# AI_EINK.net
KiCad netlist of a schematic drawn in EAGLE
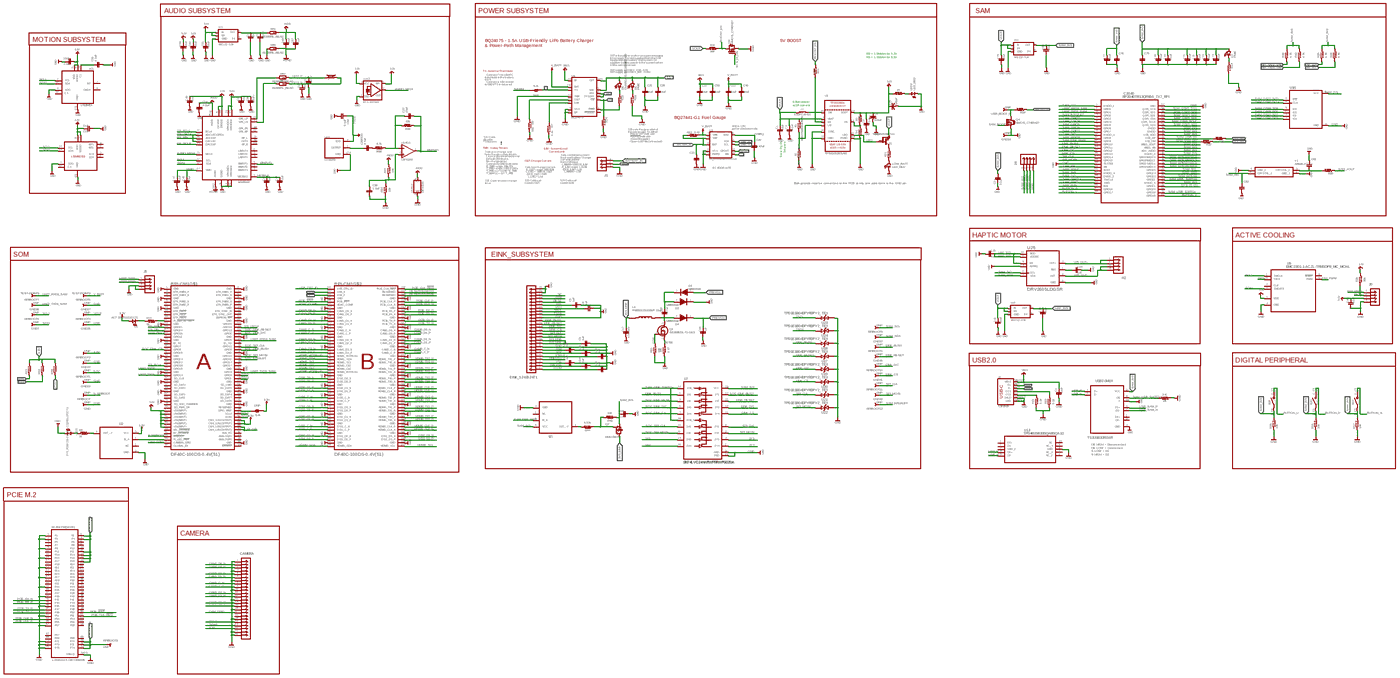
[diagram p0: schematic, sheet 1, overview]
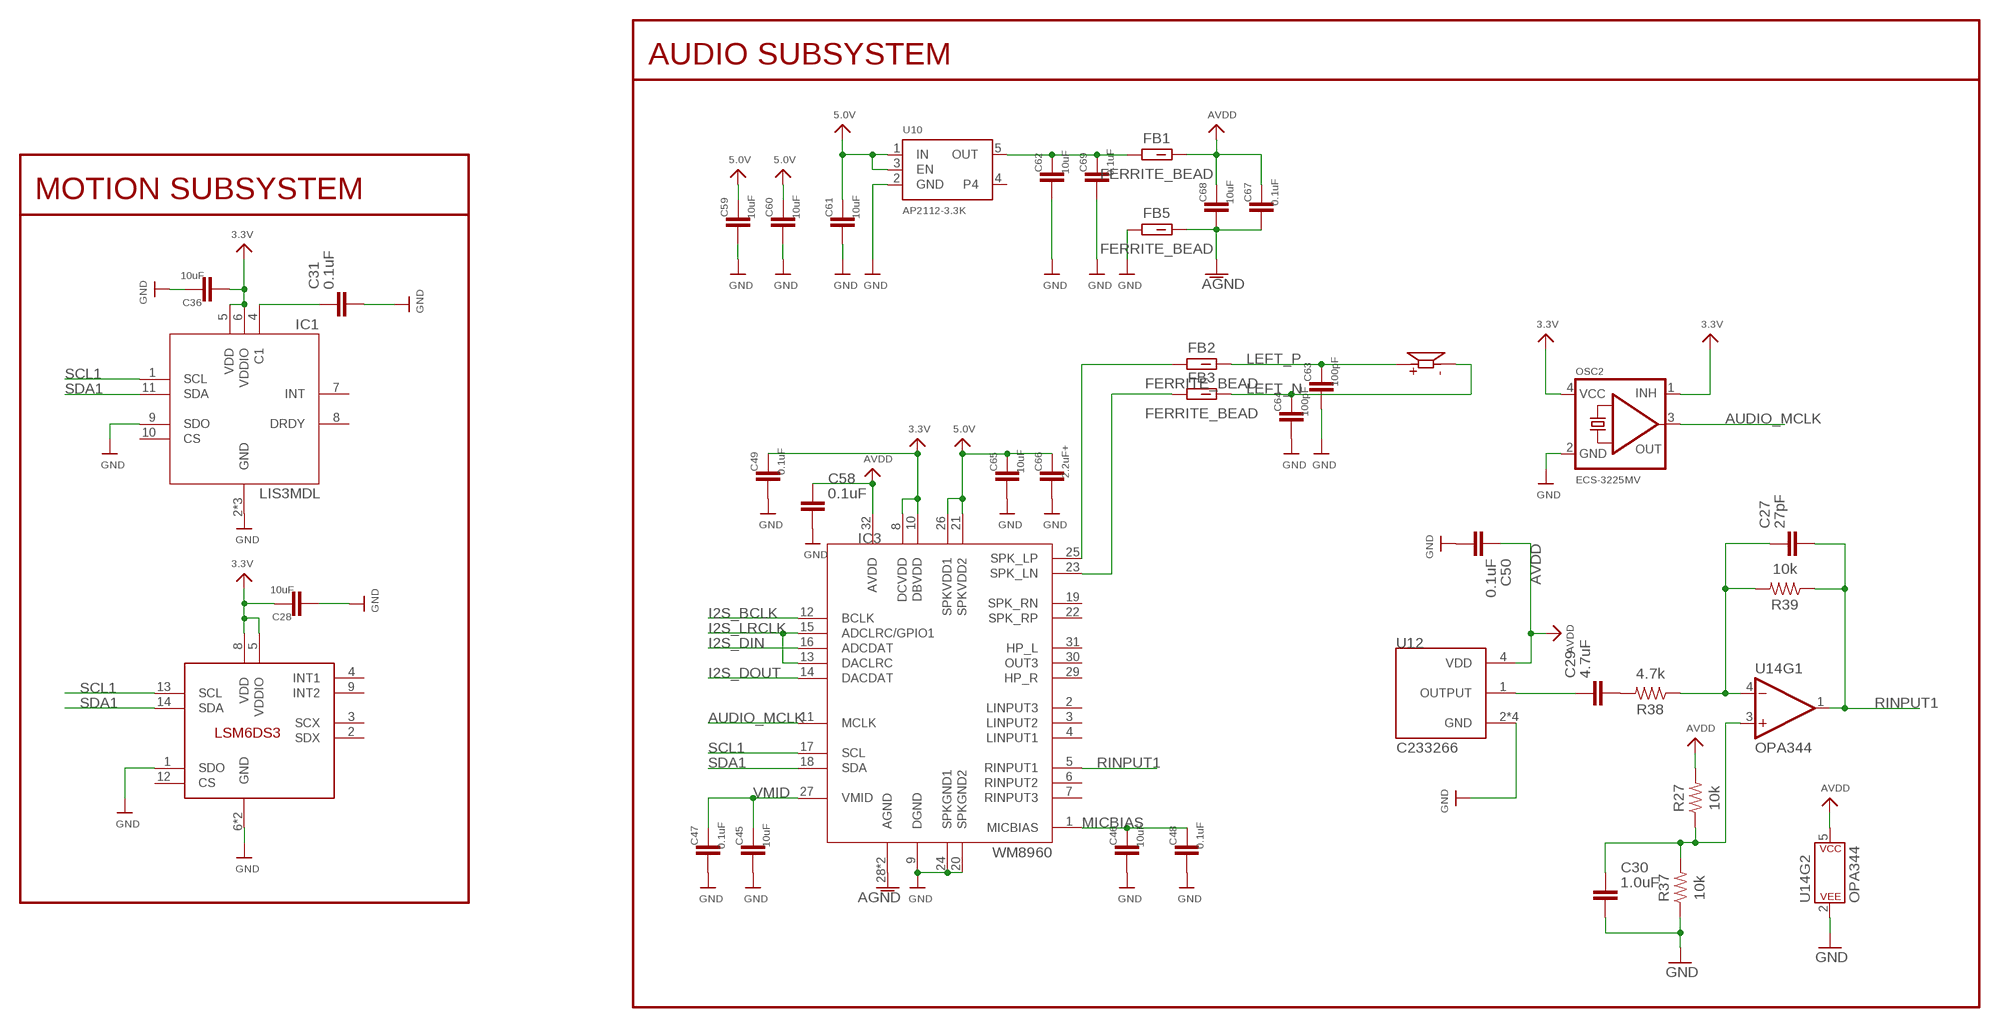
[diagram p1: schematic, sheet 1, part 1 of 5]
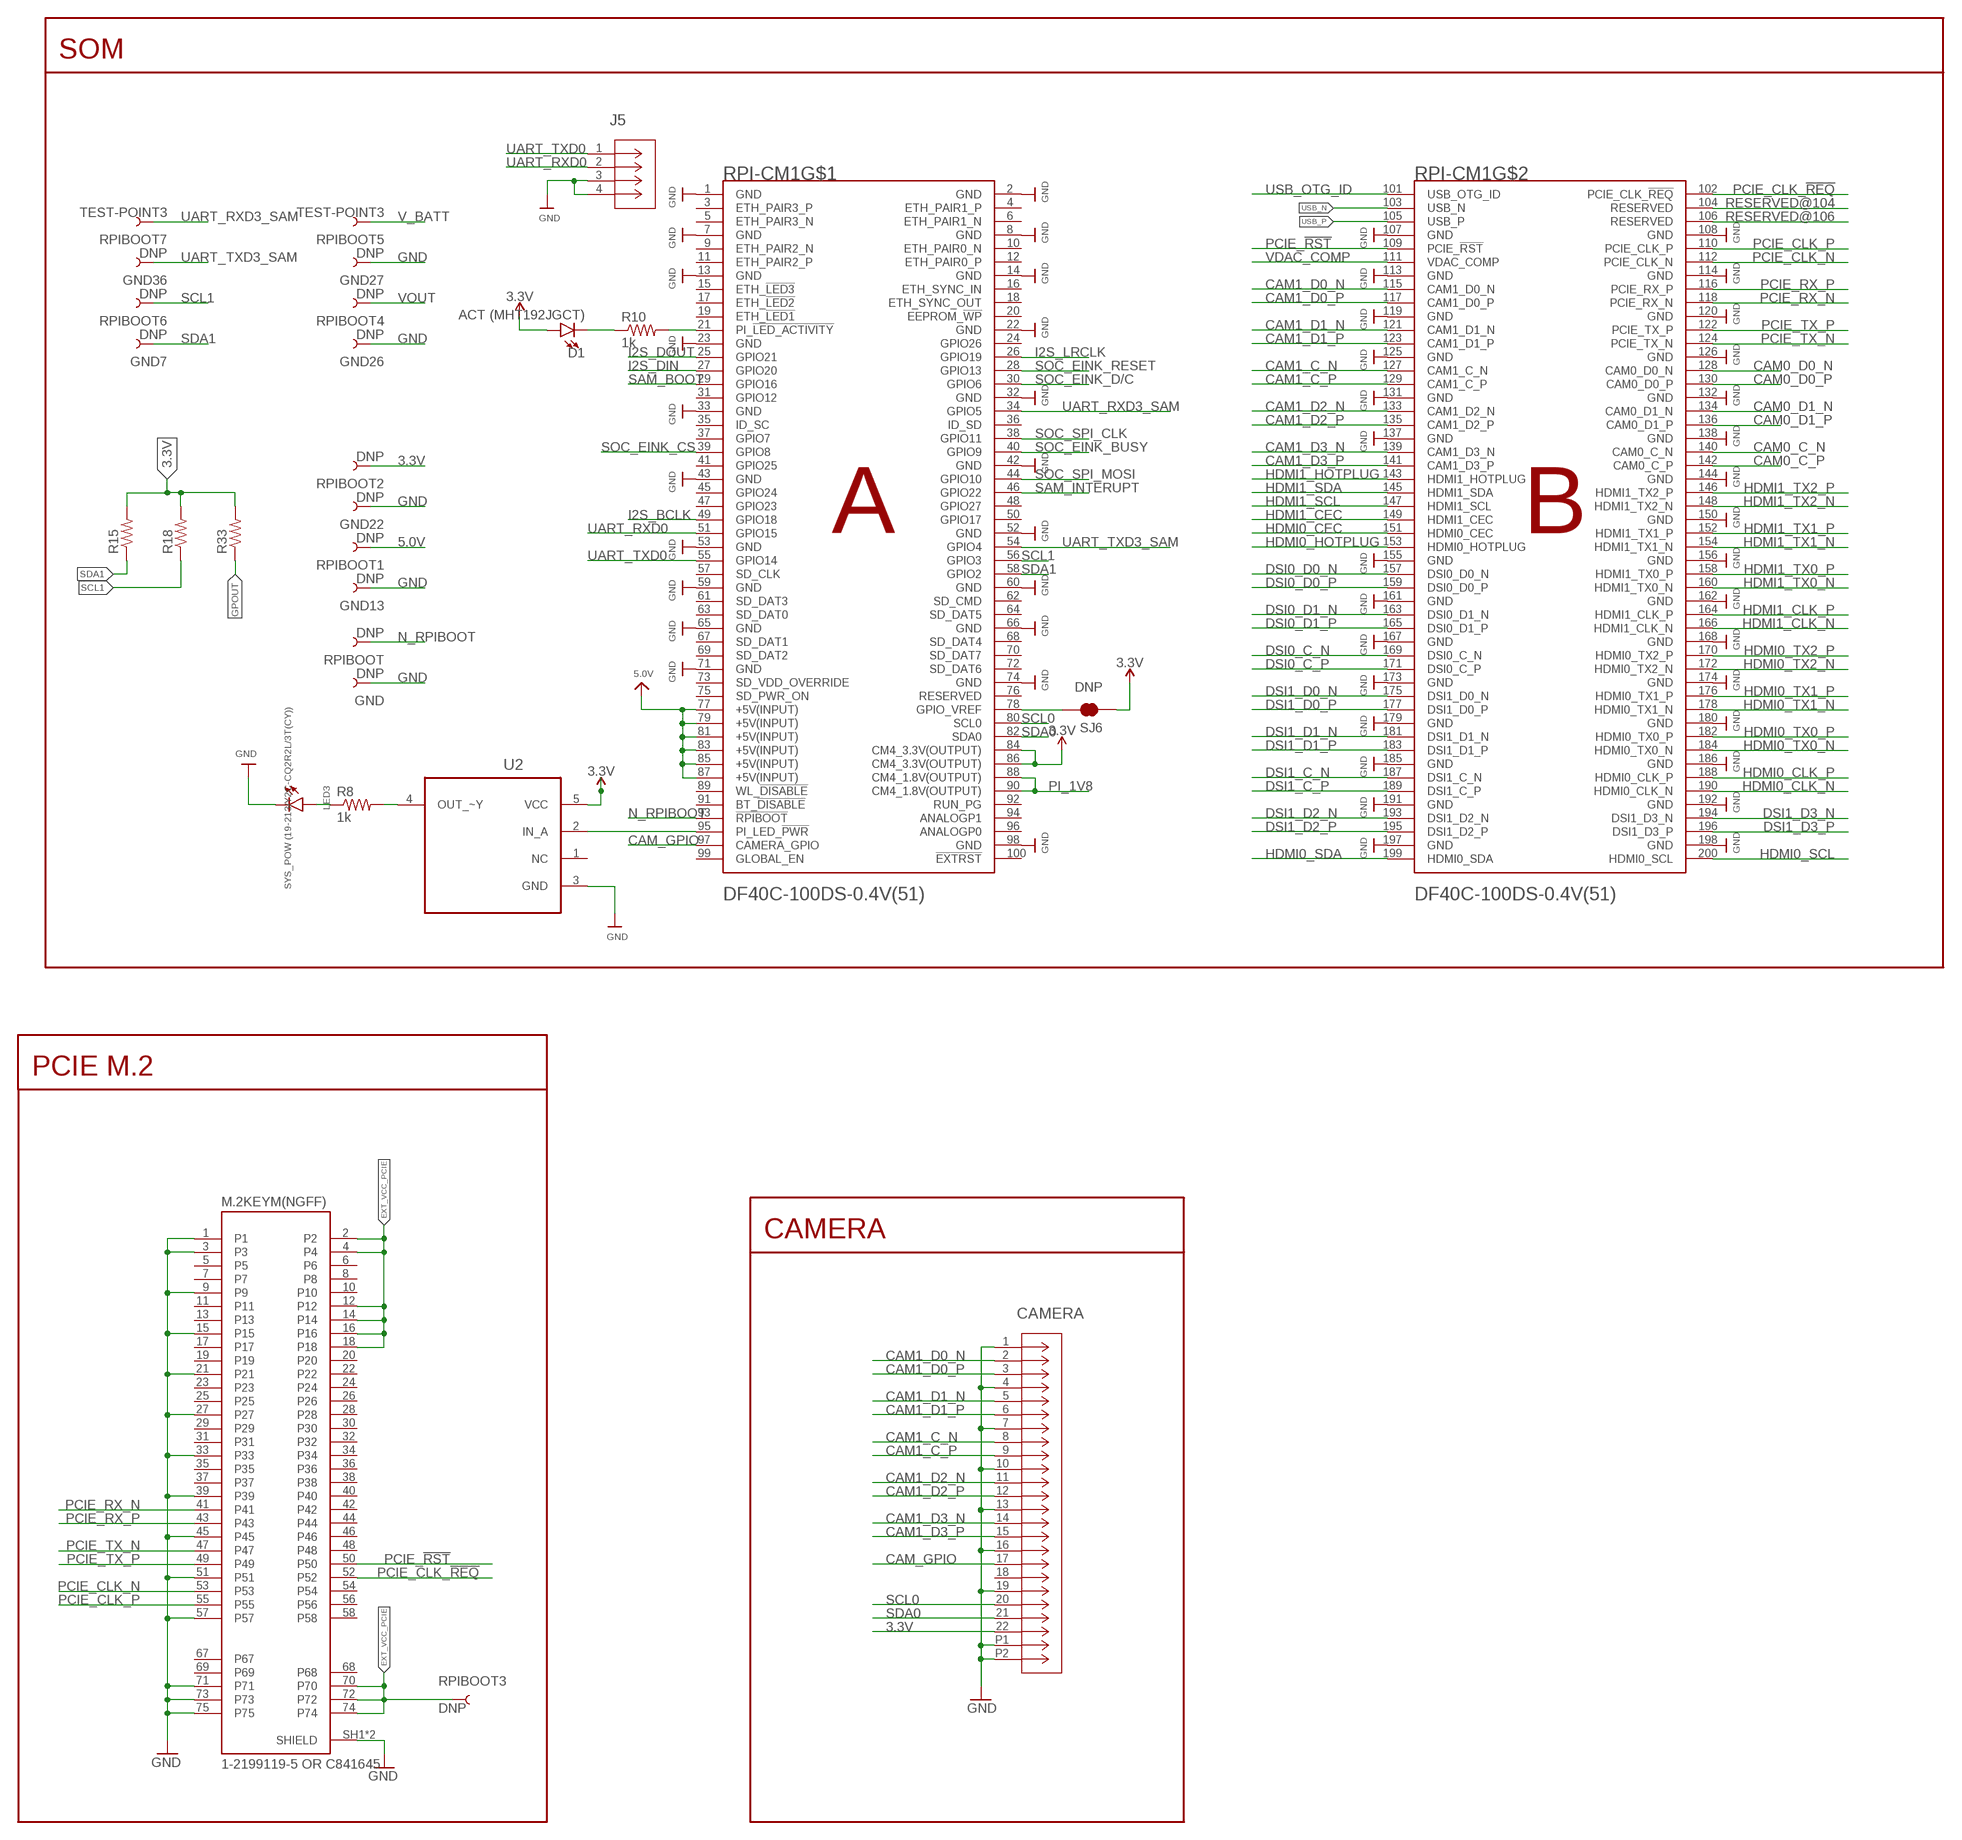
[diagram p2: schematic, sheet 1, part 2 of 5]
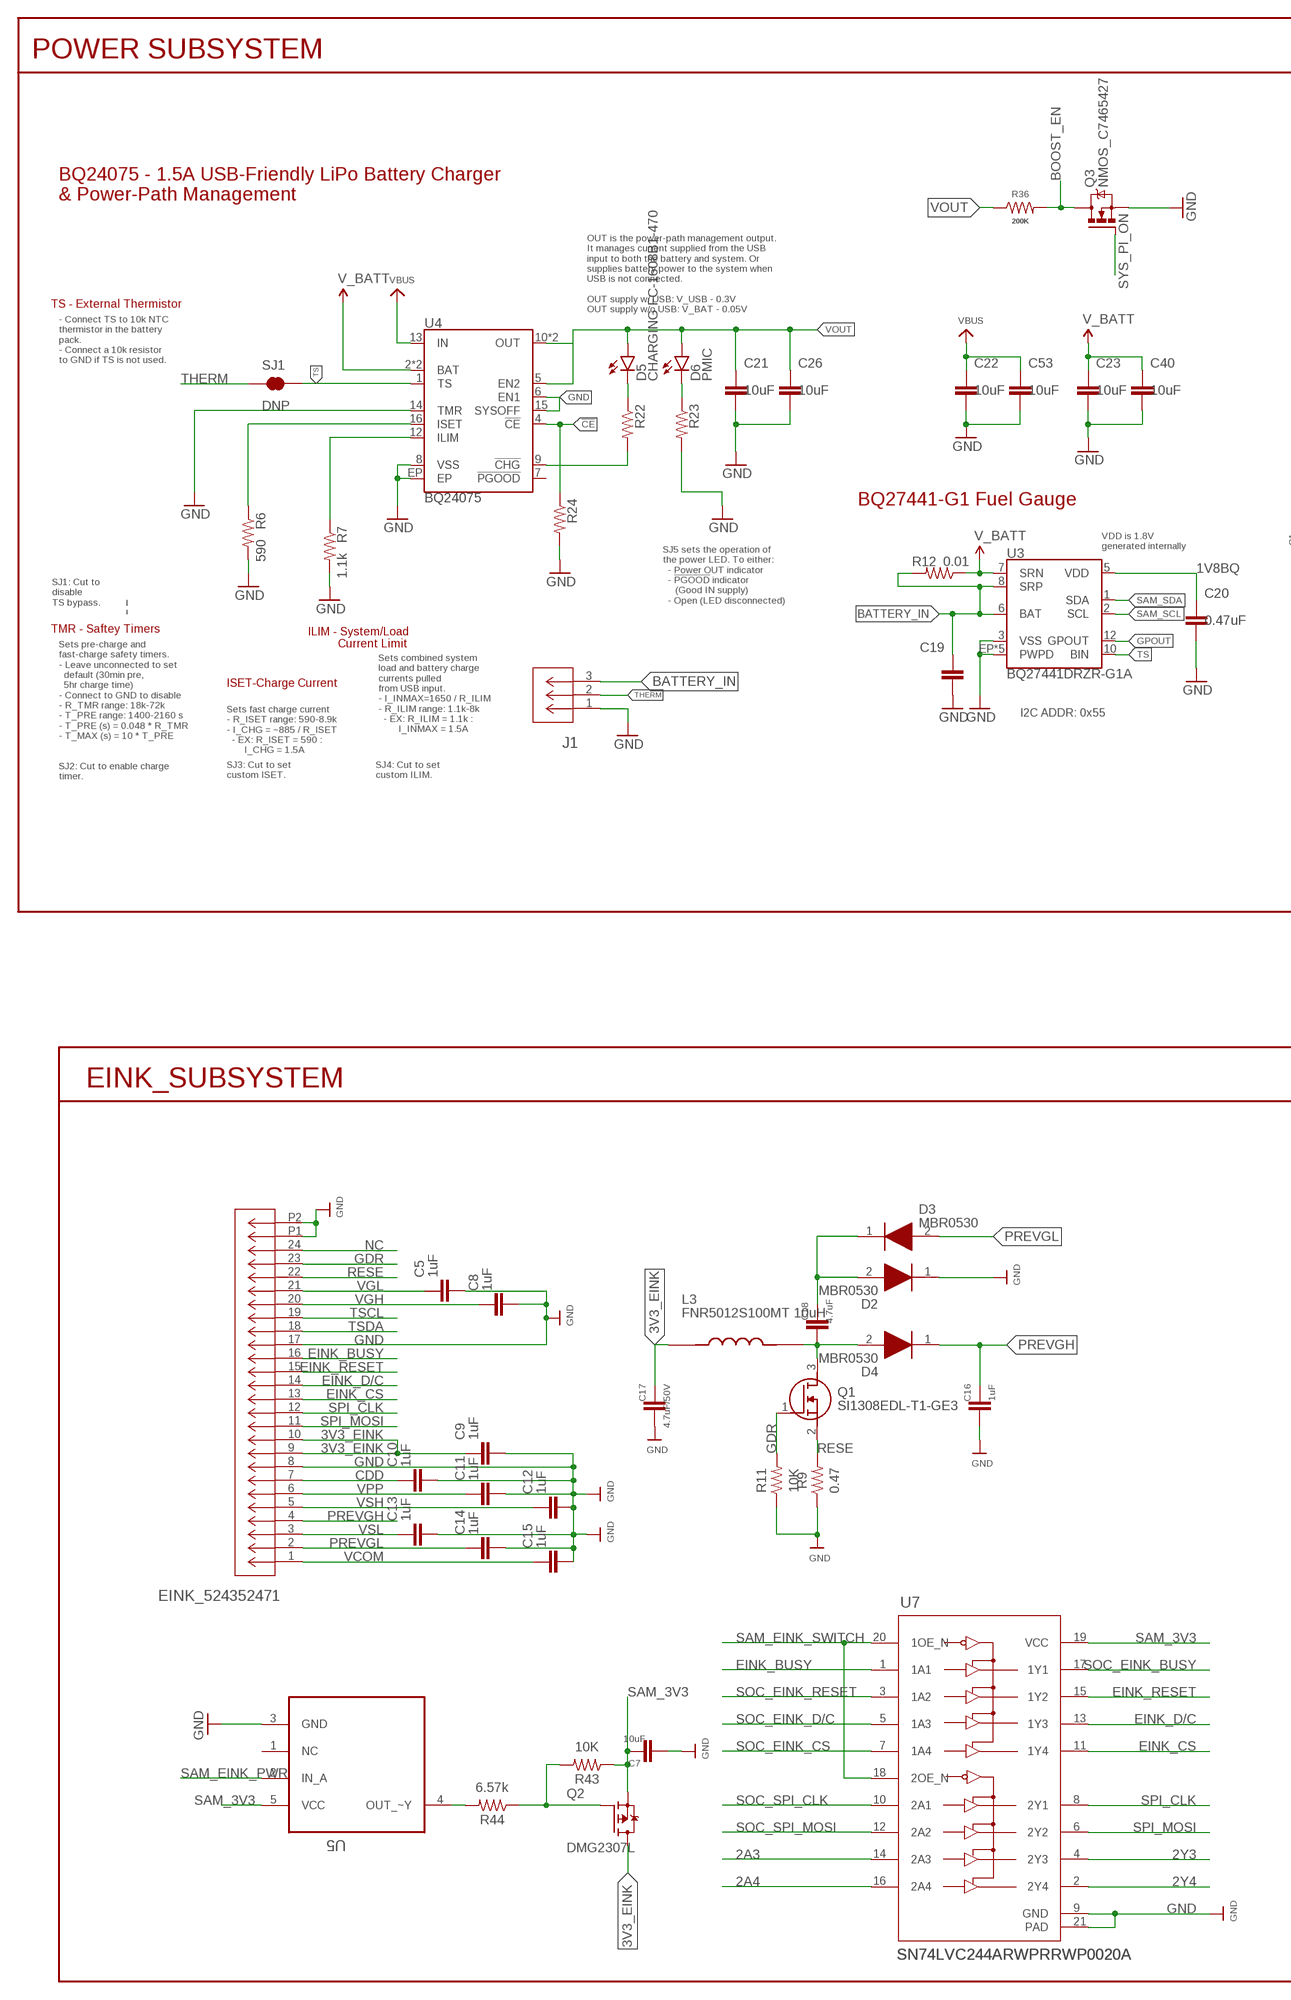
[diagram p3: schematic, sheet 1, part 3 of 5]
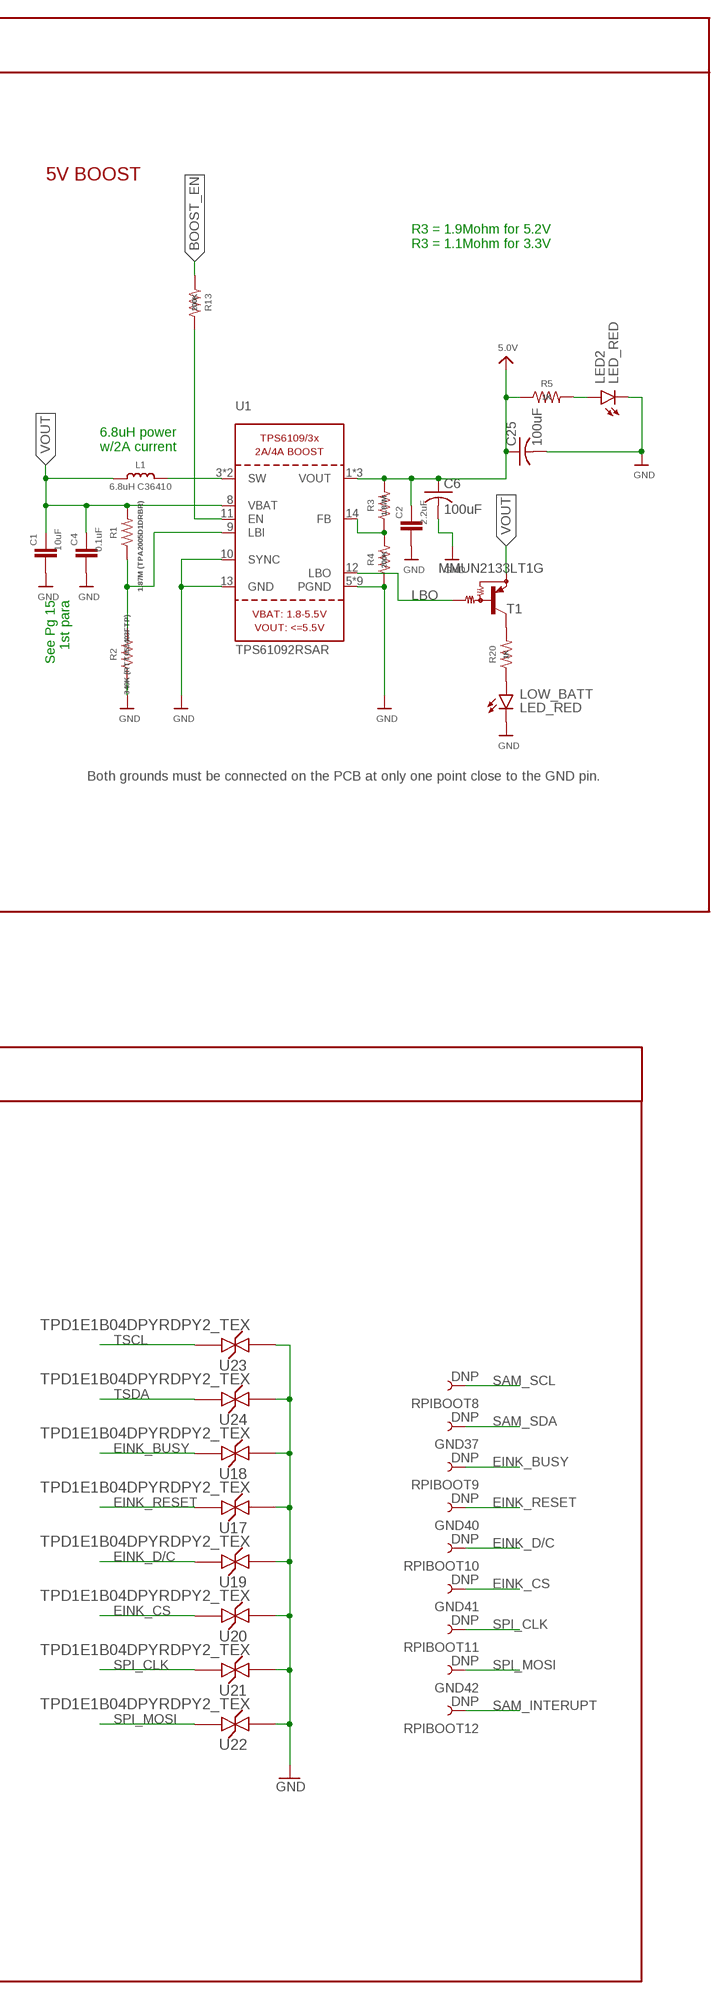
[diagram p4: schematic, sheet 1, part 4 of 5]
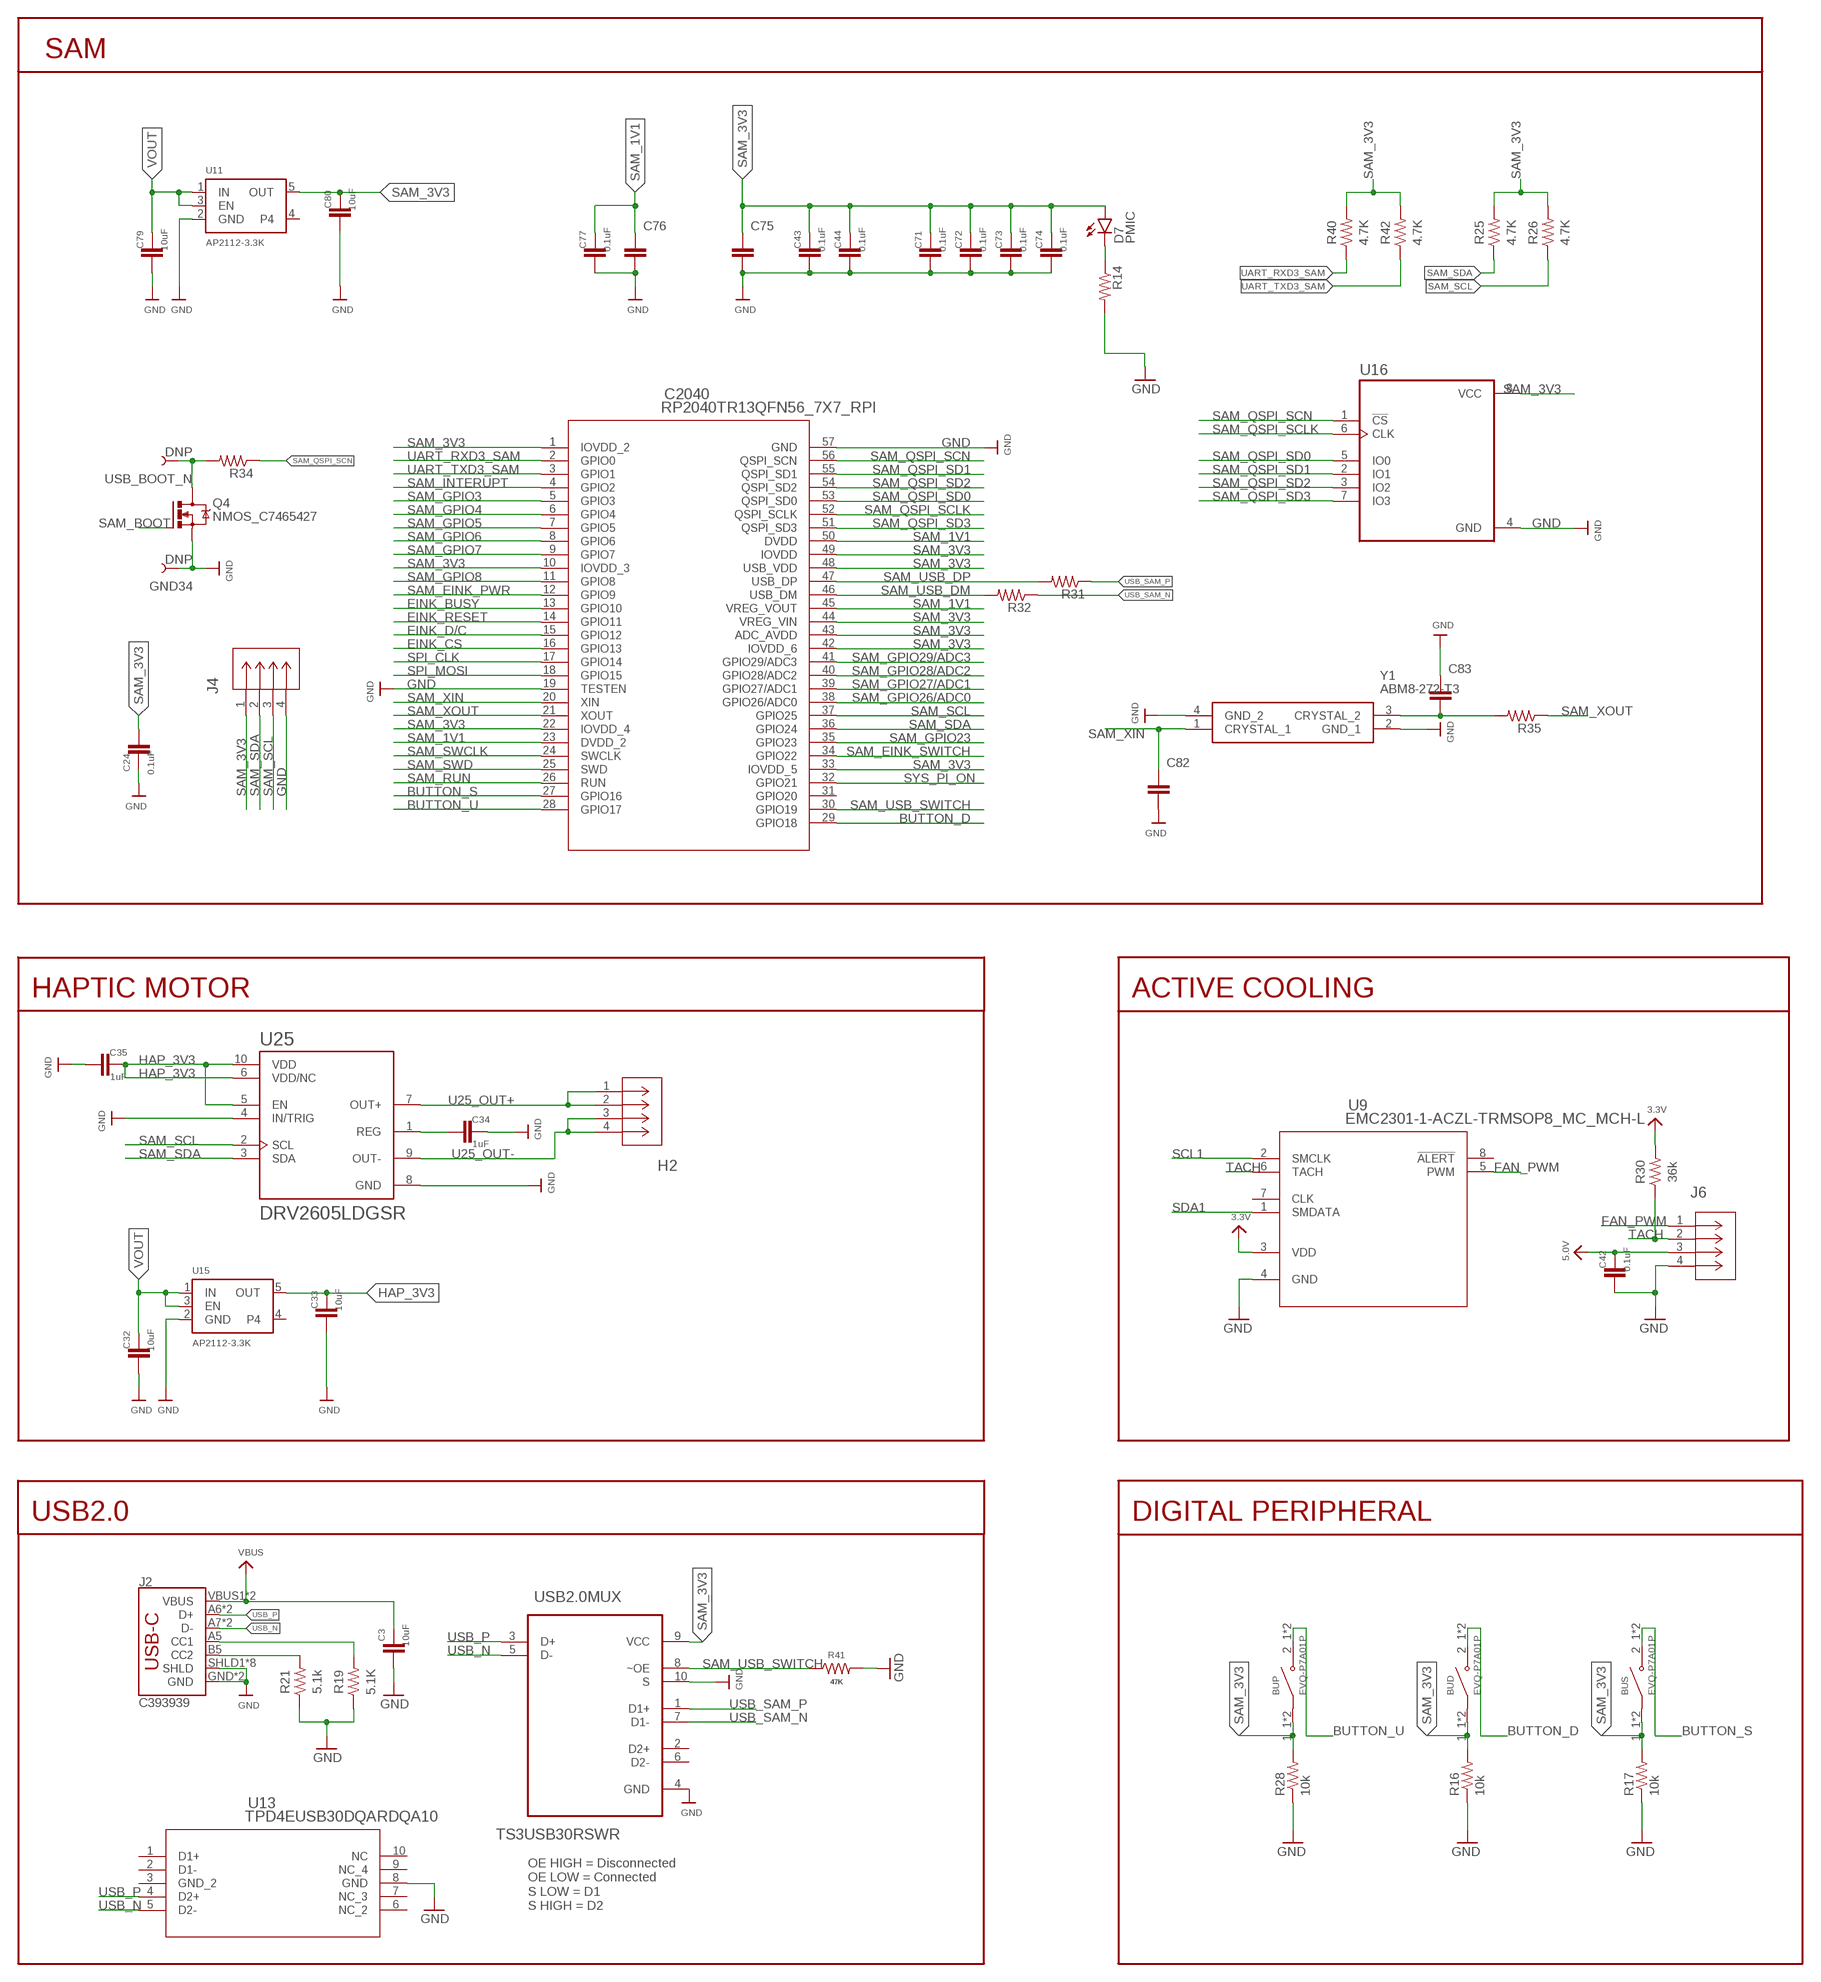
[diagram p5: schematic, sheet 1, part 5 of 5]

(export (version "E")
  (design (tool "Eeschema 10.0.6"))
  (components
    (comp (ref "BUD")
      (value "EVQ-P7A01P")
      (footprint "eagle-import:SW_EVQ-P7A01P")
      (fields (field (name "MANUFACTURER") "Panasonic Electronic Components"))
      (libsource (lib "eagle-import") (part "EVQ-P7A01P"))
    )
    (comp (ref "BUP")
      (value "EVQ-P7A01P")
      (footprint "eagle-import:SW_EVQ-P7A01P")
      (fields (field (name "MANUFACTURER") "Panasonic Electronic Components"))
      (libsource (lib "eagle-import") (part "EVQ-P7A01P"))
    )
    (comp (ref "BUS")
      (value "EVQ-P7A01P")
      (footprint "eagle-import:SW_EVQ-P7A01P")
      (fields (field (name "MANUFACTURER") "Panasonic Electronic Components"))
      (libsource (lib "eagle-import") (part "EVQ-P7A01P"))
    )
    (comp (ref "C1")
      (value "10uF")
      (footprint "eagle-import:CAPC1005X60")
      (libsource (lib "eagle-import") (part "CCHIP-0402(1005-METRIC)_"))
    )
    (comp (ref "C2")
      (value "2.2uF")
      (footprint "eagle-import:CAPC1005X60")
      (libsource (lib "eagle-import") (part "CCHIP-0402(1005-METRIC)_"))
    )
    (comp (ref "C3")
      (value "10uF")
      (footprint "eagle-import:CAPC1005X60")
      (libsource (lib "eagle-import") (part "CCHIP-0402(1005-METRIC)_"))
    )
    (comp (ref "C4")
      (value "0.1uF")
      (footprint "eagle-import:CAPC1005X60")
      (libsource (lib "eagle-import") (part "CCHIP-0402(1005-METRIC)_"))
    )
    (comp (ref "C5")
      (value "1uF")
      (footprint "eagle-import:CAPC1005X60")
      (libsource (lib "eagle-import") (part "CCHIP-0402(1005-METRIC)_"))
    )
    (comp (ref "C6")
      (value "100uF")
      (footprint "eagle-import:C1210")
      (libsource (lib "eagle-import") (part "C-USC1210"))
    )
    (comp (ref "C7")
      (value "10uF")
      (footprint "eagle-import:CAPC1005X60")
      (libsource (lib "eagle-import") (part "CCHIP-0402(1005-METRIC)_"))
    )
    (comp (ref "C8")
      (value "1uF")
      (footprint "eagle-import:CAPC1005X60")
      (libsource (lib "eagle-import") (part "CCHIP-0402(1005-METRIC)_"))
    )
    (comp (ref "C9")
      (value "1uF")
      (footprint "eagle-import:CAPC1005X60")
      (libsource (lib "eagle-import") (part "CCHIP-0402(1005-METRIC)_"))
    )
    (comp (ref "C10")
      (value "1uF")
      (footprint "eagle-import:CAPC1005X60")
      (libsource (lib "eagle-import") (part "CCHIP-0402(1005-METRIC)_"))
    )
    (comp (ref "C11")
      (value "1uF")
      (footprint "eagle-import:CAPC1005X60")
      (libsource (lib "eagle-import") (part "CCHIP-0402(1005-METRIC)_"))
    )
    (comp (ref "C12")
      (value "1uF")
      (footprint "eagle-import:CAPC1005X60")
      (libsource (lib "eagle-import") (part "CCHIP-0402(1005-METRIC)_"))
    )
    (comp (ref "C13")
      (value "1uF")
      (footprint "eagle-import:CAPC1005X60")
      (libsource (lib "eagle-import") (part "CCHIP-0402(1005-METRIC)_"))
    )
    (comp (ref "C14")
      (value "1uF")
      (footprint "eagle-import:CAPC1005X60")
      (libsource (lib "eagle-import") (part "CCHIP-0402(1005-METRIC)_"))
    )
    (comp (ref "C15")
      (value "1uF")
      (footprint "eagle-import:CAPC1005X60")
      (libsource (lib "eagle-import") (part "CCHIP-0402(1005-METRIC)_"))
    )
    (comp (ref "C16")
      (value "1uF")
      (footprint "eagle-import:CAPC1005X60")
      (libsource (lib "eagle-import") (part "CCHIP-0402(1005-METRIC)_"))
    )
    (comp (ref "C17")
      (value "4.7uF/50V")
      (footprint "eagle-import:CAPC1005X60")
      (libsource (lib "eagle-import") (part "CCHIP-0402(1005-METRIC)_"))
    )
    (comp (ref "C18")
      (value "4.7uF")
      (footprint "eagle-import:CAPC1608X85")
      (libsource (lib "eagle-import") (part "CCHIP-0603(1608-METRIC)_"))
    )
    (comp (ref "C19")
      (value "1.0uF")
      (footprint "eagle-import:CAPC1005X60")
      (libsource (lib "eagle-import") (part "CCHIP-0402(1005-METRIC)_"))
    )
    (comp (ref "C20")
      (value "0.47uF")
      (footprint "eagle-import:CAPC1005X60")
      (libsource (lib "eagle-import") (part "CCHIP-0402(1005-METRIC)_"))
    )
    (comp (ref "C21")
      (value "10uF")
      (footprint "eagle-import:CAPC1005X60")
      (libsource (lib "eagle-import") (part "CCHIP-0402(1005-METRIC)_"))
    )
    (comp (ref "C22")
      (value "10uF")
      (footprint "eagle-import:CAPC1005X60")
      (libsource (lib "eagle-import") (part "CCHIP-0402(1005-METRIC)_"))
    )
    (comp (ref "C23")
      (value "10uF")
      (footprint "eagle-import:CAPC1005X60")
      (libsource (lib "eagle-import") (part "CCHIP-0402(1005-METRIC)_"))
    )
    (comp (ref "C24")
      (value "0.1uF")
      (footprint "eagle-import:CAPC1005X60")
      (libsource (lib "eagle-import") (part "CCHIP-0402(1005-METRIC)_"))
    )
    (comp (ref "C25")
      (value "100uF")
      (footprint "eagle-import:C1210")
      (libsource (lib "eagle-import") (part "C-USC1210"))
    )
    (comp (ref "C26")
      (value "10uF")
      (footprint "eagle-import:CAPC1005X60")
      (libsource (lib "eagle-import") (part "CCHIP-0402(1005-METRIC)_"))
    )
    (comp (ref "C27")
      (value "27pF")
      (footprint "eagle-import:CAPC1005X60")
      (libsource (lib "eagle-import") (part "CCHIP-0402(1005-METRIC)_"))
    )
    (comp (ref "C28")
      (value "10uF")
      (footprint "eagle-import:CAPC1005X60")
      (libsource (lib "eagle-import") (part "CCHIP-0402(1005-METRIC)_"))
    )
    (comp (ref "C29")
      (value "4.7uF")
      (footprint "eagle-import:CAPC1005X60")
      (libsource (lib "eagle-import") (part "CCHIP-0402(1005-METRIC)_"))
    )
    (comp (ref "C30")
      (value "1.0uF")
      (footprint "eagle-import:CAPC1005X60")
      (libsource (lib "eagle-import") (part "CCHIP-0402(1005-METRIC)_"))
    )
    (comp (ref "C31")
      (value "0.1uF")
      (footprint "eagle-import:CAPC1005X60")
      (libsource (lib "eagle-import") (part "CCHIP-0402(1005-METRIC)_"))
    )
    (comp (ref "C32")
      (value "10uF")
      (footprint "eagle-import:CAPC1005X60")
      (libsource (lib "eagle-import") (part "CCHIP-0402(1005-METRIC)_"))
    )
    (comp (ref "C33")
      (value "10uF")
      (footprint "eagle-import:CAPC1005X60")
      (libsource (lib "eagle-import") (part "CCHIP-0402(1005-METRIC)_"))
    )
    (comp (ref "C34")
      (value "1uF")
      (footprint "eagle-import:CAPC1005X60")
      (libsource (lib "eagle-import") (part "CCHIP-0402(1005-METRIC)_"))
    )
    (comp (ref "C35")
      (value "1uF")
      (footprint "eagle-import:CAPC1005X60")
      (libsource (lib "eagle-import") (part "CCHIP-0402(1005-METRIC)_"))
    )
    (comp (ref "C36")
      (value "10uF")
      (footprint "eagle-import:CAPC1005X60")
      (libsource (lib "eagle-import") (part "CCHIP-0402(1005-METRIC)_"))
    )
    (comp (ref "C40")
      (value "10uF")
      (footprint "eagle-import:CAPC1005X60")
      (libsource (lib "eagle-import") (part "CCHIP-0402(1005-METRIC)_"))
    )
    (comp (ref "C42")
      (value "0.1uF")
      (footprint "eagle-import:CAPC1608X85")
      (libsource (lib "eagle-import") (part "CCHIP-0603(1608-METRIC)_"))
    )
    (comp (ref "C43")
      (value "0.1uF")
      (footprint "eagle-import:CAPC1005X60")
      (libsource (lib "eagle-import") (part "CCHIP-0402(1005-METRIC)_"))
    )
    (comp (ref "C44")
      (value "0.1uF")
      (footprint "eagle-import:CAPC1005X60")
      (libsource (lib "eagle-import") (part "CCHIP-0402(1005-METRIC)_"))
    )
    (comp (ref "C45")
      (value "10uF")
      (footprint "eagle-import:CAPC1005X60")
      (libsource (lib "eagle-import") (part "CCHIP-0402(1005-METRIC)_"))
    )
    (comp (ref "C46")
      (value "10uF")
      (footprint "eagle-import:CAPC1005X60")
      (libsource (lib "eagle-import") (part "CCHIP-0402(1005-METRIC)_"))
    )
    (comp (ref "C47")
      (value "0.1uF")
      (footprint "eagle-import:CAPC1005X60")
      (libsource (lib "eagle-import") (part "CCHIP-0402(1005-METRIC)_"))
    )
    (comp (ref "C48")
      (value "0.1uF")
      (footprint "eagle-import:CAPC1005X60")
      (libsource (lib "eagle-import") (part "CCHIP-0402(1005-METRIC)_"))
    )
    (comp (ref "C49")
      (value "0.1uF")
      (footprint "eagle-import:CAPC1005X60")
      (libsource (lib "eagle-import") (part "CCHIP-0402(1005-METRIC)_"))
    )
    (comp (ref "C50")
      (value "0.1uF")
      (footprint "eagle-import:CAPC1005X60")
      (libsource (lib "eagle-import") (part "CCHIP-0402(1005-METRIC)_"))
    )
    (comp (ref "C53")
      (value "10uF")
      (footprint "eagle-import:CAPC1005X60")
      (libsource (lib "eagle-import") (part "CCHIP-0402(1005-METRIC)_"))
    )
    (comp (ref "C58")
      (value "0.1uF")
      (footprint "eagle-import:CAPC1005X60")
      (libsource (lib "eagle-import") (part "CCHIP-0402(1005-METRIC)_"))
    )
    (comp (ref "C59")
      (value "10uF")
      (footprint "eagle-import:CAPC1005X60")
      (libsource (lib "eagle-import") (part "CCHIP-0402(1005-METRIC)_"))
    )
    (comp (ref "C60")
      (value "10uF")
      (footprint "eagle-import:CAPC1005X60")
      (libsource (lib "eagle-import") (part "CCHIP-0402(1005-METRIC)_"))
    )
    (comp (ref "C61")
      (value "10uF")
      (footprint "eagle-import:CAPC1005X60")
      (libsource (lib "eagle-import") (part "CCHIP-0402(1005-METRIC)_"))
    )
    (comp (ref "C62")
      (value "10uF")
      (footprint "eagle-import:CAPC1005X60")
      (libsource (lib "eagle-import") (part "CCHIP-0402(1005-METRIC)_"))
    )
    (comp (ref "C63")
      (value "100pF")
      (footprint "eagle-import:CAPC1005X60")
      (libsource (lib "eagle-import") (part "CCHIP-0402(1005-METRIC)_"))
    )
    (comp (ref "C64")
      (value "100pF")
      (footprint "eagle-import:CAPC1005X60")
      (libsource (lib "eagle-import") (part "CCHIP-0402(1005-METRIC)_"))
    )
    (comp (ref "C65")
      (value "10uF")
      (footprint "eagle-import:CAPC1005X60")
      (libsource (lib "eagle-import") (part "CCHIP-0402(1005-METRIC)_"))
    )
    (comp (ref "C66")
      (value "2.2uF+")
      (footprint "eagle-import:CAPC1005X60")
      (libsource (lib "eagle-import") (part "CCHIP-0402(1005-METRIC)_"))
    )
    (comp (ref "C67")
      (value "0.1uF")
      (footprint "eagle-import:CAPC1005X60")
      (libsource (lib "eagle-import") (part "CCHIP-0402(1005-METRIC)_"))
    )
    (comp (ref "C68")
      (value "10uF")
      (footprint "eagle-import:CAPC1005X60")
      (libsource (lib "eagle-import") (part "CCHIP-0402(1005-METRIC)_"))
    )
    (comp (ref "C69")
      (value "0.1uF")
      (footprint "eagle-import:CAPC1005X60")
      (libsource (lib "eagle-import") (part "CCHIP-0402(1005-METRIC)_"))
    )
    (comp (ref "C71")
      (value "0.1uF")
      (footprint "eagle-import:CAPC1005X60")
      (libsource (lib "eagle-import") (part "CCHIP-0402(1005-METRIC)_"))
    )
    (comp (ref "C72")
      (value "0.1uF")
      (footprint "eagle-import:CAPC1005X60")
      (libsource (lib "eagle-import") (part "CCHIP-0402(1005-METRIC)_"))
    )
    (comp (ref "C73")
      (value "0.1uF")
      (footprint "eagle-import:CAPC1005X60")
      (libsource (lib "eagle-import") (part "CCHIP-0402(1005-METRIC)_"))
    )
    (comp (ref "C74")
      (value "0.1uF")
      (footprint "eagle-import:CAPC1005X60")
      (libsource (lib "eagle-import") (part "CCHIP-0402(1005-METRIC)_"))
    )
    (comp (ref "C75")
      (value "1.0uF")
      (footprint "eagle-import:CAPC1005X60")
      (libsource (lib "eagle-import") (part "CCHIP-0402(1005-METRIC)_"))
    )
    (comp (ref "C76")
      (value "1.0uF")
      (footprint "eagle-import:CAPC1005X60")
      (libsource (lib "eagle-import") (part "CCHIP-0402(1005-METRIC)_"))
    )
    (comp (ref "C77")
      (value "0.1uF")
      (footprint "eagle-import:CAPC1005X60")
      (libsource (lib "eagle-import") (part "CCHIP-0402(1005-METRIC)_"))
    )
    (comp (ref "C79")
      (value "10uF")
      (footprint "eagle-import:CAPC1005X60")
      (libsource (lib "eagle-import") (part "CCHIP-0402(1005-METRIC)_"))
    )
    (comp (ref "C80")
      (value "10uF")
      (footprint "eagle-import:CAPC1005X60")
      (libsource (lib "eagle-import") (part "CCHIP-0402(1005-METRIC)_"))
    )
    (comp (ref "C82")
      (value "15p")
      (footprint "eagle-import:CAPC1005X60")
      (libsource (lib "eagle-import") (part "CCHIP-0402(1005-METRIC)_"))
    )
    (comp (ref "C83")
      (value "15p")
      (footprint "eagle-import:CAPC1005X60")
      (libsource (lib "eagle-import") (part "CCHIP-0402(1005-METRIC)_"))
    )
    (comp (ref "C2040")
      (value "RP2040TR13QFN56_7X7_RPI")
      (footprint "eagle-import:QFN56_7X7_RPI")
      (fields
        (field (name "MANUFACTURER_PART_NUMBER") "RP2040TR13")
        (field (name "COPYRIGHT") "Copyright (C) 2024 Ultra Librarian. All rights reserved.")
      )
      (libsource (lib "eagle-import") (part "RP2040TR13QFN56_7X7_RPI"))
    )
    (comp (ref "CAMERA")
      (value "C262642")
      (footprint "eagle-import:CON_524372271_MOL")
      (fields
        (field (name "MANUFACTURER_PART_NUMBER") "524372271")
        (field (name "COPYRIGHT") "Copyright (C) 2024 Ultra Librarian. All rights reserved.")
      )
      (libsource (lib "eagle-import") (part "524372271CON_524372271_MOL"))
    )
    (comp (ref "D1")
      (value "ACT (MHT192JGCT)")
      (footprint "eagle-import:LED-0603@1")
      (libsource (lib "eagle-import") (part "LED-GREEN0603"))
    )
    (comp (ref "D2")
      (value "MBR0530")
      (footprint "eagle-import:SOD3716X135N")
      (fields (field (name "MF") "ON Semiconductor"))
      (libsource (lib "eagle-import") (part "MBR0530"))
    )
    (comp (ref "D3")
      (value "MBR0530")
      (footprint "eagle-import:SOD3716X135N")
      (fields (field (name "MF") "ON Semiconductor"))
      (libsource (lib "eagle-import") (part "MBR0530"))
    )
    (comp (ref "D4")
      (value "MBR0530")
      (footprint "eagle-import:SOD3716X135N")
      (fields (field (name "MF") "ON Semiconductor"))
      (libsource (lib "eagle-import") (part "MBR0530"))
    )
    (comp (ref "D5")
      (value "CHARGING FC-1608B1-470")
      (footprint "eagle-import:LED-0603")
      (libsource (lib "eagle-import") (part "LED-BLUE0603"))
    )
    (comp (ref "D6")
      (value "PMIC")
      (footprint "eagle-import:LED-0603")
      (libsource (lib "eagle-import") (part "LED-RED0603"))
    )
    (comp (ref "D7")
      (value "PMIC")
      (footprint "eagle-import:LED-0603")
      (libsource (lib "eagle-import") (part "LED-RED0603"))
    )
    (comp (ref "EINK_524352471")
      (value "524372471")
      (footprint "eagle-import:CON_524372471_MOL")
      (fields (field (name "COPYRIGHT") "Copyright (C) 2024 Ultra Librarian. All rights reserved."))
      (libsource (lib "eagle-import") (part "524372471CON_524372471_MOL"))
    )
    (comp (ref "FB1")
      (value "FERRITE_BEAD")
      (footprint "eagle-import:BEADC1608X95N")
      (libsource (lib "eagle-import") (part "FBCHIP-0603(1608-METRIC)"))
    )
    (comp (ref "FB2")
      (value "FERRITE_BEAD")
      (footprint "eagle-import:BEADC1608X95N")
      (libsource (lib "eagle-import") (part "FBCHIP-0603(1608-METRIC)"))
    )
    (comp (ref "FB3")
      (value "FERRITE_BEAD")
      (footprint "eagle-import:BEADC1608X95N")
      (libsource (lib "eagle-import") (part "FBCHIP-0603(1608-METRIC)"))
    )
    (comp (ref "FB5")
      (value "FERRITE_BEAD")
      (footprint "eagle-import:BEADC1608X95N")
      (libsource (lib "eagle-import") (part "FBCHIP-0603(1608-METRIC)"))
    )
    (comp (ref "GND")
      (value "DNP")
      (footprint "eagle-import:PAD.03X.03")
      (libsource (lib "eagle-import") (part "TEST-POINT3"))
    )
    (comp (ref "GND7")
      (value "DNP")
      (footprint "eagle-import:PAD.03X.03")
      (libsource (lib "eagle-import") (part "TEST-POINT3"))
    )
    (comp (ref "GND13")
      (value "DNP")
      (footprint "eagle-import:PAD.03X.03")
      (libsource (lib "eagle-import") (part "TEST-POINT3"))
    )
    (comp (ref "GND22")
      (value "DNP")
      (footprint "eagle-import:PAD.03X.03")
      (libsource (lib "eagle-import") (part "TEST-POINT3"))
    )
    (comp (ref "GND26")
      (value "DNP")
      (footprint "eagle-import:PAD.03X.03")
      (libsource (lib "eagle-import") (part "TEST-POINT3"))
    )
    (comp (ref "GND27")
      (value "DNP")
      (footprint "eagle-import:PAD.03X.03")
      (libsource (lib "eagle-import") (part "TEST-POINT3"))
    )
    (comp (ref "GND34")
      (value "DNP")
      (footprint "eagle-import:PAD.03X.03")
      (libsource (lib "eagle-import") (part "TEST-POINT3"))
    )
    (comp (ref "GND36")
      (value "DNP")
      (footprint "eagle-import:PAD.03X.03")
      (libsource (lib "eagle-import") (part "TEST-POINT3"))
    )
    (comp (ref "GND37")
      (value "DNP")
      (footprint "eagle-import:PAD.03X.03")
      (libsource (lib "eagle-import") (part "TEST-POINT3"))
    )
    (comp (ref "GND40")
      (value "DNP")
      (footprint "eagle-import:PAD.03X.03")
      (libsource (lib "eagle-import") (part "TEST-POINT3"))
    )
    (comp (ref "GND41")
      (value "DNP")
      (footprint "eagle-import:PAD.03X.03")
      (libsource (lib "eagle-import") (part "TEST-POINT3"))
    )
    (comp (ref "GND42")
      (value "DNP")
      (footprint "eagle-import:PAD.03X.03")
      (libsource (lib "eagle-import") (part "TEST-POINT3"))
    )
    (comp (ref "H2")
      (value "BM04B-SRSS-TBCONN4_BM04B-SRSS_JST")
      (footprint "eagle-import:CONN4_BM04B-SRSS_JST")
      (fields
        (field (name "MANUFACTURER_PART_NUMBER") "BM04B-SRSS-TB")
        (field (name "COPYRIGHT") "Copyright (C) 2024 Ultra Librarian. All rights reserved.")
      )
      (libsource (lib "eagle-import") (part "BM04B-SRSS-TBCONN4_BM04B-SRSS_JST"))
    )
    (comp (ref "IC1")
      (value "LIS3MDL")
      (footprint "eagle-import:LGA12_2X2MM")
      (libsource (lib "eagle-import") (part "LIS3MDL"))
    )
    (comp (ref "IC3")
      (value "WM8960")
      (footprint "eagle-import:QFN32_5MM")
      (libsource (lib "eagle-import") (part "WM8960"))
    )
    (comp (ref "J1")
      (value "SM03B-SRSS-TBCONN_SM03B-SRSS-TB_JST")
      (footprint "eagle-import:CONN_SM03B-SRSS-TB_JST")
      (fields
        (field (name "MANUFACTURER_PART_NUMBER") "SM03B-SRSS-TB")
        (field (name "COPYRIGHT") "Copyright (C) 2024 Ultra Librarian. All rights reserved.")
      )
      (libsource (lib "eagle-import") (part "SM03B-SRSS-TBCONN_SM03B-SRSS-TB_JST"))
    )
    (comp (ref "J2")
      (value "C393939")
      (footprint "eagle-import:USB-C-16P")
      (libsource (lib "eagle-import") (part "USB_C16PIN"))
    )
    (comp (ref "J4")
      (value "BM04B-SRSS-TBCONN4_BM04B-SRSS_JST")
      (footprint "eagle-import:CONN4_BM04B-SRSS_JST")
      (fields
        (field (name "MANUFACTURER_PART_NUMBER") "BM04B-SRSS-TB")
        (field (name "COPYRIGHT") "Copyright (C) 2024 Ultra Librarian. All rights reserved.")
      )
      (libsource (lib "eagle-import") (part "BM04B-SRSS-TBCONN4_BM04B-SRSS_JST"))
    )
    (comp (ref "J5")
      (value "BM04B-SRSS-TBCONN4_BM04B-SRSS_JST")
      (footprint "eagle-import:CONN4_BM04B-SRSS_JST")
      (fields
        (field (name "MANUFACTURER_PART_NUMBER") "BM04B-SRSS-TB")
        (field (name "COPYRIGHT") "Copyright (C) 2024 Ultra Librarian. All rights reserved.")
      )
      (libsource (lib "eagle-import") (part "BM04B-SRSS-TBCONN4_BM04B-SRSS_JST"))
    )
    (comp (ref "J6")
      (value "SM04B-SRSS-TBCONN_SM04B-SRSS-TB_JST")
      (footprint "eagle-import:CONN_SM04B-SRSS-TB_JST")
      (fields
        (field (name "MANUFACTURER_PART_NUMBER") "SM04B-SRSS-TB")
        (field (name "COPYRIGHT") "Copyright (C) 2024 Ultra Librarian. All rights reserved.")
      )
      (libsource (lib "eagle-import") (part "SM04B-SRSS-TBCONN_SM04B-SRSS-TB_JST"))
    )
    (comp (ref "L1")
      (value "6.8uH C36410")
      (footprint "eagle-import:INDUCTOR_5X5MM_TDK_VLC5045")
      (libsource (lib "eagle-import") (part "INDUCTORTDK_VLC5045"))
    )
    (comp (ref "L3")
      (value "FNR5012S100MT 10uH")
      (footprint "eagle-import:IND_LQH5BPN2R2NT0L")
      (fields (field (name "MANUFACTURER") "Murata"))
      (libsource (lib "eagle-import") (part "LQH5BPN2R2NT0L"))
    )
    (comp (ref "LED2")
      (value "LED_RED")
      (footprint "eagle-import:LEDC1608X65N_RND-R")
      (libsource (lib "eagle-import") (part "CHIP-ROUND-R_0603"))
    )
    (comp (ref "LED3")
      (value "SYS_POW (19-213/Y2C-CQ2R2L/3T(CY))")
      (footprint "eagle-import:LED-0603")
      (libsource (lib "eagle-import") (part "LED0603"))
    )
    (comp (ref "LOW_BATT")
      (value "LED_RED")
      (footprint "eagle-import:LEDC1608X65N_RND-R")
      (libsource (lib "eagle-import") (part "CHIP-ROUND-R_0603"))
    )
    (comp (ref "LS1")
      (value "CMS-18138A-SP")
      (footprint "eagle-import:CUI_CMS-18138A-SP")
      (fields (field (name "MF") "CUI Devices"))
      (libsource (lib "eagle-import") (part "CMS-18138A-SP"))
    )
    (comp (ref "M.2KEYM(NGFF)")
      (value "1-2199119-5 OR C841645")
      (footprint "eagle-import:TE_1-2199119-5")
      (fields
        (field (name "COMMENT") "1-2199119-5")
        (field (name "DIGIKEY_PART_NUMBER") "A115902TR-ND")
        (field (name "MF") "TE Connectivity")
      )
      (libsource (lib "eagle-import") (part "1-2199119-5"))
    )
    (comp (ref "OSC2")
      (value "ECS-3225MV")
      (footprint "eagle-import:OSC_3.2X2.5MM")
      (libsource (lib "eagle-import") (part "OSCILLATOR3.2X2.5"))
    )
    (comp (ref "Q1")
      (value "SI1308EDL-T1-GE3")
      (footprint "eagle-import:SOT65P210X110-3N")
      (fields (field (name "MF") "Vishay Siliconix"))
      (libsource (lib "eagle-import") (part "SI1308EDL-T1-GE3"))
    )
    (comp (ref "Q2")
      (value "DMG2307L")
      (footprint "eagle-import:SOT96P240X110-3N")
      (fields (field (name "MF") "Diodes Inc."))
      (libsource (lib "eagle-import") (part "DMG2307L"))
    )
    (comp (ref "Q3")
      (value "NMOS_C7465427")
      (footprint "eagle-import:SOT23")
      (libsource (lib "eagle-import") (part "NMOSFETSOT23-GSD"))
    )
    (comp (ref "Q4")
      (value "NMOS_C7465427")
      (footprint "eagle-import:SOT23")
      (libsource (lib "eagle-import") (part "NMOSFETSOT23-GSD"))
    )
    (comp (ref "R1")
      (value "1.87M (TPA2005D1DRBR)")
      (footprint "eagle-import:RESC1005X40")
      (libsource (lib "eagle-import") (part "R-USCHIP-0402(1005-METRIC)_"))
    )
    (comp (ref "R2")
      (value "340K (RTT053403FTP)")
      (footprint "eagle-import:RESC1005X40")
      (libsource (lib "eagle-import") (part "R-USCHIP-0402(1005-METRIC)_"))
    )
    (comp (ref "R3")
      (value "1.87M")
      (footprint "eagle-import:RESC1005X40")
      (libsource (lib "eagle-import") (part "R-USCHIP-0402(1005-METRIC)_"))
    )
    (comp (ref "R4")
      (value "200K")
      (footprint "eagle-import:RESC1005X40")
      (libsource (lib "eagle-import") (part "R-USCHIP-0402(1005-METRIC)_"))
    )
    (comp (ref "R5")
      (value "1K")
      (footprint "eagle-import:RESC1005X40")
      (libsource (lib "eagle-import") (part "R-USCHIP-0402(1005-METRIC)_"))
    )
    (comp (ref "R6")
      (value "590")
      (footprint "eagle-import:RESC1005X40")
      (libsource (lib "eagle-import") (part "R-USCHIP-0402(1005-METRIC)_"))
    )
    (comp (ref "R7")
      (value "1.1k")
      (footprint "eagle-import:RESC1005X40")
      (libsource (lib "eagle-import") (part "R-USCHIP-0402(1005-METRIC)_"))
    )
    (comp (ref "R8")
      (value "1k")
      (footprint "eagle-import:RESC1005X40")
      (libsource (lib "eagle-import") (part "R-USCHIP-0402(1005-METRIC)_"))
    )
    (comp (ref "R9")
      (value "0.47")
      (footprint "eagle-import:RESC1005X40")
      (libsource (lib "eagle-import") (part "R-USCHIP-0402(1005-METRIC)_"))
    )
    (comp (ref "R10")
      (value "1k")
      (footprint "eagle-import:RESC1005X40")
      (libsource (lib "eagle-import") (part "R-USCHIP-0402(1005-METRIC)_"))
    )
    (comp (ref "R11")
      (value "10K")
      (footprint "eagle-import:RESC1005X40")
      (libsource (lib "eagle-import") (part "R-USCHIP-0402(1005-METRIC)_"))
    )
    (comp (ref "R12")
      (value "0.01")
      (footprint "eagle-import:1206")
      (libsource (lib "eagle-import") (part "RESISTOR1206"))
    )
    (comp (ref "R13")
      (value "200K")
      (footprint "eagle-import:RESC1005X40")
      (libsource (lib "eagle-import") (part "R-USCHIP-0402(1005-METRIC)_"))
    )
    (comp (ref "R14")
      (value "1K")
      (footprint "eagle-import:RESC1005X40")
      (libsource (lib "eagle-import") (part "R-USCHIP-0402(1005-METRIC)_"))
    )
    (comp (ref "R15")
      (value "4.7K")
      (footprint "eagle-import:RESC1005X40")
      (libsource (lib "eagle-import") (part "R-USCHIP-0402(1005-METRIC)_"))
    )
    (comp (ref "R16")
      (value "10k")
      (footprint "eagle-import:RESC1005X40")
      (libsource (lib "eagle-import") (part "R-USCHIP-0402(1005-METRIC)_"))
    )
    (comp (ref "R17")
      (value "10k")
      (footprint "eagle-import:RESC1005X40")
      (libsource (lib "eagle-import") (part "R-USCHIP-0402(1005-METRIC)_"))
    )
    (comp (ref "R18")
      (value "4.7K")
      (footprint "eagle-import:RESC1005X40")
      (libsource (lib "eagle-import") (part "R-USCHIP-0402(1005-METRIC)_"))
    )
    (comp (ref "R19")
      (value "5.1K")
      (footprint "eagle-import:RESC1005X40")
      (libsource (lib "eagle-import") (part "R-USCHIP-0402(1005-METRIC)_"))
    )
    (comp (ref "R20")
      (value "1K")
      (footprint "eagle-import:RESC1005X40")
      (libsource (lib "eagle-import") (part "R-USCHIP-0402(1005-METRIC)_"))
    )
    (comp (ref "R21")
      (value "5.1k")
      (footprint "eagle-import:RESC1005X40")
      (libsource (lib "eagle-import") (part "R-USCHIP-0402(1005-METRIC)_"))
    )
    (comp (ref "R22")
      (value "180")
      (footprint "eagle-import:RESC1005X40")
      (libsource (lib "eagle-import") (part "R-USCHIP-0402(1005-METRIC)_"))
    )
    (comp (ref "R23")
      (value "1K")
      (footprint "eagle-import:RESC1005X40")
      (libsource (lib "eagle-import") (part "R-USCHIP-0402(1005-METRIC)_"))
    )
    (comp (ref "R24")
      (value "100k")
      (footprint "eagle-import:RESC1005X40")
      (libsource (lib "eagle-import") (part "R-USCHIP-0402(1005-METRIC)_"))
    )
    (comp (ref "R25")
      (value "4.7K")
      (footprint "eagle-import:RESC1005X40")
      (libsource (lib "eagle-import") (part "R-USCHIP-0402(1005-METRIC)_"))
    )
    (comp (ref "R26")
      (value "4.7K")
      (footprint "eagle-import:RESC1005X40")
      (libsource (lib "eagle-import") (part "R-USCHIP-0402(1005-METRIC)_"))
    )
    (comp (ref "R27")
      (value "10k")
      (footprint "eagle-import:RESC1005X40")
      (libsource (lib "eagle-import") (part "R-USCHIP-0402(1005-METRIC)_"))
    )
    (comp (ref "R28")
      (value "10k")
      (footprint "eagle-import:RESC1005X40")
      (libsource (lib "eagle-import") (part "R-USCHIP-0402(1005-METRIC)_"))
    )
    (comp (ref "R30")
      (value "36k")
      (footprint "eagle-import:RESC1005X40")
      (libsource (lib "eagle-import") (part "R-USCHIP-0402(1005-METRIC)_"))
    )
    (comp (ref "R31")
      (value "27")
      (footprint "eagle-import:RESC1005X40")
      (libsource (lib "eagle-import") (part "R-USCHIP-0402(1005-METRIC)_"))
    )
    (comp (ref "R32")
      (value "27")
      (footprint "eagle-import:RESC1005X40")
      (libsource (lib "eagle-import") (part "R-USCHIP-0402(1005-METRIC)_"))
    )
    (comp (ref "R33")
      (value "10K")
      (footprint "eagle-import:RESC1005X40")
      (libsource (lib "eagle-import") (part "R-USCHIP-0402(1005-METRIC)_"))
    )
    (comp (ref "R34")
      (value "1k")
      (footprint "eagle-import:RESC1005X40")
      (libsource (lib "eagle-import") (part "R-USCHIP-0402(1005-METRIC)_"))
    )
    (comp (ref "R35")
      (value "1k")
      (footprint "eagle-import:RESC1005X40")
      (libsource (lib "eagle-import") (part "R-USCHIP-0402(1005-METRIC)_"))
    )
    (comp (ref "R36")
      (value "200K")
      (footprint "eagle-import:RESC1005X40")
      (libsource (lib "eagle-import") (part "R-USCHIP-0402(1005-METRIC)_"))
    )
    (comp (ref "R37")
      (value "10k")
      (footprint "eagle-import:RESC1005X40")
      (libsource (lib "eagle-import") (part "R-USCHIP-0402(1005-METRIC)_"))
    )
    (comp (ref "R38")
      (value "4.7k")
      (footprint "eagle-import:RESC1005X40")
      (libsource (lib "eagle-import") (part "R-USCHIP-0402(1005-METRIC)_"))
    )
    (comp (ref "R39")
      (value "10k")
      (footprint "eagle-import:RESC1005X40")
      (libsource (lib "eagle-import") (part "R-USCHIP-0402(1005-METRIC)_"))
    )
    (comp (ref "R40")
      (value "4.7K")
      (footprint "eagle-import:RESC1005X40")
      (libsource (lib "eagle-import") (part "R-USCHIP-0402(1005-METRIC)_"))
    )
    (comp (ref "R41")
      (value "47K")
      (footprint "eagle-import:RESC1005X40")
      (libsource (lib "eagle-import") (part "R-USCHIP-0402(1005-METRIC)_"))
    )
    (comp (ref "R42")
      (value "4.7K")
      (footprint "eagle-import:RESC1005X40")
      (libsource (lib "eagle-import") (part "R-USCHIP-0402(1005-METRIC)_"))
    )
    (comp (ref "R43")
      (value "10K")
      (footprint "eagle-import:RESC1005X40")
      (libsource (lib "eagle-import") (part "R-USCHIP-0402(1005-METRIC)_"))
    )
    (comp (ref "R44")
      (value "6.57k")
      (footprint "eagle-import:RESC1005X40")
      (libsource (lib "eagle-import") (part "R-USCHIP-0402(1005-METRIC)_"))
    )
    (comp (ref "RPI-CM1")
      (value "DF40C-100DS-0.4V(51)")
      (footprint "eagle-import:RPI-CM4")
      (libsource (lib "eagle-import") (part "RPI-CM4"))
    )
    (comp (ref "RPIBOOT")
      (value "DNP")
      (footprint "eagle-import:PAD.03X.03")
      (libsource (lib "eagle-import") (part "TEST-POINT3"))
    )
    (comp (ref "RPIBOOT1")
      (value "DNP")
      (footprint "eagle-import:PAD.03X.03")
      (libsource (lib "eagle-import") (part "TEST-POINT3"))
    )
    (comp (ref "RPIBOOT2")
      (value "DNP")
      (footprint "eagle-import:PAD.03X.03")
      (libsource (lib "eagle-import") (part "TEST-POINT3"))
    )
    (comp (ref "RPIBOOT3")
      (value "DNP")
      (footprint "eagle-import:PAD.03X.03")
      (libsource (lib "eagle-import") (part "TEST-POINT3"))
    )
    (comp (ref "RPIBOOT4")
      (value "DNP")
      (footprint "eagle-import:PAD.03X.03")
      (libsource (lib "eagle-import") (part "TEST-POINT3"))
    )
    (comp (ref "RPIBOOT5")
      (value "TEST-POINT3")
      (footprint "eagle-import:PAD.03X.03")
      (libsource (lib "eagle-import") (part "TEST-POINT3"))
    )
    (comp (ref "RPIBOOT6")
      (value "DNP")
      (footprint "eagle-import:PAD.03X.03")
      (libsource (lib "eagle-import") (part "TEST-POINT3"))
    )
    (comp (ref "RPIBOOT7")
      (value "TEST-POINT3")
      (footprint "eagle-import:PAD.03X.03")
      (libsource (lib "eagle-import") (part "TEST-POINT3"))
    )
    (comp (ref "RPIBOOT8")
      (value "DNP")
      (footprint "eagle-import:PAD.03X.03")
      (libsource (lib "eagle-import") (part "TEST-POINT3"))
    )
    (comp (ref "RPIBOOT9")
      (value "DNP")
      (footprint "eagle-import:PAD.03X.03")
      (libsource (lib "eagle-import") (part "TEST-POINT3"))
    )
    (comp (ref "RPIBOOT10")
      (value "DNP")
      (footprint "eagle-import:PAD.03X.03")
      (libsource (lib "eagle-import") (part "TEST-POINT3"))
    )
    (comp (ref "RPIBOOT11")
      (value "DNP")
      (footprint "eagle-import:PAD.03X.03")
      (libsource (lib "eagle-import") (part "TEST-POINT3"))
    )
    (comp (ref "RPIBOOT12")
      (value "DNP")
      (footprint "eagle-import:PAD.03X.03")
      (libsource (lib "eagle-import") (part "TEST-POINT3"))
    )
    (comp (ref "SJ1")
      (value "DNP")
      (footprint "eagle-import:PAD-JUMPER-2-NC_BY_TRACE_YES_SILK")
      (libsource (lib "eagle-import") (part "JUMPER-PAD-2-NC_BY_TRACE"))
    )
    (comp (ref "SJ6")
      (value "DNP")
      (footprint "eagle-import:PAD-JUMPER-2-NC_BY_TRACE_YES_SILK")
      (libsource (lib "eagle-import") (part "JUMPER-PAD-2-NC_BY_TRACE"))
    )
    (comp (ref "T1")
      (value "MMUN2133LT1G")
      (footprint "eagle-import:SC59-BEC")
      (libsource (lib "eagle-import") (part "-PNP_DRIVER-SC59-BECMUN2114T1"))
    )
    (comp (ref "U1")
      (value "TPS61092RSAR")
      (footprint "eagle-import:PVQFN-16")
      (libsource (lib "eagle-import") (part "VREG_TPS6103X"))
    )
    (comp (ref "U2")
      (value "MC74VHC1G14DFT1G")
      (footprint "eagle-import:SOT65P210X110-5N")
      (fields (field (name "MF") "ON Semiconductor"))
      (libsource (lib "eagle-import") (part "MC74VHC1G14DFT1G"))
    )
    (comp (ref "U3")
      (value "BQ27441DRZR-G1A")
      (footprint "eagle-import:PDSO-N12")
      (libsource (lib "eagle-import") (part "BQ27441-G1"))
    )
    (comp (ref "U4")
      (value "BQ24075")
      (footprint "eagle-import:PVQFN-N16")
      (libsource (lib "eagle-import") (part "BQ24075"))
    )
    (comp (ref "U5")
      (value "MC74VHC1G14DFT1G OR C66196")
      (footprint "eagle-import:SOT65P210X110-5N")
      (fields (field (name "MF") "ON Semiconductor") (field (name "MP") "MC74VHC1G14DFT1G"))
      (libsource (lib "eagle-import") (part "MC74VHC1G14DFT1G"))
    )
    (comp (ref "U6")
      (value "LSM6DS3")
      (footprint "eagle-import:LGA-14L")
      (libsource (lib "eagle-import") (part "LSM6DS3"))
    )
    (comp (ref "U7")
      (value "SN74LVC244ARWPRRWP0020A")
      (footprint "eagle-import:RWP0020A")
      (fields
        (field (name "MANUFACTURER_PART_NUMBER") "SN74LVC244ARWPR")
        (field (name "COPYRIGHT") "Copyright (C) 2024 Ultra Librarian. All rights reserved.")
      )
      (libsource (lib "eagle-import") (part "SN74LVC244ARWPRRWP0020A"))
    )
    (comp (ref "U9")
      (value "EMC2301-1-ACZL-TRMSOP8_MC_MCH-L")
      (footprint "eagle-import:MSOP8_MC_MCH-L")
      (fields
        (field (name "MANUFACTURER_PART_NUMBER") "EMC2301-1-ACZL-TR")
        (field (name "COPYRIGHT") "Copyright (C) 2024 Ultra Librarian. All rights reserved.")
      )
      (libsource (lib "eagle-import") (part "EMC2301-1-ACZL-TRMSOP8_MC_MCH-L"))
    )
    (comp (ref "U10")
      (value "AP2112-3.3K")
      (footprint "eagle-import:SOT23-5")
      (libsource (lib "eagle-import") (part "VREG_SOT23-5"))
    )
    (comp (ref "U11")
      (value "AP2112-3.3K")
      (footprint "eagle-import:SOT23-5")
      (libsource (lib "eagle-import") (part "VREG_SOT23-5"))
    )
    (comp (ref "U12")
      (value "C233266")
      (footprint "eagle-import:XDCR_SPU0410LR5H-QB")
      (fields (field (name "MANUFACTURER") "KNOWLES"))
      (libsource (lib "eagle-import") (part "SPU0410LR5H-QB"))
    )
    (comp (ref "U13")
      (value "TPD4EUSB30DQARDQA10")
      (footprint "eagle-import:DQA10")
      (fields
        (field (name "MANUFACTURER_PART_NUMBER") "TPD4EUSB30DQAR")
        (field (name "COPYRIGHT") "Copyright (C) 2024 Ultra Librarian. All rights reserved.")
      )
      (libsource (lib "eagle-import") (part "TPD4EUSB30DQARDQA10"))
    )
    (comp (ref "U14")
      (value "OPA344")
      (footprint "eagle-import:SOT23-5")
      (libsource (lib "eagle-import") (part "OPA344"))
    )
    (comp (ref "U15")
      (value "AP2112-3.3K")
      (footprint "eagle-import:SOT23-5")
      (libsource (lib "eagle-import") (part "VREG_SOT23-5"))
    )
    (comp (ref "U16")
      (value "W25Q16JVUXIQ_TR")
      (footprint "eagle-import:PSON50P300X200X60-9N")
      (fields (field (name "MANUFACTURER") "Winbond"))
      (libsource (lib "eagle-import") (part "W25Q16JVUXIQ_TR"))
    )
    (comp (ref "U17")
      (value "TPD1E1B04DPYRDPY2_TEX")
      (footprint "eagle-import:DPY2_TEX")
      (fields
        (field (name "MANUFACTURER_PART_NUMBER") "TPD1E1B04DPYR")
        (field (name "COPYRIGHT") "Copyright (C) 2024 Ultra Librarian. All rights reserved.")
      )
      (libsource (lib "eagle-import") (part "TPD1E1B04DPYRDPY2_TEX"))
    )
    (comp (ref "U18")
      (value "TPD1E1B04DPYRDPY2_TEX")
      (footprint "eagle-import:DPY2_TEX")
      (fields
        (field (name "MANUFACTURER_PART_NUMBER") "TPD1E1B04DPYR")
        (field (name "COPYRIGHT") "Copyright (C) 2024 Ultra Librarian. All rights reserved.")
      )
      (libsource (lib "eagle-import") (part "TPD1E1B04DPYRDPY2_TEX"))
    )
    (comp (ref "U19")
      (value "TPD1E1B04DPYRDPY2_TEX")
      (footprint "eagle-import:DPY2_TEX")
      (fields
        (field (name "MANUFACTURER_PART_NUMBER") "TPD1E1B04DPYR")
        (field (name "COPYRIGHT") "Copyright (C) 2024 Ultra Librarian. All rights reserved.")
      )
      (libsource (lib "eagle-import") (part "TPD1E1B04DPYRDPY2_TEX"))
    )
    (comp (ref "U20")
      (value "TPD1E1B04DPYRDPY2_TEX")
      (footprint "eagle-import:DPY2_TEX")
      (fields
        (field (name "MANUFACTURER_PART_NUMBER") "TPD1E1B04DPYR")
        (field (name "COPYRIGHT") "Copyright (C) 2024 Ultra Librarian. All rights reserved.")
      )
      (libsource (lib "eagle-import") (part "TPD1E1B04DPYRDPY2_TEX"))
    )
    (comp (ref "U21")
      (value "TPD1E1B04DPYRDPY2_TEX")
      (footprint "eagle-import:DPY2_TEX")
      (fields
        (field (name "MANUFACTURER_PART_NUMBER") "TPD1E1B04DPYR")
        (field (name "COPYRIGHT") "Copyright (C) 2024 Ultra Librarian. All rights reserved.")
      )
      (libsource (lib "eagle-import") (part "TPD1E1B04DPYRDPY2_TEX"))
    )
    (comp (ref "U22")
      (value "TPD1E1B04DPYRDPY2_TEX")
      (footprint "eagle-import:DPY2_TEX")
      (fields
        (field (name "MANUFACTURER_PART_NUMBER") "TPD1E1B04DPYR")
        (field (name "COPYRIGHT") "Copyright (C) 2024 Ultra Librarian. All rights reserved.")
      )
      (libsource (lib "eagle-import") (part "TPD1E1B04DPYRDPY2_TEX"))
    )
    (comp (ref "U23")
      (value "TPD1E1B04DPYRDPY2_TEX")
      (footprint "eagle-import:DPY2_TEX")
      (fields
        (field (name "MANUFACTURER_PART_NUMBER") "TPD1E1B04DPYR")
        (field (name "COPYRIGHT") "Copyright (C) 2024 Ultra Librarian. All rights reserved.")
      )
      (libsource (lib "eagle-import") (part "TPD1E1B04DPYRDPY2_TEX"))
    )
    (comp (ref "U24")
      (value "TPD1E1B04DPYRDPY2_TEX")
      (footprint "eagle-import:DPY2_TEX")
      (fields
        (field (name "MANUFACTURER_PART_NUMBER") "TPD1E1B04DPYR")
        (field (name "COPYRIGHT") "Copyright (C) 2024 Ultra Librarian. All rights reserved.")
      )
      (libsource (lib "eagle-import") (part "TPD1E1B04DPYRDPY2_TEX"))
    )
    (comp (ref "U25")
      (value "DRV2605LDGSR")
      (footprint "eagle-import:SOP50P490X110-10N")
      (fields (field (name "MANUFACTURER") "Texas Instruments"))
      (libsource (lib "eagle-import") (part "DRV2605LDGSR"))
    )
    (comp (ref "USB2.0MUX")
      (value "TS3USB30RSWR")
      (footprint "eagle-import:10-UFQFN")
      (fields (field (name "DIGI-KEY_PART_NUMBER") "296-22547-2-ND") (field (name "MF") "Texas Instruments"))
      (libsource (lib "eagle-import") (part "TS3USB30RSWR"))
    )
    (comp (ref "USB_BOOT_N")
      (value "DNP")
      (footprint "eagle-import:PAD.03X.03")
      (libsource (lib "eagle-import") (part "TEST-POINT3"))
    )
    (comp (ref "Y1")
      (value "ABM8-272-T3")
      (footprint "eagle-import:ABM8272T3")
      (fields (field (name "MOUSER_PART_NUMBER") "815-ABM8-272-T3"))
      (libsource (lib "eagle-import") (part "ABM8-272-T3"))
    )
  )
  (nets
    (net (code "1") (name "/1V8BQ") (class "Default")
      (node (ref "C20") (pin "1") (pinfunction "1_1") (pintype "passive"))
      (node (ref "U3") (pin "5") (pinfunction "VDD_5") (pintype "bidirectional"))
    )
    (net (code "2") (name "/2A3") (class "Default")
      (node (ref "U7") (pin "14") (pinfunction "2A3_14") (pintype "input"))
    )
    (net (code "3") (name "/2A4") (class "Default")
      (node (ref "U7") (pin "16") (pinfunction "2A4_16") (pintype "input"))
    )
    (net (code "4") (name "/2Y3") (class "Default")
      (node (ref "U7") (pin "4") (pinfunction "2Y3_4") (pintype "output"))
    )
    (net (code "5") (name "/2Y4") (class "Default")
      (node (ref "U7") (pin "2") (pinfunction "2Y4_2") (pintype "output"))
    )
    (net (code "6") (name "/AUDIO_MCLK") (class "Default")
      (node (ref "IC3") (pin "11") (pinfunction "MCLK_11") (pintype "input"))
      (node (ref "OSC2") (pin "3") (pinfunction "OUT_3") (pintype "output"))
    )
    (net (code "7") (name "/BUTTON_D") (class "Default")
      (node (ref "BUD") (pin "2_1") (pinfunction "2_2_1") (pintype "passive"))
      (node (ref "BUD") (pin "2_2") (pinfunction "2_2_2") (pintype "passive"))
      (node (ref "C2040") (pin "29") (pinfunction "GPIO18_29") (pintype "bidirectional"))
    )
    (net (code "8") (name "/BUTTON_S") (class "Default")
      (node (ref "BUS") (pin "2_1") (pinfunction "2_2_1") (pintype "passive"))
      (node (ref "BUS") (pin "2_2") (pinfunction "2_2_2") (pintype "passive"))
      (node (ref "C2040") (pin "27") (pinfunction "GPIO16_27") (pintype "bidirectional"))
    )
    (net (code "9") (name "/BUTTON_U") (class "Default")
      (node (ref "BUP") (pin "2_1") (pinfunction "2_2_1") (pintype "passive"))
      (node (ref "BUP") (pin "2_2") (pinfunction "2_2_2") (pintype "passive"))
      (node (ref "C2040") (pin "28") (pinfunction "GPIO17_28") (pintype "bidirectional"))
    )
    (net (code "10") (name "/CAM0_C_N") (class "Default")
      (node (ref "RPI-CM1") (pin "140") (pinfunction "CAM0_C_N_140") (pintype "passive"))
    )
    (net (code "11") (name "/CAM0_C_P") (class "Default")
      (node (ref "RPI-CM1") (pin "142") (pinfunction "CAM0_C_P_142") (pintype "passive"))
    )
    (net (code "12") (name "/CAM0_D0_N") (class "Default")
      (node (ref "RPI-CM1") (pin "128") (pinfunction "CAM0_D0_N_128") (pintype "passive"))
    )
    (net (code "13") (name "/CAM0_D0_P") (class "Default")
      (node (ref "RPI-CM1") (pin "130") (pinfunction "CAM0_D0_P_130") (pintype "passive"))
    )
    (net (code "14") (name "/CAM0_D1_N") (class "Default")
      (node (ref "RPI-CM1") (pin "134") (pinfunction "CAM0_D1_N_134") (pintype "passive"))
    )
    (net (code "15") (name "/CAM0_D1_P") (class "Default")
      (node (ref "RPI-CM1") (pin "136") (pinfunction "CAM0_D1_P_136") (pintype "passive"))
    )
    (net (code "16") (name "/CAM1_C_N") (class "Default")
      (node (ref "CAMERA") (pin "8") (pinfunction "8_8") (pintype "passive"))
      (node (ref "RPI-CM1") (pin "127") (pinfunction "CAM1_C_N_127") (pintype "passive"))
    )
    (net (code "17") (name "/CAM1_C_P") (class "Default")
      (node (ref "CAMERA") (pin "9") (pinfunction "9_9") (pintype "passive"))
      (node (ref "RPI-CM1") (pin "129") (pinfunction "CAM1_C_P_129") (pintype "passive"))
    )
    (net (code "18") (name "/CAM1_D0_N") (class "Default")
      (node (ref "CAMERA") (pin "2") (pinfunction "2_2") (pintype "passive"))
      (node (ref "RPI-CM1") (pin "115") (pinfunction "CAM1_D0_N_115") (pintype "passive"))
    )
    (net (code "19") (name "/CAM1_D0_P") (class "Default")
      (node (ref "CAMERA") (pin "3") (pinfunction "3_3") (pintype "passive"))
      (node (ref "RPI-CM1") (pin "117") (pinfunction "CAM1_D0_P_117") (pintype "passive"))
    )
    (net (code "20") (name "/CAM1_D1_N") (class "Default")
      (node (ref "CAMERA") (pin "5") (pinfunction "5_5") (pintype "passive"))
      (node (ref "RPI-CM1") (pin "121") (pinfunction "CAM1_D1_N_121") (pintype "passive"))
    )
    (net (code "21") (name "/CAM1_D1_P") (class "Default")
      (node (ref "CAMERA") (pin "6") (pinfunction "6_6") (pintype "passive"))
      (node (ref "RPI-CM1") (pin "123") (pinfunction "CAM1_D1_P_123") (pintype "passive"))
    )
    (net (code "22") (name "/CAM1_D2_N") (class "Default")
      (node (ref "CAMERA") (pin "11") (pinfunction "11_11") (pintype "passive"))
      (node (ref "RPI-CM1") (pin "133") (pinfunction "CAM1_D2_N_133") (pintype "passive"))
    )
    (net (code "23") (name "/CAM1_D2_P") (class "Default")
      (node (ref "CAMERA") (pin "12") (pinfunction "12_12") (pintype "passive"))
      (node (ref "RPI-CM1") (pin "135") (pinfunction "CAM1_D2_P_135") (pintype "passive"))
    )
    (net (code "24") (name "/CAM1_D3_N") (class "Default")
      (node (ref "CAMERA") (pin "14") (pinfunction "14_14") (pintype "passive"))
      (node (ref "RPI-CM1") (pin "139") (pinfunction "CAM1_D3_N_139") (pintype "passive"))
    )
    (net (code "25") (name "/CAM1_D3_P") (class "Default")
      (node (ref "CAMERA") (pin "15") (pinfunction "15_15") (pintype "passive"))
      (node (ref "RPI-CM1") (pin "141") (pinfunction "CAM1_D3_P_141") (pintype "passive"))
    )
    (net (code "26") (name "/CAM_GPIO") (class "Default")
      (node (ref "CAMERA") (pin "17") (pinfunction "17_17") (pintype "passive"))
      (node (ref "RPI-CM1") (pin "97") (pinfunction "CAMERA_GPIO_97") (pintype "passive"))
    )
    (net (code "27") (name "/CDD") (class "Default")
      (node (ref "C10") (pin "1") (pinfunction "1_1") (pintype "passive"))
      (node (ref "EINK_524352471") (pin "7") (pinfunction "7_7") (pintype "passive"))
    )
    (net (code "28") (name "/DSI0_C_N") (class "Default")
      (node (ref "RPI-CM1") (pin "169") (pinfunction "DSI0_C_N_169") (pintype "passive"))
    )
    (net (code "29") (name "/DSI0_C_P") (class "Default")
      (node (ref "RPI-CM1") (pin "171") (pinfunction "DSI0_C_P_171") (pintype "passive"))
    )
    (net (code "30") (name "/DSI0_D0_N") (class "Default")
      (node (ref "RPI-CM1") (pin "157") (pinfunction "DSI0_D0_N_157") (pintype "passive"))
    )
    (net (code "31") (name "/DSI0_D0_P") (class "Default")
      (node (ref "RPI-CM1") (pin "159") (pinfunction "DSI0_D0_P_159") (pintype "passive"))
    )
    (net (code "32") (name "/DSI0_D1_N") (class "Default")
      (node (ref "RPI-CM1") (pin "163") (pinfunction "DSI0_D1_N_163") (pintype "passive"))
    )
    (net (code "33") (name "/DSI0_D1_P") (class "Default")
      (node (ref "RPI-CM1") (pin "165") (pinfunction "DSI0_D1_P_165") (pintype "passive"))
    )
    (net (code "34") (name "/DSI1_C_N") (class "Default")
      (node (ref "RPI-CM1") (pin "187") (pinfunction "DSI1_C_N_187") (pintype "passive"))
    )
    (net (code "35") (name "/DSI1_C_P") (class "Default")
      (node (ref "RPI-CM1") (pin "189") (pinfunction "DSI1_C_P_189") (pintype "passive"))
    )
    (net (code "36") (name "/DSI1_D0_N") (class "Default")
      (node (ref "RPI-CM1") (pin "175") (pinfunction "DSI1_D0_N_175") (pintype "passive"))
    )
    (net (code "37") (name "/DSI1_D0_P") (class "Default")
      (node (ref "RPI-CM1") (pin "177") (pinfunction "DSI1_D0_P_177") (pintype "passive"))
    )
    (net (code "38") (name "/DSI1_D1_N") (class "Default")
      (node (ref "RPI-CM1") (pin "181") (pinfunction "DSI1_D1_N_181") (pintype "passive"))
    )
    (net (code "39") (name "/DSI1_D1_P") (class "Default")
      (node (ref "RPI-CM1") (pin "183") (pinfunction "DSI1_D1_P_183") (pintype "passive"))
    )
    (net (code "40") (name "/DSI1_D2_N") (class "Default")
      (node (ref "RPI-CM1") (pin "193") (pinfunction "DSI1_D2_N_193") (pintype "passive"))
    )
    (net (code "41") (name "/DSI1_D2_P") (class "Default")
      (node (ref "RPI-CM1") (pin "195") (pinfunction "DSI1_D2_P_195") (pintype "passive"))
    )
    (net (code "42") (name "/DSI1_D3_N") (class "Default")
      (node (ref "RPI-CM1") (pin "194") (pinfunction "DSI1_D3_N_194") (pintype "passive"))
    )
    (net (code "43") (name "/DSI1_D3_P") (class "Default")
      (node (ref "RPI-CM1") (pin "196") (pinfunction "DSI1_D3_P_196") (pintype "passive"))
    )
    (net (code "44") (name "/EINK_BUSY") (class "Default")
      (node (ref "C2040") (pin "13") (pinfunction "GPIO10_13") (pintype "bidirectional"))
      (node (ref "EINK_524352471") (pin "16") (pinfunction "16_16") (pintype "passive"))
      (node (ref "RPIBOOT9") (pin "P$1") (pinfunction "1_P$1") (pintype "bidirectional"))
      (node (ref "U18") (pin "2") (pinfunction "I/O_2") (pintype "passive"))
      (node (ref "U7") (pin "1") (pinfunction "1A1_1") (pintype "input"))
    )
    (net (code "45") (name "/EINK_CS") (class "Default")
      (node (ref "C2040") (pin "16") (pinfunction "GPIO13_16") (pintype "bidirectional"))
      (node (ref "EINK_524352471") (pin "13") (pinfunction "13_13") (pintype "passive"))
      (node (ref "GND41") (pin "P$1") (pinfunction "1_P$1") (pintype "bidirectional"))
      (node (ref "U20") (pin "2") (pinfunction "I/O_2") (pintype "passive"))
      (node (ref "U7") (pin "11") (pinfunction "1Y4_11") (pintype "output"))
    )
    (net (code "46") (name "/EINK_D{slash}C") (class "Default")
      (node (ref "C2040") (pin "15") (pinfunction "GPIO12_15") (pintype "bidirectional"))
      (node (ref "EINK_524352471") (pin "14") (pinfunction "14_14") (pintype "passive"))
      (node (ref "RPIBOOT10") (pin "P$1") (pinfunction "1_P$1") (pintype "bidirectional"))
      (node (ref "U19") (pin "2") (pinfunction "I/O_2") (pintype "passive"))
      (node (ref "U7") (pin "13") (pinfunction "1Y3_13") (pintype "output"))
    )
    (net (code "47") (name "/EINK_RESET") (class "Default")
      (node (ref "C2040") (pin "14") (pinfunction "GPIO11_14") (pintype "bidirectional"))
      (node (ref "EINK_524352471") (pin "15") (pinfunction "15_15") (pintype "passive"))
      (node (ref "GND40") (pin "P$1") (pinfunction "1_P$1") (pintype "bidirectional"))
      (node (ref "U17") (pin "2") (pinfunction "I/O_2") (pintype "passive"))
      (node (ref "U7") (pin "15") (pinfunction "1Y2_15") (pintype "output"))
    )
    (net (code "48") (name "/FAN_PWM") (class "Default")
      (node (ref "J6") (pin "1") (pinfunction "1_1") (pintype "passive"))
      (node (ref "U9") (pin "5") (pinfunction "PWM_5") (pintype "output"))
    )
    (net (code "49") (name "/GDR") (class "Default")
      (node (ref "EINK_524352471") (pin "23") (pinfunction "23_23") (pintype "passive"))
      (node (ref "Q1") (pin "1") (pinfunction "G_1") (pintype "bidirectional"))
      (node (ref "R11") (pin "2") (pinfunction "2_2") (pintype "passive"))
    )
    (net (code "50") (name "/GND_2") (class "Default")
      (node (ref "U13") (pin "3") (pinfunction "GND_2_3") (pintype "power_in"))
    )
    (net (code "51") (name "/HDMI0_CEC") (class "Default")
      (node (ref "RPI-CM1") (pin "151") (pinfunction "HDMI0_CEC_151") (pintype "passive"))
    )
    (net (code "52") (name "/HDMI0_CLK_N") (class "Default")
      (node (ref "RPI-CM1") (pin "190") (pinfunction "HDMI0_CLK_N_190") (pintype "passive"))
    )
    (net (code "53") (name "/HDMI0_CLK_P") (class "Default")
      (node (ref "RPI-CM1") (pin "188") (pinfunction "HDMI0_CLK_P_188") (pintype "passive"))
    )
    (net (code "54") (name "/HDMI0_HOTPLUG") (class "Default")
      (node (ref "RPI-CM1") (pin "153") (pinfunction "HDMI0_HOTPLUG_153") (pintype "passive"))
    )
    (net (code "55") (name "/HDMI0_SCL") (class "Default")
      (node (ref "RPI-CM1") (pin "200") (pinfunction "HDMI0_SCL_200") (pintype "passive"))
    )
    (net (code "56") (name "/HDMI0_SDA") (class "Default")
      (node (ref "RPI-CM1") (pin "199") (pinfunction "HDMI0_SDA_199") (pintype "passive"))
    )
    (net (code "57") (name "/HDMI0_TX0_N") (class "Default")
      (node (ref "RPI-CM1") (pin "184") (pinfunction "HDMI0_TX0_N_184") (pintype "passive"))
    )
    (net (code "58") (name "/HDMI0_TX0_P") (class "Default")
      (node (ref "RPI-CM1") (pin "182") (pinfunction "HDMI0_TX0_P_182") (pintype "passive"))
    )
    (net (code "59") (name "/HDMI0_TX1_N") (class "Default")
      (node (ref "RPI-CM1") (pin "178") (pinfunction "HDMI0_TX1_N_178") (pintype "passive"))
    )
    (net (code "60") (name "/HDMI0_TX1_P") (class "Default")
      (node (ref "RPI-CM1") (pin "176") (pinfunction "HDMI0_TX1_P_176") (pintype "passive"))
    )
    (net (code "61") (name "/HDMI0_TX2_N") (class "Default")
      (node (ref "RPI-CM1") (pin "172") (pinfunction "HDMI0_TX2_N_172") (pintype "passive"))
    )
    (net (code "62") (name "/HDMI0_TX2_P") (class "Default")
      (node (ref "RPI-CM1") (pin "170") (pinfunction "HDMI0_TX2_P_170") (pintype "passive"))
    )
    (net (code "63") (name "/HDMI1_CEC") (class "Default")
      (node (ref "RPI-CM1") (pin "149") (pinfunction "HDMI1_CEC_149") (pintype "passive"))
    )
    (net (code "64") (name "/HDMI1_CLK_N") (class "Default")
      (node (ref "RPI-CM1") (pin "166") (pinfunction "HDMI1_CLK_N_166") (pintype "passive"))
    )
    (net (code "65") (name "/HDMI1_CLK_P") (class "Default")
      (node (ref "RPI-CM1") (pin "164") (pinfunction "HDMI1_CLK_P_164") (pintype "passive"))
    )
    (net (code "66") (name "/HDMI1_HOTPLUG") (class "Default")
      (node (ref "RPI-CM1") (pin "143") (pinfunction "HDMI1_HOTPLUG_143") (pintype "passive"))
    )
    (net (code "67") (name "/HDMI1_SCL") (class "Default")
      (node (ref "RPI-CM1") (pin "147") (pinfunction "HDMI1_SCL_147") (pintype "passive"))
    )
    (net (code "68") (name "/HDMI1_SDA") (class "Default")
      (node (ref "RPI-CM1") (pin "145") (pinfunction "HDMI1_SDA_145") (pintype "passive"))
    )
    (net (code "69") (name "/HDMI1_TX0_N") (class "Default")
      (node (ref "RPI-CM1") (pin "160") (pinfunction "HDMI1_TX0_N_160") (pintype "passive"))
    )
    (net (code "70") (name "/HDMI1_TX0_P") (class "Default")
      (node (ref "RPI-CM1") (pin "158") (pinfunction "HDMI1_TX0_P_158") (pintype "passive"))
    )
    (net (code "71") (name "/HDMI1_TX1_N") (class "Default")
      (node (ref "RPI-CM1") (pin "154") (pinfunction "HDMI1_TX1_N_154") (pintype "passive"))
    )
    (net (code "72") (name "/HDMI1_TX1_P") (class "Default")
      (node (ref "RPI-CM1") (pin "152") (pinfunction "HDMI1_TX1_P_152") (pintype "passive"))
    )
    (net (code "73") (name "/HDMI1_TX2_N") (class "Default")
      (node (ref "RPI-CM1") (pin "148") (pinfunction "HDMI1_TX2_N_148") (pintype "passive"))
    )
    (net (code "74") (name "/HDMI1_TX2_P") (class "Default")
      (node (ref "RPI-CM1") (pin "146") (pinfunction "HDMI1_TX2_P_146") (pintype "passive"))
    )
    (net (code "75") (name "/I2S_BCLK") (class "Default")
      (node (ref "IC3") (pin "12") (pinfunction "BCLK_12") (pintype "bidirectional"))
      (node (ref "RPI-CM1") (pin "49") (pinfunction "GPIO18_49") (pintype "passive"))
    )
    (net (code "76") (name "/I2S_DIN") (class "Default")
      (node (ref "IC3") (pin "16") (pinfunction "ADCDAT_16") (pintype "input"))
      (node (ref "RPI-CM1") (pin "27") (pinfunction "GPIO20_27") (pintype "passive"))
    )
    (net (code "77") (name "/I2S_DOUT") (class "Default")
      (node (ref "IC3") (pin "14") (pinfunction "DACDAT_14") (pintype "bidirectional"))
      (node (ref "RPI-CM1") (pin "25") (pinfunction "GPIO21_25") (pintype "passive"))
    )
    (net (code "78") (name "/I2S_LRCLK") (class "Default")
      (node (ref "IC3") (pin "13") (pinfunction "DACLRC_13") (pintype "bidirectional"))
      (node (ref "IC3") (pin "15") (pinfunction "ADCLRC/GPIO1_15") (pintype "bidirectional"))
      (node (ref "RPI-CM1") (pin "26") (pinfunction "GPIO19_26") (pintype "passive"))
    )
    (net (code "79") (name "/LBO") (class "Default")
      (node (ref "T1") (pin "B") (pinfunction "B_B") (pintype "passive"))
      (node (ref "U1") (pin "12") (pinfunction "LBO_12") (pintype "output"))
    )
    (net (code "80") (name "/LEFT_N") (class "Default")
      (node (ref "C64") (pin "1") (pinfunction "1_1") (pintype "passive"))
      (node (ref "FB3") (pin "2") (pinfunction "2_2") (pintype "passive"))
      (node (ref "LS1") (pin "N") (pinfunction "N_N") (pintype "passive"))
    )
    (net (code "81") (name "/LEFT_P") (class "Default")
      (node (ref "C63") (pin "1") (pinfunction "1_1") (pintype "passive"))
      (node (ref "FB2") (pin "2") (pinfunction "2_2") (pintype "passive"))
      (node (ref "LS1") (pin "P") (pinfunction "P_P") (pintype "passive"))
    )
    (net (code "82") (name "/MICBIAS") (class "Default")
      (node (ref "C46") (pin "1") (pinfunction "1_1") (pintype "passive"))
      (node (ref "C48") (pin "1") (pinfunction "1_1") (pintype "passive"))
      (node (ref "IC3") (pin "1") (pinfunction "MICBIAS_1") (pintype "output"))
    )
    (net (code "83") (name "/NC") (class "Default")
      (node (ref "EINK_524352471") (pin "24") (pinfunction "24_24") (pintype "passive"))
    )
    (net (code "84") (name "/N_RPIBOOT") (class "Default")
      (node (ref "RPI-CM1") (pin "93") (pinfunction "~{RPIBOOT}_93") (pintype "passive"))
      (node (ref "RPIBOOT") (pin "P$1") (pinfunction "1_P$1") (pintype "bidirectional"))
    )
    (net (code "85") (name "/PCIE_CLK_N") (class "Default")
      (node (ref "M.2KEYM(NGFF)") (pin "53") (pinfunction "P53_53") (pintype "passive"))
      (node (ref "RPI-CM1") (pin "112") (pinfunction "PCIE_CLK_N_112") (pintype "passive"))
    )
    (net (code "86") (name "/PCIE_CLK_P") (class "Default")
      (node (ref "M.2KEYM(NGFF)") (pin "55") (pinfunction "P55_55") (pintype "passive"))
      (node (ref "RPI-CM1") (pin "110") (pinfunction "PCIE_CLK_P_110") (pintype "passive"))
    )
    (net (code "87") (name "/PCIE_CLK_~{REQ}") (class "Default")
      (node (ref "M.2KEYM(NGFF)") (pin "52") (pinfunction "P52_52") (pintype "passive"))
      (node (ref "RPI-CM1") (pin "102") (pinfunction "PCIE_CLK_~{REQ}_102") (pintype "passive"))
    )
    (net (code "88") (name "/PCIE_RX_N") (class "Default")
      (node (ref "M.2KEYM(NGFF)") (pin "41") (pinfunction "P41_41") (pintype "passive"))
      (node (ref "RPI-CM1") (pin "118") (pinfunction "PCIE_RX_N_118") (pintype "passive"))
    )
    (net (code "89") (name "/PCIE_RX_P") (class "Default")
      (node (ref "M.2KEYM(NGFF)") (pin "43") (pinfunction "P43_43") (pintype "passive"))
      (node (ref "RPI-CM1") (pin "116") (pinfunction "PCIE_RX_P_116") (pintype "passive"))
    )
    (net (code "90") (name "/PCIE_TX_N") (class "Default")
      (node (ref "M.2KEYM(NGFF)") (pin "47") (pinfunction "P47_47") (pintype "passive"))
      (node (ref "RPI-CM1") (pin "124") (pinfunction "PCIE_TX_N_124") (pintype "passive"))
    )
    (net (code "91") (name "/PCIE_TX_P") (class "Default")
      (node (ref "M.2KEYM(NGFF)") (pin "49") (pinfunction "P49_49") (pintype "passive"))
      (node (ref "RPI-CM1") (pin "122") (pinfunction "PCIE_TX_P_122") (pintype "passive"))
    )
    (net (code "92") (name "/PCIE_~{RST}") (class "Default")
      (node (ref "M.2KEYM(NGFF)") (pin "50") (pinfunction "P50_50") (pintype "passive"))
      (node (ref "RPI-CM1") (pin "109") (pinfunction "PCIE_~{RST}_109") (pintype "passive"))
    )
    (net (code "93") (name "/PI_1V8") (class "Default")
      (node (ref "RPI-CM1") (pin "88") (pinfunction "CM4_1.8V(OUTPUT)_88") (pintype "passive"))
      (node (ref "RPI-CM1") (pin "90") (pinfunction "CM4_1.8V(OUTPUT)_90") (pintype "passive"))
    )
    (net (code "94") (name "/RESE") (class "Default")
      (node (ref "EINK_524352471") (pin "22") (pinfunction "22_22") (pintype "passive"))
      (node (ref "Q1") (pin "2") (pinfunction "S_2") (pintype "bidirectional"))
      (node (ref "R9") (pin "2") (pinfunction "2_2") (pintype "passive"))
    )
    (net (code "95") (name "/RESERVED@104") (class "Default")
      (node (ref "RPI-CM1") (pin "104") (pinfunction "RESERVED_104") (pintype "passive"))
    )
    (net (code "96") (name "/RESERVED@106") (class "Default")
      (node (ref "RPI-CM1") (pin "106") (pinfunction "RESERVED_106") (pintype "passive"))
    )
    (net (code "97") (name "/RINPUT1") (class "Default")
      (node (ref "C27") (pin "2") (pinfunction "2_2") (pintype "passive"))
      (node (ref "IC3") (pin "5") (pinfunction "RINPUT1_5") (pintype "input"))
      (node (ref "R39") (pin "1") (pinfunction "1_1") (pintype "passive"))
      (node (ref "U14") (pin "1") (pinfunction "OUT_1") (pintype "output"))
    )
    (net (code "98") (name "/SAM_BOOT") (class "Default")
      (node (ref "Q4") (pin "1") (pinfunction "G_1") (pintype "passive"))
      (node (ref "RPI-CM1") (pin "29") (pinfunction "GPIO16_29") (pintype "passive"))
    )
    (net (code "99") (name "/SAM_EINK_PWR") (class "Default")
      (node (ref "C2040") (pin "12") (pinfunction "GPIO9_12") (pintype "bidirectional"))
      (node (ref "U5") (pin "2") (pinfunction "IN_A_2") (pintype "input"))
    )
    (net (code "100") (name "/SAM_EINK_SWITCH") (class "Default")
      (node (ref "C2040") (pin "34") (pinfunction "GPIO22_34") (pintype "bidirectional"))
      (node (ref "U7") (pin "18") (pinfunction "2OE_N_18") (pintype "input"))
      (node (ref "U7") (pin "20") (pinfunction "1OE_N_20") (pintype "input"))
    )
    (net (code "101") (name "/SAM_GPIO3") (class "Default")
      (node (ref "C2040") (pin "5") (pinfunction "GPIO3_5") (pintype "bidirectional"))
    )
    (net (code "102") (name "/SAM_GPIO4") (class "Default")
      (node (ref "C2040") (pin "6") (pinfunction "GPIO4_6") (pintype "bidirectional"))
    )
    (net (code "103") (name "/SAM_GPIO5") (class "Default")
      (node (ref "C2040") (pin "7") (pinfunction "GPIO5_7") (pintype "bidirectional"))
    )
    (net (code "104") (name "/SAM_GPIO6") (class "Default")
      (node (ref "C2040") (pin "8") (pinfunction "GPIO6_8") (pintype "bidirectional"))
    )
    (net (code "105") (name "/SAM_GPIO7") (class "Default")
      (node (ref "C2040") (pin "9") (pinfunction "GPIO7_9") (pintype "bidirectional"))
    )
    (net (code "106") (name "/SAM_GPIO8") (class "Default")
      (node (ref "C2040") (pin "11") (pinfunction "GPIO8_11") (pintype "bidirectional"))
    )
    (net (code "107") (name "/SAM_GPIO23") (class "Default")
      (node (ref "C2040") (pin "35") (pinfunction "GPIO23_35") (pintype "bidirectional"))
    )
    (net (code "108") (name "/SAM_GPIO26{slash}ADC0") (class "Default")
      (node (ref "C2040") (pin "38") (pinfunction "GPIO26/ADC0_38") (pintype "bidirectional"))
    )
    (net (code "109") (name "/SAM_GPIO27{slash}ADC1") (class "Default")
      (node (ref "C2040") (pin "39") (pinfunction "GPIO27/ADC1_39") (pintype "bidirectional"))
    )
    (net (code "110") (name "/SAM_GPIO28{slash}ADC2") (class "Default")
      (node (ref "C2040") (pin "40") (pinfunction "GPIO28/ADC2_40") (pintype "bidirectional"))
    )
    (net (code "111") (name "/SAM_GPIO29{slash}ADC3") (class "Default")
      (node (ref "C2040") (pin "41") (pinfunction "GPIO29/ADC3_41") (pintype "bidirectional"))
    )
    (net (code "112") (name "/SAM_INTERUPT") (class "Default")
      (node (ref "C2040") (pin "4") (pinfunction "GPIO2_4") (pintype "bidirectional"))
      (node (ref "RPI-CM1") (pin "46") (pinfunction "GPIO22_46") (pintype "passive"))
      (node (ref "RPIBOOT12") (pin "P$1") (pinfunction "1_P$1") (pintype "bidirectional"))
    )
    (net (code "113") (name "/SAM_QSPI_SCLK") (class "Default")
      (node (ref "C2040") (pin "52") (pinfunction "QSPI_SCLK_52") (pintype "bidirectional"))
      (node (ref "U16") (pin "6") (pinfunction "CLK_6") (pintype "input"))
    )
    (net (code "114") (name "/SAM_QSPI_SD0") (class "Default")
      (node (ref "C2040") (pin "53") (pinfunction "QSPI_SD0_53") (pintype "bidirectional"))
      (node (ref "U16") (pin "5") (pinfunction "IO0_5") (pintype "bidirectional"))
    )
    (net (code "115") (name "/SAM_QSPI_SD1") (class "Default")
      (node (ref "C2040") (pin "55") (pinfunction "QSPI_SD1_55") (pintype "bidirectional"))
      (node (ref "U16") (pin "2") (pinfunction "IO1_2") (pintype "bidirectional"))
    )
    (net (code "116") (name "/SAM_QSPI_SD2") (class "Default")
      (node (ref "C2040") (pin "54") (pinfunction "QSPI_SD2_54") (pintype "bidirectional"))
      (node (ref "U16") (pin "3") (pinfunction "IO2_3") (pintype "bidirectional"))
    )
    (net (code "117") (name "/SAM_QSPI_SD3") (class "Default")
      (node (ref "C2040") (pin "51") (pinfunction "QSPI_SD3_51") (pintype "bidirectional"))
      (node (ref "U16") (pin "7") (pinfunction "IO3_7") (pintype "bidirectional"))
    )
    (net (code "118") (name "/SAM_RUN") (class "Default")
      (node (ref "C2040") (pin "26") (pinfunction "RUN_26") (pintype "input"))
    )
    (net (code "119") (name "/SAM_SWCLK") (class "Default")
      (node (ref "C2040") (pin "24") (pinfunction "SWCLK_24") (pintype "input"))
    )
    (net (code "120") (name "/SAM_SWD") (class "Default")
      (node (ref "C2040") (pin "25") (pinfunction "SWD_25") (pintype "bidirectional"))
    )
    (net (code "121") (name "/SAM_USB_DM") (class "Default")
      (node (ref "C2040") (pin "46") (pinfunction "USB_DM_46") (pintype "bidirectional"))
      (node (ref "R32") (pin "2") (pinfunction "2_2") (pintype "passive"))
    )
    (net (code "122") (name "/SAM_USB_DP") (class "Default")
      (node (ref "C2040") (pin "47") (pinfunction "USB_DP_47") (pintype "bidirectional"))
      (node (ref "R31") (pin "2") (pinfunction "2_2") (pintype "passive"))
    )
    (net (code "123") (name "/SAM_USB_SWITCH") (class "Default")
      (node (ref "C2040") (pin "30") (pinfunction "GPIO19_30") (pintype "bidirectional"))
      (node (ref "R41") (pin "1") (pinfunction "1_1") (pintype "passive"))
      (node (ref "USB2.0MUX") (pin "8") (pinfunction "~{OE}_8") (pintype "input"))
    )
    (net (code "124") (name "/SAM_XIN") (class "Default")
      (node (ref "C2040") (pin "20") (pinfunction "XIN_20") (pintype "passive"))
      (node (ref "C82") (pin "1") (pinfunction "1_1") (pintype "passive"))
      (node (ref "Y1") (pin "1") (pinfunction "CRYSTAL_1_1") (pintype "bidirectional"))
    )
    (net (code "125") (name "/SAM_XOUT") (class "Default")
      (node (ref "C2040") (pin "21") (pinfunction "XOUT_21") (pintype "passive"))
      (node (ref "R35") (pin "1") (pinfunction "1_1") (pintype "passive"))
    )
    (net (code "126") (name "/SCL0") (class "Default")
      (node (ref "CAMERA") (pin "20") (pinfunction "20_20") (pintype "passive"))
      (node (ref "RPI-CM1") (pin "80") (pinfunction "SCL0_80") (pintype "passive"))
    )
    (net (code "127") (name "/SDA0") (class "Default")
      (node (ref "CAMERA") (pin "21") (pinfunction "21_21") (pintype "passive"))
      (node (ref "RPI-CM1") (pin "82") (pinfunction "SDA0_82") (pintype "passive"))
    )
    (net (code "128") (name "/SOC_EINK_BUSY") (class "Default")
      (node (ref "RPI-CM1") (pin "40") (pinfunction "GPIO9_40") (pintype "passive"))
      (node (ref "U7") (pin "17") (pinfunction "1Y1_17") (pintype "output"))
    )
    (net (code "129") (name "/SOC_EINK_CS") (class "Default")
      (node (ref "RPI-CM1") (pin "39") (pinfunction "GPIO8_39") (pintype "passive"))
      (node (ref "U7") (pin "7") (pinfunction "1A4_7") (pintype "input"))
    )
    (net (code "130") (name "/SOC_EINK_D{slash}C") (class "Default")
      (node (ref "RPI-CM1") (pin "30") (pinfunction "GPIO6_30") (pintype "passive"))
      (node (ref "U7") (pin "5") (pinfunction "1A3_5") (pintype "input"))
    )
    (net (code "131") (name "/SOC_EINK_RESET") (class "Default")
      (node (ref "RPI-CM1") (pin "28") (pinfunction "GPIO13_28") (pintype "passive"))
      (node (ref "U7") (pin "3") (pinfunction "1A2_3") (pintype "input"))
    )
    (net (code "132") (name "/SOC_SPI_CLK") (class "Default")
      (node (ref "RPI-CM1") (pin "38") (pinfunction "GPIO11_38") (pintype "passive"))
      (node (ref "U7") (pin "10") (pinfunction "2A1_10") (pintype "input"))
    )
    (net (code "133") (name "/SOC_SPI_MOSI") (class "Default")
      (node (ref "RPI-CM1") (pin "44") (pinfunction "GPIO10_44") (pintype "passive"))
      (node (ref "U7") (pin "12") (pinfunction "2A2_12") (pintype "input"))
    )
    (net (code "134") (name "/SPI_CLK") (class "Default")
      (node (ref "C2040") (pin "17") (pinfunction "GPIO14_17") (pintype "bidirectional"))
      (node (ref "EINK_524352471") (pin "12") (pinfunction "12_12") (pintype "passive"))
      (node (ref "RPIBOOT11") (pin "P$1") (pinfunction "1_P$1") (pintype "bidirectional"))
      (node (ref "U21") (pin "2") (pinfunction "I/O_2") (pintype "passive"))
      (node (ref "U7") (pin "8") (pinfunction "2Y1_8") (pintype "output"))
    )
    (net (code "135") (name "/SPI_MOSI") (class "Default")
      (node (ref "C2040") (pin "18") (pinfunction "GPIO15_18") (pintype "bidirectional"))
      (node (ref "EINK_524352471") (pin "11") (pinfunction "11_11") (pintype "passive"))
      (node (ref "GND42") (pin "P$1") (pinfunction "1_P$1") (pintype "bidirectional"))
      (node (ref "U22") (pin "2") (pinfunction "I/O_2") (pintype "passive"))
      (node (ref "U7") (pin "6") (pinfunction "2Y2_6") (pintype "output"))
    )
    (net (code "136") (name "/SYS_PI_ON") (class "Default")
      (node (ref "C2040") (pin "32") (pinfunction "GPIO21_32") (pintype "bidirectional"))
      (node (ref "Q3") (pin "1") (pinfunction "G_1") (pintype "passive"))
    )
    (net (code "137") (name "/TACH") (class "Default")
      (node (ref "J6") (pin "2") (pinfunction "2_2") (pintype "passive"))
      (node (ref "R30") (pin "1") (pinfunction "1_1") (pintype "passive"))
      (node (ref "U9") (pin "6") (pinfunction "TACH_6") (pintype "input"))
    )
    (net (code "138") (name "/TSCL") (class "Default")
      (node (ref "EINK_524352471") (pin "19") (pinfunction "19_19") (pintype "passive"))
      (node (ref "U23") (pin "2") (pinfunction "I/O_2") (pintype "passive"))
    )
    (net (code "139") (name "/TSDA") (class "Default")
      (node (ref "EINK_524352471") (pin "18") (pinfunction "18_18") (pintype "passive"))
      (node (ref "U24") (pin "2") (pinfunction "I/O_2") (pintype "passive"))
    )
    (net (code "140") (name "/U25_OUT+") (class "Default")
      (node (ref "H2") (pin "1") (pinfunction "1_1") (pintype "passive"))
      (node (ref "H2") (pin "2") (pinfunction "2_2") (pintype "passive"))
      (node (ref "U25") (pin "7") (pinfunction "OUT+_7") (pintype "output"))
    )
    (net (code "141") (name "/U25_OUT-") (class "Default")
      (node (ref "H2") (pin "3") (pinfunction "3_3") (pintype "passive"))
      (node (ref "H2") (pin "4") (pinfunction "4_4") (pintype "passive"))
      (node (ref "U25") (pin "9") (pinfunction "OUT-_9") (pintype "output"))
    )
    (net (code "142") (name "/UART_RXD0") (class "Default")
      (node (ref "J5") (pin "2") (pinfunction "2_2") (pintype "passive"))
      (node (ref "RPI-CM1") (pin "51") (pinfunction "GPIO15_51") (pintype "passive"))
    )
    (net (code "143") (name "/UART_TXD0") (class "Default")
      (node (ref "J5") (pin "1") (pinfunction "1_1") (pintype "passive"))
      (node (ref "RPI-CM1") (pin "55") (pinfunction "GPIO14_55") (pintype "passive"))
    )
    (net (code "144") (name "/USB_OTG_ID") (class "Default")
      (node (ref "RPI-CM1") (pin "101") (pinfunction "USB_OTG_ID_101") (pintype "passive"))
    )
    (net (code "145") (name "/VCOM") (class "Default")
      (node (ref "C15") (pin "1") (pinfunction "1_1") (pintype "passive"))
      (node (ref "EINK_524352471") (pin "1") (pinfunction "1_1") (pintype "passive"))
    )
    (net (code "146") (name "/VDAC_COMP") (class "Default")
      (node (ref "RPI-CM1") (pin "111") (pinfunction "VDAC_COMP_111") (pintype "passive"))
    )
    (net (code "147") (name "/VGH") (class "Default")
      (node (ref "C8") (pin "1") (pinfunction "1_1") (pintype "passive"))
      (node (ref "EINK_524352471") (pin "20") (pinfunction "20_20") (pintype "passive"))
    )
    (net (code "148") (name "/VGL") (class "Default")
      (node (ref "C5") (pin "1") (pinfunction "1_1") (pintype "passive"))
      (node (ref "EINK_524352471") (pin "21") (pinfunction "21_21") (pintype "passive"))
    )
    (net (code "149") (name "/VMID") (class "Default")
      (node (ref "C45") (pin "1") (pinfunction "1_1") (pintype "passive"))
      (node (ref "C47") (pin "1") (pinfunction "1_1") (pintype "passive"))
      (node (ref "IC3") (pin "27") (pinfunction "VMID_27") (pintype "input"))
    )
    (net (code "150") (name "/VPP") (class "Default")
      (node (ref "C11") (pin "1") (pinfunction "1_1") (pintype "passive"))
      (node (ref "EINK_524352471") (pin "6") (pinfunction "6_6") (pintype "passive"))
    )
    (net (code "151") (name "/VSH") (class "Default")
      (node (ref "C12") (pin "1") (pinfunction "1_1") (pintype "passive"))
      (node (ref "EINK_524352471") (pin "5") (pinfunction "5_5") (pintype "passive"))
    )
    (net (code "152") (name "/VSL") (class "Default")
      (node (ref "C13") (pin "1") (pinfunction "1_1") (pintype "passive"))
      (node (ref "EINK_524352471") (pin "3") (pinfunction "3_3") (pintype "passive"))
    )
    (net (code "153") (name "/~{CE}") (class "Default")
      (node (ref "R24") (pin "1") (pinfunction "1_1") (pintype "passive"))
      (node (ref "U4") (pin "4") (pinfunction "~{CE}_4") (pintype "bidirectional"))
    )
    (net (code "154") (name "3.3V") (class "Default")
      (node (ref "C28") (pin "1") (pinfunction "1_1") (pintype "passive"))
      (node (ref "C36") (pin "2") (pinfunction "2_2") (pintype "passive"))
      (node (ref "C49") (pin "1") (pinfunction "1_1") (pintype "passive"))
      (node (ref "CAMERA") (pin "22") (pinfunction "22_22") (pintype "passive"))
      (node (ref "D1") (pin "A") (pinfunction "A_A") (pintype "passive"))
      (node (ref "IC1") (pin "5") (pinfunction "VDD_5") (pintype "power_in"))
      (node (ref "IC1") (pin "6") (pinfunction "VDDIO_6") (pintype "power_in"))
      (node (ref "IC3") (pin "10") (pinfunction "DBVDD_10") (pintype "power_in"))
      (node (ref "IC3") (pin "8") (pinfunction "DCVDD_8") (pintype "power_in"))
      (node (ref "OSC2") (pin "1") (pinfunction "INH_1") (pintype "bidirectional"))
      (node (ref "OSC2") (pin "4") (pinfunction "VCC_4") (pintype "power_in"))
      (node (ref "R15") (pin "2") (pinfunction "2_2") (pintype "passive"))
      (node (ref "R18") (pin "2") (pinfunction "2_2") (pintype "passive"))
      (node (ref "R30") (pin "2") (pinfunction "2_2") (pintype "passive"))
      (node (ref "R33") (pin "2") (pinfunction "2_2") (pintype "passive"))
      (node (ref "RPI-CM1") (pin "84") (pinfunction "CM4_3.3V(OUTPUT)_84") (pintype "passive"))
      (node (ref "RPI-CM1") (pin "86") (pinfunction "CM4_3.3V(OUTPUT)_86") (pintype "passive"))
      (node (ref "RPIBOOT2") (pin "P$1") (pinfunction "1_P$1") (pintype "bidirectional"))
      (node (ref "SJ6") (pin "1") (pinfunction "1_1") (pintype "passive"))
      (node (ref "U2") (pin "5") (pinfunction "VCC_5") (pintype "power_in"))
      (node (ref "U6") (pin "5") (pinfunction "VDDIO_5") (pintype "power_in"))
      (node (ref "U6") (pin "8") (pinfunction "VDD_8") (pintype "power_in"))
      (node (ref "U9") (pin "3") (pinfunction "VDD_3") (pintype "power_in"))
    )
    (net (code "155") (name "3V3_EINK") (class "Default")
      (node (ref "C17") (pin "1") (pinfunction "1_1") (pintype "passive"))
      (node (ref "C9") (pin "1") (pinfunction "1_1") (pintype "passive"))
      (node (ref "EINK_524352471") (pin "10") (pinfunction "10_10") (pintype "passive"))
      (node (ref "EINK_524352471") (pin "9") (pinfunction "9_9") (pintype "passive"))
      (node (ref "L3") (pin "1") (pinfunction "1_1") (pintype "passive"))
      (node (ref "Q2") (pin "3") (pinfunction "D_3") (pintype "passive"))
    )
    (net (code "156") (name "5.0V") (class "Default")
      (node (ref "C2") (pin "1") (pinfunction "1_1") (pintype "passive"))
      (node (ref "C25") (pin "1") (pinfunction "1_1") (pintype "passive"))
      (node (ref "C42") (pin "1") (pinfunction "1_1") (pintype "passive"))
      (node (ref "C59") (pin "1") (pinfunction "1_1") (pintype "passive"))
      (node (ref "C6") (pin "1") (pinfunction "1_1") (pintype "passive"))
      (node (ref "C60") (pin "1") (pinfunction "1_1") (pintype "passive"))
      (node (ref "C61") (pin "1") (pinfunction "1_1") (pintype "passive"))
      (node (ref "C65") (pin "1") (pinfunction "1_1") (pintype "passive"))
      (node (ref "C66") (pin "1") (pinfunction "1_1") (pintype "passive"))
      (node (ref "IC3") (pin "21") (pinfunction "SPKVDD2_21") (pintype "power_in"))
      (node (ref "IC3") (pin "26") (pinfunction "SPKVDD1_26") (pintype "power_in"))
      (node (ref "J6") (pin "3") (pinfunction "3_3") (pintype "passive"))
      (node (ref "R3") (pin "2") (pinfunction "2_2") (pintype "passive"))
      (node (ref "R5") (pin "1") (pinfunction "1_1") (pintype "passive"))
      (node (ref "RPI-CM1") (pin "77") (pinfunction "+5V(INPUT)_77") (pintype "passive"))
      (node (ref "RPI-CM1") (pin "79") (pinfunction "+5V(INPUT)_79") (pintype "passive"))
      (node (ref "RPI-CM1") (pin "81") (pinfunction "+5V(INPUT)_81") (pintype "passive"))
      (node (ref "RPI-CM1") (pin "83") (pinfunction "+5V(INPUT)_83") (pintype "passive"))
      (node (ref "RPI-CM1") (pin "85") (pinfunction "+5V(INPUT)_85") (pintype "passive"))
      (node (ref "RPI-CM1") (pin "87") (pinfunction "+5V(INPUT)_87") (pintype "passive"))
      (node (ref "RPIBOOT1") (pin "P$1") (pinfunction "1_P$1") (pintype "bidirectional"))
      (node (ref "U1") (pin "1") (pinfunction "VOUT_1") (pintype "power_in"))
      (node (ref "U1") (pin "15") (pinfunction "VOUT_15") (pintype "power_in"))
      (node (ref "U1") (pin "16") (pinfunction "VOUT_16") (pintype "power_in"))
      (node (ref "U10") (pin "1") (pinfunction "IN_1") (pintype "power_in"))
      (node (ref "U10") (pin "3") (pinfunction "EN_3") (pintype "input"))
    )
    (net (code "157") (name "AGND") (class "Default")
      (node (ref "C67") (pin "2") (pinfunction "2_2") (pintype "passive"))
      (node (ref "C68") (pin "2") (pinfunction "2_2") (pintype "passive"))
      (node (ref "FB5") (pin "2") (pinfunction "2_2") (pintype "passive"))
      (node (ref "IC3") (pin "28") (pinfunction "AGND_28") (pintype "power_in"))
      (node (ref "IC3") (pin "33") (pinfunction "AGND_33") (pintype "power_in"))
    )
    (net (code "158") (name "AVDD") (class "Default")
      (node (ref "C50") (pin "1") (pinfunction "1_1") (pintype "passive"))
      (node (ref "C58") (pin "1") (pinfunction "1_1") (pintype "passive"))
      (node (ref "C67") (pin "1") (pinfunction "1_1") (pintype "passive"))
      (node (ref "C68") (pin "1") (pinfunction "1_1") (pintype "passive"))
      (node (ref "FB1") (pin "2") (pinfunction "2_2") (pintype "passive"))
      (node (ref "IC3") (pin "32") (pinfunction "AVDD_32") (pintype "power_in"))
      (node (ref "R27") (pin "2") (pinfunction "2_2") (pintype "passive"))
      (node (ref "U12") (pin "4") (pinfunction "VDD_4") (pintype "power_in"))
      (node (ref "U14") (pin "5") (pinfunction "P$V+_5") (pintype "bidirectional"))
    )
    (net (code "159") (name "BATTERY_IN") (class "Default")
      (node (ref "C19") (pin "1") (pinfunction "1_1") (pintype "passive"))
      (node (ref "J1") (pin "3") (pinfunction "3_3") (pintype "passive"))
      (node (ref "R12") (pin "2") (pinfunction "2_2") (pintype "passive"))
      (node (ref "U3") (pin "6") (pinfunction "BAT_6") (pintype "bidirectional"))
      (node (ref "U3") (pin "8") (pinfunction "SRP_8") (pintype "bidirectional"))
    )
    (net (code "160") (name "BOOST_EN") (class "Default")
      (node (ref "Q3") (pin "3") (pinfunction "D_3") (pintype "passive"))
      (node (ref "R13") (pin "1") (pinfunction "1_1") (pintype "passive"))
      (node (ref "R36") (pin "2") (pinfunction "2_2") (pintype "passive"))
    )
    (net (code "161") (name "EXT_VCC_PCIE") (class "Default")
      (node (ref "M.2KEYM(NGFF)") (pin "12") (pinfunction "P12_12") (pintype "passive"))
      (node (ref "M.2KEYM(NGFF)") (pin "14") (pinfunction "P14_14") (pintype "passive"))
      (node (ref "M.2KEYM(NGFF)") (pin "16") (pinfunction "P16_16") (pintype "passive"))
      (node (ref "M.2KEYM(NGFF)") (pin "18") (pinfunction "P18_18") (pintype "passive"))
      (node (ref "M.2KEYM(NGFF)") (pin "2") (pinfunction "P2_2") (pintype "passive"))
      (node (ref "M.2KEYM(NGFF)") (pin "4") (pinfunction "P4_4") (pintype "passive"))
      (node (ref "M.2KEYM(NGFF)") (pin "70") (pinfunction "P70_70") (pintype "passive"))
      (node (ref "M.2KEYM(NGFF)") (pin "72") (pinfunction "P72_72") (pintype "passive"))
      (node (ref "M.2KEYM(NGFF)") (pin "74") (pinfunction "P74_74") (pintype "passive"))
      (node (ref "RPIBOOT3") (pin "P$1") (pinfunction "1_P$1") (pintype "bidirectional"))
    )
    (net (code "162") (name "GND") (class "Default")
      (node (ref "C1") (pin "2") (pinfunction "2_2") (pintype "passive"))
      (node (ref "C10") (pin "2") (pinfunction "2_2") (pintype "passive"))
      (node (ref "C11") (pin "2") (pinfunction "2_2") (pintype "passive"))
      (node (ref "C12") (pin "2") (pinfunction "2_2") (pintype "passive"))
      (node (ref "C13") (pin "2") (pinfunction "2_2") (pintype "passive"))
      (node (ref "C14") (pin "2") (pinfunction "2_2") (pintype "passive"))
      (node (ref "C15") (pin "2") (pinfunction "2_2") (pintype "passive"))
      (node (ref "C16") (pin "2") (pinfunction "2_2") (pintype "passive"))
      (node (ref "C17") (pin "2") (pinfunction "2_2") (pintype "passive"))
      (node (ref "C19") (pin "2") (pinfunction "2_2") (pintype "passive"))
      (node (ref "C2") (pin "2") (pinfunction "2_2") (pintype "passive"))
      (node (ref "C20") (pin "2") (pinfunction "2_2") (pintype "passive"))
      (node (ref "C2040") (pin "19") (pinfunction "TESTEN_19") (pintype "input"))
      (node (ref "C2040") (pin "57") (pinfunction "GND_57") (pintype "passive"))
      (node (ref "C21") (pin "2") (pinfunction "2_2") (pintype "passive"))
      (node (ref "C22") (pin "2") (pinfunction "2_2") (pintype "passive"))
      (node (ref "C23") (pin "2") (pinfunction "2_2") (pintype "passive"))
      (node (ref "C24") (pin "1") (pinfunction "1_1") (pintype "passive"))
      (node (ref "C25") (pin "2") (pinfunction "2_2") (pintype "passive"))
      (node (ref "C26") (pin "2") (pinfunction "2_2") (pintype "passive"))
      (node (ref "C28") (pin "2") (pinfunction "2_2") (pintype "passive"))
      (node (ref "C3") (pin "2") (pinfunction "2_2") (pintype "passive"))
      (node (ref "C30") (pin "2") (pinfunction "2_2") (pintype "passive"))
      (node (ref "C31") (pin "2") (pinfunction "2_2") (pintype "passive"))
      (node (ref "C32") (pin "2") (pinfunction "2_2") (pintype "passive"))
      (node (ref "C33") (pin "2") (pinfunction "2_2") (pintype "passive"))
      (node (ref "C34") (pin "1") (pinfunction "1_1") (pintype "passive"))
      (node (ref "C35") (pin "2") (pinfunction "2_2") (pintype "passive"))
      (node (ref "C36") (pin "1") (pinfunction "1_1") (pintype "passive"))
      (node (ref "C4") (pin "2") (pinfunction "2_2") (pintype "passive"))
      (node (ref "C40") (pin "2") (pinfunction "2_2") (pintype "passive"))
      (node (ref "C42") (pin "2") (pinfunction "2_2") (pintype "passive"))
      (node (ref "C43") (pin "2") (pinfunction "2_2") (pintype "passive"))
      (node (ref "C44") (pin "2") (pinfunction "2_2") (pintype "passive"))
      (node (ref "C45") (pin "2") (pinfunction "2_2") (pintype "passive"))
      (node (ref "C46") (pin "2") (pinfunction "2_2") (pintype "passive"))
      (node (ref "C47") (pin "2") (pinfunction "2_2") (pintype "passive"))
      (node (ref "C48") (pin "2") (pinfunction "2_2") (pintype "passive"))
      (node (ref "C49") (pin "2") (pinfunction "2_2") (pintype "passive"))
      (node (ref "C5") (pin "2") (pinfunction "2_2") (pintype "passive"))
      (node (ref "C50") (pin "2") (pinfunction "2_2") (pintype "passive"))
      (node (ref "C53") (pin "2") (pinfunction "2_2") (pintype "passive"))
      (node (ref "C58") (pin "2") (pinfunction "2_2") (pintype "passive"))
      (node (ref "C59") (pin "2") (pinfunction "2_2") (pintype "passive"))
      (node (ref "C6") (pin "2") (pinfunction "2_2") (pintype "passive"))
      (node (ref "C60") (pin "2") (pinfunction "2_2") (pintype "passive"))
      (node (ref "C61") (pin "2") (pinfunction "2_2") (pintype "passive"))
      (node (ref "C62") (pin "2") (pinfunction "2_2") (pintype "passive"))
      (node (ref "C63") (pin "2") (pinfunction "2_2") (pintype "passive"))
      (node (ref "C64") (pin "2") (pinfunction "2_2") (pintype "passive"))
      (node (ref "C65") (pin "2") (pinfunction "2_2") (pintype "passive"))
      (node (ref "C66") (pin "2") (pinfunction "2_2") (pintype "passive"))
      (node (ref "C69") (pin "2") (pinfunction "2_2") (pintype "passive"))
      (node (ref "C7") (pin "2") (pinfunction "2_2") (pintype "passive"))
      (node (ref "C71") (pin "2") (pinfunction "2_2") (pintype "passive"))
      (node (ref "C72") (pin "2") (pinfunction "2_2") (pintype "passive"))
      (node (ref "C73") (pin "2") (pinfunction "2_2") (pintype "passive"))
      (node (ref "C74") (pin "2") (pinfunction "2_2") (pintype "passive"))
      (node (ref "C75") (pin "2") (pinfunction "2_2") (pintype "passive"))
      (node (ref "C76") (pin "2") (pinfunction "2_2") (pintype "passive"))
      (node (ref "C77") (pin "2") (pinfunction "2_2") (pintype "passive"))
      (node (ref "C79") (pin "2") (pinfunction "2_2") (pintype "passive"))
      (node (ref "C8") (pin "2") (pinfunction "2_2") (pintype "passive"))
      (node (ref "C80") (pin "2") (pinfunction "2_2") (pintype "passive"))
      (node (ref "C82") (pin "2") (pinfunction "2_2") (pintype "passive"))
      (node (ref "C83") (pin "1") (pinfunction "1_1") (pintype "passive"))
      (node (ref "C9") (pin "2") (pinfunction "2_2") (pintype "passive"))
      (node (ref "CAMERA") (pin "1") (pinfunction "1_1") (pintype "passive"))
      (node (ref "CAMERA") (pin "10") (pinfunction "10_10") (pintype "passive"))
      (node (ref "CAMERA") (pin "13") (pinfunction "13_13") (pintype "passive"))
      (node (ref "CAMERA") (pin "16") (pinfunction "16_16") (pintype "passive"))
      (node (ref "CAMERA") (pin "19") (pinfunction "19_19") (pintype "passive"))
      (node (ref "CAMERA") (pin "4") (pinfunction "4_4") (pintype "passive"))
      (node (ref "CAMERA") (pin "7") (pinfunction "7_7") (pintype "passive"))
      (node (ref "CAMERA") (pin "P1") (pinfunction "P1_P1") (pintype "passive"))
      (node (ref "CAMERA") (pin "P2") (pinfunction "P2_P2") (pintype "passive"))
      (node (ref "D2") (pin "1") (pinfunction "K_1") (pintype "bidirectional"))
      (node (ref "EINK_524352471") (pin "17") (pinfunction "17_17") (pintype "passive"))
      (node (ref "EINK_524352471") (pin "8") (pinfunction "8_8") (pintype "passive"))
      (node (ref "EINK_524352471") (pin "P1") (pinfunction "P1_P1") (pintype "passive"))
      (node (ref "EINK_524352471") (pin "P2") (pinfunction "P2_P2") (pintype "passive"))
      (node (ref "FB5") (pin "1") (pinfunction "1_1") (pintype "passive"))
      (node (ref "GND") (pin "P$1") (pinfunction "1_P$1") (pintype "bidirectional"))
      (node (ref "GND13") (pin "P$1") (pinfunction "1_P$1") (pintype "bidirectional"))
      (node (ref "GND22") (pin "P$1") (pinfunction "1_P$1") (pintype "bidirectional"))
      (node (ref "GND26") (pin "P$1") (pinfunction "1_P$1") (pintype "bidirectional"))
      (node (ref "GND27") (pin "P$1") (pinfunction "1_P$1") (pintype "bidirectional"))
      (node (ref "GND34") (pin "P$1") (pinfunction "1_P$1") (pintype "bidirectional"))
      (node (ref "IC1") (pin "12") (pinfunction "GND_12") (pintype "power_in"))
      (node (ref "IC1") (pin "2") (pinfunction "GND_2") (pintype "power_in"))
      (node (ref "IC1") (pin "3") (pinfunction "GND_3") (pintype "power_in"))
      (node (ref "IC1") (pin "9") (pinfunction "SDO_9") (pintype "bidirectional"))
      (node (ref "IC3") (pin "20") (pinfunction "SPKGND2_20") (pintype "power_in"))
      (node (ref "IC3") (pin "24") (pinfunction "SPKGND1_24") (pintype "power_in"))
      (node (ref "IC3") (pin "9") (pinfunction "DGND_9") (pintype "power_in"))
      (node (ref "J1") (pin "1") (pinfunction "1_1") (pintype "passive"))
      (node (ref "J2") (pin "GND") (pinfunction "GND_GND") (pintype "bidirectional"))
      (node (ref "J2") (pin "GND2") (pinfunction "GND_GND2") (pintype "bidirectional"))
      (node (ref "J2") (pin "SHLD1") (pinfunction "SHLD_SHLD1") (pintype "bidirectional"))
      (node (ref "J2") (pin "SHLD2") (pinfunction "SHLD_SHLD2") (pintype "bidirectional"))
      (node (ref "J2") (pin "SHLD3") (pinfunction "SHLD_SHLD3") (pintype "bidirectional"))
      (node (ref "J2") (pin "SHLD4") (pinfunction "SHLD_SHLD4") (pintype "bidirectional"))
      (node (ref "J2") (pin "SHLD5") (pinfunction "SHLD_SHLD5") (pintype "bidirectional"))
      (node (ref "J2") (pin "SHLD6") (pinfunction "SHLD_SHLD6") (pintype "bidirectional"))
      (node (ref "J2") (pin "SHLD7") (pinfunction "SHLD_SHLD7") (pintype "bidirectional"))
      (node (ref "J2") (pin "SHLD8") (pinfunction "SHLD_SHLD8") (pintype "bidirectional"))
      (node (ref "J4") (pin "4") (pinfunction "4_4") (pintype "passive"))
      (node (ref "J5") (pin "3") (pinfunction "3_3") (pintype "passive"))
      (node (ref "J5") (pin "4") (pinfunction "4_4") (pintype "passive"))
      (node (ref "J6") (pin "4") (pinfunction "4_4") (pintype "passive"))
      (node (ref "LED2") (pin "C") (pinfunction "C_C") (pintype "passive"))
      (node (ref "LED3") (pin "C") (pinfunction "C_C") (pintype "passive"))
      (node (ref "LOW_BATT") (pin "C") (pinfunction "C_C") (pintype "passive"))
      (node (ref "M.2KEYM(NGFF)") (pin "1") (pinfunction "P1_1") (pintype "passive"))
      (node (ref "M.2KEYM(NGFF)") (pin "15") (pinfunction "P15_15") (pintype "passive"))
      (node (ref "M.2KEYM(NGFF)") (pin "21") (pinfunction "P21_21") (pintype "passive"))
      (node (ref "M.2KEYM(NGFF)") (pin "27") (pinfunction "P27_27") (pintype "passive"))
      (node (ref "M.2KEYM(NGFF)") (pin "3") (pinfunction "P3_3") (pintype "passive"))
      (node (ref "M.2KEYM(NGFF)") (pin "33") (pinfunction "P33_33") (pintype "passive"))
      (node (ref "M.2KEYM(NGFF)") (pin "39") (pinfunction "P39_39") (pintype "passive"))
      (node (ref "M.2KEYM(NGFF)") (pin "45") (pinfunction "P45_45") (pintype "passive"))
      (node (ref "M.2KEYM(NGFF)") (pin "51") (pinfunction "P51_51") (pintype "passive"))
      (node (ref "M.2KEYM(NGFF)") (pin "57") (pinfunction "P57_57") (pintype "passive"))
      (node (ref "M.2KEYM(NGFF)") (pin "71") (pinfunction "P71_71") (pintype "passive"))
      (node (ref "M.2KEYM(NGFF)") (pin "73") (pinfunction "P73_73") (pintype "passive"))
      (node (ref "M.2KEYM(NGFF)") (pin "75") (pinfunction "P75_75") (pintype "passive"))
      (node (ref "M.2KEYM(NGFF)") (pin "9") (pinfunction "P9_9") (pintype "passive"))
      (node (ref "M.2KEYM(NGFF)") (pin "SH1") (pinfunction "SHIELD_SH1") (pintype "passive"))
      (node (ref "M.2KEYM(NGFF)") (pin "SH2") (pinfunction "SHIELD_SH2") (pintype "passive"))
      (node (ref "OSC2") (pin "2") (pinfunction "GND_2") (pintype "power_in"))
      (node (ref "Q3") (pin "2") (pinfunction "S_2") (pintype "passive"))
      (node (ref "Q4") (pin "2") (pinfunction "S_2") (pintype "passive"))
      (node (ref "R11") (pin "1") (pinfunction "1_1") (pintype "passive"))
      (node (ref "R14") (pin "2") (pinfunction "2_2") (pintype "passive"))
      (node (ref "R16") (pin "1") (pinfunction "1_1") (pintype "passive"))
      (node (ref "R17") (pin "1") (pinfunction "1_1") (pintype "passive"))
      (node (ref "R19") (pin "1") (pinfunction "1_1") (pintype "passive"))
      (node (ref "R2") (pin "1") (pinfunction "1_1") (pintype "passive"))
      (node (ref "R21") (pin "1") (pinfunction "1_1") (pintype "passive"))
      (node (ref "R23") (pin "2") (pinfunction "2_2") (pintype "passive"))
      (node (ref "R24") (pin "2") (pinfunction "2_2") (pintype "passive"))
      (node (ref "R28") (pin "1") (pinfunction "1_1") (pintype "passive"))
      (node (ref "R37") (pin "1") (pinfunction "1_1") (pintype "passive"))
      (node (ref "R4") (pin "1") (pinfunction "1_1") (pintype "passive"))
      (node (ref "R41") (pin "2") (pinfunction "2_2") (pintype "passive"))
      (node (ref "R6") (pin "2") (pinfunction "2_2") (pintype "passive"))
      (node (ref "R7") (pin "2") (pinfunction "2_2") (pintype "passive"))
      (node (ref "R9") (pin "1") (pinfunction "1_1") (pintype "passive"))
      (node (ref "RPI-CM1") (pin "1") (pinfunction "GND_1") (pintype "passive"))
      (node (ref "RPI-CM1") (pin "107") (pinfunction "GND_107") (pintype "passive"))
      (node (ref "RPI-CM1") (pin "108") (pinfunction "GND_108") (pintype "passive"))
      (node (ref "RPI-CM1") (pin "113") (pinfunction "GND_113") (pintype "passive"))
      (node (ref "RPI-CM1") (pin "114") (pinfunction "GND_114") (pintype "passive"))
      (node (ref "RPI-CM1") (pin "119") (pinfunction "GND_119") (pintype "passive"))
      (node (ref "RPI-CM1") (pin "120") (pinfunction "GND_120") (pintype "passive"))
      (node (ref "RPI-CM1") (pin "125") (pinfunction "GND_125") (pintype "passive"))
      (node (ref "RPI-CM1") (pin "126") (pinfunction "GND_126") (pintype "passive"))
      (node (ref "RPI-CM1") (pin "13") (pinfunction "GND_13") (pintype "passive"))
      (node (ref "RPI-CM1") (pin "131") (pinfunction "GND_131") (pintype "passive"))
      (node (ref "RPI-CM1") (pin "132") (pinfunction "GND_132") (pintype "passive"))
      (node (ref "RPI-CM1") (pin "137") (pinfunction "GND_137") (pintype "passive"))
      (node (ref "RPI-CM1") (pin "138") (pinfunction "GND_138") (pintype "passive"))
      (node (ref "RPI-CM1") (pin "14") (pinfunction "GND_14") (pintype "passive"))
      (node (ref "RPI-CM1") (pin "144") (pinfunction "GND_144") (pintype "passive"))
      (node (ref "RPI-CM1") (pin "150") (pinfunction "GND_150") (pintype "passive"))
      (node (ref "RPI-CM1") (pin "155") (pinfunction "GND_155") (pintype "passive"))
      (node (ref "RPI-CM1") (pin "156") (pinfunction "GND_156") (pintype "passive"))
      (node (ref "RPI-CM1") (pin "161") (pinfunction "GND_161") (pintype "passive"))
      (node (ref "RPI-CM1") (pin "162") (pinfunction "GND_162") (pintype "passive"))
      (node (ref "RPI-CM1") (pin "167") (pinfunction "GND_167") (pintype "passive"))
      (node (ref "RPI-CM1") (pin "168") (pinfunction "GND_168") (pintype "passive"))
      (node (ref "RPI-CM1") (pin "173") (pinfunction "GND_173") (pintype "passive"))
      (node (ref "RPI-CM1") (pin "174") (pinfunction "GND_174") (pintype "passive"))
      (node (ref "RPI-CM1") (pin "179") (pinfunction "GND_179") (pintype "passive"))
      (node (ref "RPI-CM1") (pin "180") (pinfunction "GND_180") (pintype "passive"))
      (node (ref "RPI-CM1") (pin "185") (pinfunction "GND_185") (pintype "passive"))
      (node (ref "RPI-CM1") (pin "186") (pinfunction "GND_186") (pintype "passive"))
      (node (ref "RPI-CM1") (pin "191") (pinfunction "GND_191") (pintype "passive"))
      (node (ref "RPI-CM1") (pin "192") (pinfunction "GND_192") (pintype "passive"))
      (node (ref "RPI-CM1") (pin "197") (pinfunction "GND_197") (pintype "passive"))
      (node (ref "RPI-CM1") (pin "198") (pinfunction "GND_198") (pintype "passive"))
      (node (ref "RPI-CM1") (pin "2") (pinfunction "GND_2") (pintype "passive"))
      (node (ref "RPI-CM1") (pin "22") (pinfunction "GND_22") (pintype "passive"))
      (node (ref "RPI-CM1") (pin "23") (pinfunction "GND_23") (pintype "passive"))
      (node (ref "RPI-CM1") (pin "32") (pinfunction "GND_32") (pintype "passive"))
      (node (ref "RPI-CM1") (pin "33") (pinfunction "GND_33") (pintype "passive"))
      (node (ref "RPI-CM1") (pin "42") (pinfunction "GND_42") (pintype "passive"))
      (node (ref "RPI-CM1") (pin "43") (pinfunction "GND_43") (pintype "passive"))
      (node (ref "RPI-CM1") (pin "52") (pinfunction "GND_52") (pintype "passive"))
      (node (ref "RPI-CM1") (pin "53") (pinfunction "GND_53") (pintype "passive"))
      (node (ref "RPI-CM1") (pin "59") (pinfunction "GND_59") (pintype "passive"))
      (node (ref "RPI-CM1") (pin "60") (pinfunction "GND_60") (pintype "passive"))
      (node (ref "RPI-CM1") (pin "65") (pinfunction "GND_65") (pintype "passive"))
      (node (ref "RPI-CM1") (pin "66") (pinfunction "GND_66") (pintype "passive"))
      (node (ref "RPI-CM1") (pin "7") (pinfunction "GND_7") (pintype "passive"))
      (node (ref "RPI-CM1") (pin "71") (pinfunction "GND_71") (pintype "passive"))
      (node (ref "RPI-CM1") (pin "74") (pinfunction "GND_74") (pintype "passive"))
      (node (ref "RPI-CM1") (pin "8") (pinfunction "GND_8") (pintype "passive"))
      (node (ref "RPI-CM1") (pin "98") (pinfunction "GND_98") (pintype "passive"))
      (node (ref "U1") (pin "10") (pinfunction "SYNC_10") (pintype "input"))
      (node (ref "U1") (pin "13") (pinfunction "GND_13") (pintype "power_in"))
      (node (ref "U1") (pin "5") (pinfunction "PGND_5") (pintype "power_in"))
      (node (ref "U1") (pin "6") (pinfunction "PGND_6") (pintype "power_in"))
      (node (ref "U1") (pin "7") (pinfunction "PGND_7") (pintype "power_in"))
      (node (ref "U1") (pin "P$18") (pinfunction "PGND_P$18") (pintype "power_in"))
      (node (ref "U1") (pin "P$19") (pinfunction "PGND_P$19") (pintype "power_in"))
      (node (ref "U1") (pin "P$20") (pinfunction "PGND_P$20") (pintype "power_in"))
      (node (ref "U1") (pin "P$21") (pinfunction "PGND_P$21") (pintype "power_in"))
      (node (ref "U1") (pin "P$22") (pinfunction "PGND_P$22") (pintype "power_in"))
      (node (ref "U1") (pin "THERMAL") (pinfunction "PGND_THERMAL") (pintype "power_in"))
      (node (ref "U10") (pin "2") (pinfunction "GND_2") (pintype "power_in"))
      (node (ref "U11") (pin "2") (pinfunction "GND_2") (pintype "power_in"))
      (node (ref "U12") (pin "2") (pinfunction "GND_2") (pintype "power_in"))
      (node (ref "U12") (pin "3") (pinfunction "GND_3") (pintype "power_in"))
      (node (ref "U12") (pin "5") (pinfunction "GND_5") (pintype "power_in"))
      (node (ref "U12") (pin "6") (pinfunction "GND_6") (pintype "power_in"))
      (node (ref "U13") (pin "8") (pinfunction "GND_8") (pintype "power_in"))
      (node (ref "U14") (pin "2") (pinfunction "P$V-_2") (pintype "bidirectional"))
      (node (ref "U15") (pin "2") (pinfunction "GND_2") (pintype "power_in"))
      (node (ref "U16") (pin "4") (pinfunction "GND_4") (pintype "power_in"))
      (node (ref "U17") (pin "1") (pinfunction "I/O_2_1") (pintype "passive"))
      (node (ref "U18") (pin "1") (pinfunction "I/O_2_1") (pintype "passive"))
      (node (ref "U19") (pin "1") (pinfunction "I/O_2_1") (pintype "passive"))
      (node (ref "U2") (pin "3") (pinfunction "GND_3") (pintype "passive"))
      (node (ref "U20") (pin "1") (pinfunction "I/O_2_1") (pintype "passive"))
      (node (ref "U21") (pin "1") (pinfunction "I/O_2_1") (pintype "passive"))
      (node (ref "U22") (pin "1") (pinfunction "I/O_2_1") (pintype "passive"))
      (node (ref "U23") (pin "1") (pinfunction "I/O_2_1") (pintype "passive"))
      (node (ref "U24") (pin "1") (pinfunction "I/O_2_1") (pintype "passive"))
      (node (ref "U25") (pin "4") (pinfunction "IN/TRIG_4") (pintype "input"))
      (node (ref "U25") (pin "8") (pinfunction "GND_8") (pintype "power_in"))
      (node (ref "U3") (pin "3") (pinfunction "VSS_3") (pintype "bidirectional"))
      (node (ref "U3") (pin "EP") (pinfunction "PWPD_EP") (pintype "bidirectional"))
      (node (ref "U3") (pin "EP1") (pinfunction "PWPD_EP1") (pintype "bidirectional"))
      (node (ref "U3") (pin "EP2") (pinfunction "PWPD_EP2") (pintype "bidirectional"))
      (node (ref "U3") (pin "EP3") (pinfunction "PWPD_EP3") (pintype "bidirectional"))
      (node (ref "U3") (pin "EP4") (pinfunction "PWPD_EP4") (pintype "bidirectional"))
      (node (ref "U4") (pin "14") (pinfunction "TMR_14") (pintype "bidirectional"))
      (node (ref "U4") (pin "15") (pinfunction "SYSOFF_15") (pintype "bidirectional"))
      (node (ref "U4") (pin "6") (pinfunction "EN1_6") (pintype "bidirectional"))
      (node (ref "U4") (pin "8") (pinfunction "VSS_8") (pintype "bidirectional"))
      (node (ref "U4") (pin "EP") (pinfunction "EP_EP") (pintype "bidirectional"))
      (node (ref "U5") (pin "3") (pinfunction "GND_3") (pintype "passive"))
      (node (ref "U6") (pin "1") (pinfunction "SDO_1") (pintype "bidirectional"))
      (node (ref "U6") (pin "6") (pinfunction "GND_6") (pintype "power_in"))
      (node (ref "U6") (pin "7") (pinfunction "GND_7") (pintype "power_in"))
      (node (ref "U7") (pin "21") (pinfunction "PAD_21") (pintype "power_in"))
      (node (ref "U7") (pin "9") (pinfunction "GND_9") (pintype "power_in"))
      (node (ref "U9") (pin "4") (pinfunction "GND_4") (pintype "power_in"))
      (node (ref "USB2.0MUX") (pin "10") (pinfunction "S_10") (pintype "input"))
      (node (ref "USB2.0MUX") (pin "4") (pinfunction "GND_4") (pintype "passive"))
      (node (ref "Y1") (pin "2") (pinfunction "GND_1_2") (pintype "bidirectional"))
      (node (ref "Y1") (pin "4") (pinfunction "GND_2_4") (pintype "bidirectional"))
    )
    (net (code "163") (name "GPOUT") (class "Default")
      (node (ref "R33") (pin "1") (pinfunction "1_1") (pintype "passive"))
      (node (ref "U3") (pin "12") (pinfunction "GPOUT_12") (pintype "bidirectional"))
    )
    (net (code "164") (name "HAP_3V3") (class "Default")
      (node (ref "C33") (pin "1") (pinfunction "1_1") (pintype "passive"))
      (node (ref "C35") (pin "1") (pinfunction "1_1") (pintype "passive"))
      (node (ref "U15") (pin "5") (pinfunction "OUT_5") (pintype "power_in"))
      (node (ref "U25") (pin "10") (pinfunction "VDD_10") (pintype "power_in"))
      (node (ref "U25") (pin "5") (pinfunction "EN_5") (pintype "input"))
      (node (ref "U25") (pin "6") (pinfunction "VDD/NC_6") (pintype "power_in"))
    )
    (net (code "165") (name "Net-(C29-Pad2)") (class "Default")
      (node (ref "C29") (pin "2") (pinfunction "2_2") (pintype "passive"))
      (node (ref "R38") (pin "2") (pinfunction "2_2") (pintype "passive"))
    )
    (net (code "166") (name "Net-(D1-PadC)") (class "Default")
      (node (ref "D1") (pin "C") (pinfunction "C_C") (pintype "passive"))
      (node (ref "R10") (pin "1") (pinfunction "1_1") (pintype "passive"))
    )
    (net (code "167") (name "Net-(D2-A)") (class "Default")
      (node (ref "C18") (pin "1") (pinfunction "1_1") (pintype "passive"))
      (node (ref "D2") (pin "2") (pinfunction "A_2") (pintype "bidirectional"))
      (node (ref "D3") (pin "1") (pinfunction "K_1") (pintype "bidirectional"))
    )
    (net (code "168") (name "Net-(D4-A)") (class "Default")
      (node (ref "C18") (pin "2") (pinfunction "2_2") (pintype "passive"))
      (node (ref "D4") (pin "2") (pinfunction "A_2") (pintype "bidirectional"))
      (node (ref "L3") (pin "2") (pinfunction "2_2") (pintype "passive"))
      (node (ref "Q1") (pin "3") (pinfunction "D_3") (pintype "bidirectional"))
    )
    (net (code "169") (name "Net-(D5-PadC)") (class "Default")
      (node (ref "D5") (pin "C") (pinfunction "C_C") (pintype "passive"))
      (node (ref "R22") (pin "1") (pinfunction "1_1") (pintype "passive"))
    )
    (net (code "170") (name "Net-(D6-PadC)") (class "Default")
      (node (ref "D6") (pin "C") (pinfunction "C_C") (pintype "passive"))
      (node (ref "R23") (pin "1") (pinfunction "1_1") (pintype "passive"))
    )
    (net (code "171") (name "Net-(D7-PadC)") (class "Default")
      (node (ref "D7") (pin "C") (pinfunction "C_C") (pintype "passive"))
      (node (ref "R14") (pin "1") (pinfunction "1_1") (pintype "passive"))
    )
    (net (code "172") (name "Net-(IC1-C1)") (class "Default")
      (node (ref "C31") (pin "1") (pinfunction "1_1") (pintype "passive"))
      (node (ref "IC1") (pin "4") (pinfunction "C1_4") (pintype "input"))
    )
    (net (code "173") (name "Net-(IC3-SPK_LN)") (class "Default")
      (node (ref "FB3") (pin "1") (pinfunction "1_1") (pintype "passive"))
      (node (ref "IC3") (pin "23") (pinfunction "SPK_LN_23") (pintype "output"))
    )
    (net (code "174") (name "Net-(IC3-SPK_LP)") (class "Default")
      (node (ref "FB2") (pin "1") (pinfunction "1_1") (pintype "passive"))
      (node (ref "IC3") (pin "25") (pinfunction "SPK_LP_25") (pintype "output"))
    )
    (net (code "175") (name "Net-(J2-CC1)") (class "Default")
      (node (ref "J2") (pin "A5") (pinfunction "CC1_A5") (pintype "bidirectional"))
      (node (ref "R19") (pin "2") (pinfunction "2_2") (pintype "passive"))
    )
    (net (code "176") (name "Net-(J2-CC2)") (class "Default")
      (node (ref "J2") (pin "B5") (pinfunction "CC2_B5") (pintype "bidirectional"))
      (node (ref "R21") (pin "2") (pinfunction "2_2") (pintype "passive"))
    )
    (net (code "177") (name "Net-(L1-2)") (class "Default")
      (node (ref "L1") (pin "P$2") (pinfunction "2_P$2") (pintype "passive"))
      (node (ref "U1") (pin "3") (pinfunction "SW_3") (pintype "input"))
      (node (ref "U1") (pin "4") (pinfunction "SW_4") (pintype "input"))
    )
    (net (code "178") (name "Net-(LED2-PadA)") (class "Default")
      (node (ref "LED2") (pin "A") (pinfunction "A_A") (pintype "passive"))
      (node (ref "R5") (pin "2") (pinfunction "2_2") (pintype "passive"))
    )
    (net (code "179") (name "Net-(LED3-PadA)") (class "Default")
      (node (ref "LED3") (pin "A") (pinfunction "A_A") (pintype "passive"))
      (node (ref "R8") (pin "1") (pinfunction "1_1") (pintype "passive"))
    )
    (net (code "180") (name "Net-(LOW_BATT-PadA)") (class "Default")
      (node (ref "LOW_BATT") (pin "A") (pinfunction "A_A") (pintype "passive"))
      (node (ref "R20") (pin "1") (pinfunction "1_1") (pintype "passive"))
    )
    (net (code "181") (name "Net-(Q2-G)") (class "Default")
      (node (ref "Q2") (pin "1") (pinfunction "G_1") (pintype "passive"))
      (node (ref "R43") (pin "2") (pinfunction "2_2") (pintype "passive"))
      (node (ref "R44") (pin "1") (pinfunction "1_1") (pintype "passive"))
    )
    (net (code "182") (name "Net-(Q4-D)") (class "Default")
      (node (ref "Q4") (pin "3") (pinfunction "D_3") (pintype "passive"))
      (node (ref "R34") (pin "2") (pinfunction "2_2") (pintype "passive"))
      (node (ref "USB_BOOT_N") (pin "P$1") (pinfunction "1_P$1") (pintype "bidirectional"))
    )
    (net (code "183") (name "Net-(R20-Pad2)") (class "Default")
      (node (ref "R20") (pin "2") (pinfunction "2_2") (pintype "passive"))
      (node (ref "T1") (pin "C") (pinfunction "C_C") (pintype "passive"))
    )
    (net (code "184") (name "Net-(RPI-CM1A-GPIO_VREF)") (class "Default")
      (node (ref "RPI-CM1") (pin "78") (pinfunction "GPIO_VREF_78") (pintype "passive"))
      (node (ref "SJ6") (pin "2") (pinfunction "2_2") (pintype "passive"))
    )
    (net (code "185") (name "Net-(RPI-CM1A-PI_LED_~{PWR})") (class "Default")
      (node (ref "RPI-CM1") (pin "95") (pinfunction "PI_LED_~{PWR}_95") (pintype "passive"))
      (node (ref "U2") (pin "2") (pinfunction "IN_A_2") (pintype "input"))
    )
    (net (code "186") (name "Net-(RPI-CM1A-PI_~{LED_ACTIVITY})") (class "Default")
      (node (ref "R10") (pin "2") (pinfunction "2_2") (pintype "passive"))
      (node (ref "RPI-CM1") (pin "21") (pinfunction "PI_~{LED_ACTIVITY}_21") (pintype "passive"))
    )
    (net (code "187") (name "Net-(U1-EN)") (class "Default")
      (node (ref "R13") (pin "2") (pinfunction "2_2") (pintype "passive"))
      (node (ref "U1") (pin "11") (pinfunction "EN_11") (pintype "input"))
    )
    (net (code "188") (name "Net-(U1-FB)") (class "Default")
      (node (ref "R3") (pin "1") (pinfunction "1_1") (pintype "passive"))
      (node (ref "R4") (pin "2") (pinfunction "2_2") (pintype "passive"))
      (node (ref "U1") (pin "14") (pinfunction "FB_14") (pintype "input"))
    )
    (net (code "189") (name "Net-(U1-LBI)") (class "Default")
      (node (ref "R1") (pin "1") (pinfunction "1_1") (pintype "passive"))
      (node (ref "R2") (pin "2") (pinfunction "2_2") (pintype "passive"))
      (node (ref "U1") (pin "9") (pinfunction "LBI_9") (pintype "input"))
    )
    (net (code "190") (name "Net-(U2-OUT_~{Y})") (class "Default")
      (node (ref "R8") (pin "2") (pinfunction "2_2") (pintype "passive"))
      (node (ref "U2") (pin "4") (pinfunction "OUT_~{Y}_4") (pintype "output"))
    )
    (net (code "191") (name "Net-(U4-ILIM)") (class "Default")
      (node (ref "R7") (pin "1") (pinfunction "1_1") (pintype "passive"))
      (node (ref "U4") (pin "12") (pinfunction "ILIM_12") (pintype "bidirectional"))
    )
    (net (code "192") (name "Net-(U4-ISET)") (class "Default")
      (node (ref "R6") (pin "1") (pinfunction "1_1") (pintype "passive"))
      (node (ref "U4") (pin "16") (pinfunction "ISET_16") (pintype "bidirectional"))
    )
    (net (code "193") (name "Net-(U4-~{CHG})") (class "Default")
      (node (ref "R22") (pin "2") (pinfunction "2_2") (pintype "passive"))
      (node (ref "U4") (pin "9") (pinfunction "~{CHG}_9") (pintype "bidirectional"))
    )
    (net (code "194") (name "Net-(U5-OUT_~{Y})") (class "Default")
      (node (ref "R44") (pin "2") (pinfunction "2_2") (pintype "passive"))
      (node (ref "U5") (pin "4") (pinfunction "OUT_~{Y}_4") (pintype "output"))
    )
    (net (code "195") (name "Net-(U10-OUT)") (class "Default")
      (node (ref "C62") (pin "1") (pinfunction "1_1") (pintype "passive"))
      (node (ref "C69") (pin "1") (pinfunction "1_1") (pintype "passive"))
      (node (ref "FB1") (pin "1") (pinfunction "1_1") (pintype "passive"))
      (node (ref "U10") (pin "5") (pinfunction "OUT_5") (pintype "power_in"))
    )
    (net (code "196") (name "Net-(U12-OUTPUT)") (class "Default")
      (node (ref "C29") (pin "1") (pinfunction "1_1") (pintype "passive"))
      (node (ref "U12") (pin "1") (pinfunction "OUTPUT_1") (pintype "output"))
    )
    (net (code "197") (name "Net-(U14A-+IN)") (class "Default")
      (node (ref "C30") (pin "1") (pinfunction "1_1") (pintype "passive"))
      (node (ref "R27") (pin "1") (pinfunction "1_1") (pintype "passive"))
      (node (ref "R37") (pin "2") (pinfunction "2_2") (pintype "passive"))
      (node (ref "U14") (pin "3") (pinfunction "+IN_3") (pintype "input"))
    )
    (net (code "198") (name "Net-(U14A--IN)") (class "Default")
      (node (ref "C27") (pin "1") (pinfunction "1_1") (pintype "passive"))
      (node (ref "R38") (pin "1") (pinfunction "1_1") (pintype "passive"))
      (node (ref "R39") (pin "2") (pinfunction "2_2") (pintype "passive"))
      (node (ref "U14") (pin "4") (pinfunction "-IN_4") (pintype "input"))
    )
    (net (code "199") (name "Net-(U25-REG)") (class "Default")
      (node (ref "C34") (pin "2") (pinfunction "2_2") (pintype "passive"))
      (node (ref "U25") (pin "1") (pinfunction "REG_1") (pintype "output"))
    )
    (net (code "200") (name "Net-(Y1-CRYSTAL_2)") (class "Default")
      (node (ref "C83") (pin "2") (pinfunction "2_2") (pintype "passive"))
      (node (ref "R35") (pin "2") (pinfunction "2_2") (pintype "passive"))
      (node (ref "Y1") (pin "3") (pinfunction "CRYSTAL_2_3") (pintype "bidirectional"))
    )
    (net (code "201") (name "PREVGH") (class "Default")
      (node (ref "C16") (pin "1") (pinfunction "1_1") (pintype "passive"))
      (node (ref "D4") (pin "1") (pinfunction "K_1") (pintype "bidirectional"))
      (node (ref "EINK_524352471") (pin "4") (pinfunction "4_4") (pintype "passive"))
    )
    (net (code "202") (name "PREVGL") (class "Default")
      (node (ref "C14") (pin "1") (pinfunction "1_1") (pintype "passive"))
      (node (ref "D3") (pin "2") (pinfunction "A_2") (pintype "bidirectional"))
      (node (ref "EINK_524352471") (pin "2") (pinfunction "2_2") (pintype "passive"))
    )
    (net (code "203") (name "SAM_1V1") (class "Default")
      (node (ref "C2040") (pin "23") (pinfunction "DVDD_2_23") (pintype "power_in"))
      (node (ref "C2040") (pin "45") (pinfunction "VREG_VOUT_45") (pintype "output"))
      (node (ref "C2040") (pin "50") (pinfunction "DVDD_50") (pintype "power_in"))
      (node (ref "C76") (pin "1") (pinfunction "1_1") (pintype "passive"))
      (node (ref "C77") (pin "1") (pinfunction "1_1") (pintype "passive"))
    )
    (net (code "204") (name "SAM_3V3") (class "Default")
      (node (ref "BUD") (pin "1_1") (pinfunction "1_1_1") (pintype "passive"))
      (node (ref "BUD") (pin "1_2") (pinfunction "1_1_2") (pintype "passive"))
      (node (ref "BUP") (pin "1_1") (pinfunction "1_1_1") (pintype "passive"))
      (node (ref "BUP") (pin "1_2") (pinfunction "1_1_2") (pintype "passive"))
      (node (ref "BUS") (pin "1_1") (pinfunction "1_1_1") (pintype "passive"))
      (node (ref "BUS") (pin "1_2") (pinfunction "1_1_2") (pintype "passive"))
      (node (ref "C2040") (pin "1") (pinfunction "IOVDD_2_1") (pintype "power_in"))
      (node (ref "C2040") (pin "10") (pinfunction "IOVDD_3_10") (pintype "power_in"))
      (node (ref "C2040") (pin "22") (pinfunction "IOVDD_4_22") (pintype "power_in"))
      (node (ref "C2040") (pin "33") (pinfunction "IOVDD_5_33") (pintype "power_in"))
      (node (ref "C2040") (pin "42") (pinfunction "IOVDD_6_42") (pintype "power_in"))
      (node (ref "C2040") (pin "43") (pinfunction "ADC_AVDD_43") (pintype "power_in"))
      (node (ref "C2040") (pin "44") (pinfunction "VREG_VIN_44") (pintype "power_in"))
      (node (ref "C2040") (pin "48") (pinfunction "USB_VDD_48") (pintype "power_in"))
      (node (ref "C2040") (pin "49") (pinfunction "IOVDD_49") (pintype "power_in"))
      (node (ref "C24") (pin "2") (pinfunction "2_2") (pintype "passive"))
      (node (ref "C43") (pin "1") (pinfunction "1_1") (pintype "passive"))
      (node (ref "C44") (pin "1") (pinfunction "1_1") (pintype "passive"))
      (node (ref "C7") (pin "1") (pinfunction "1_1") (pintype "passive"))
      (node (ref "C71") (pin "1") (pinfunction "1_1") (pintype "passive"))
      (node (ref "C72") (pin "1") (pinfunction "1_1") (pintype "passive"))
      (node (ref "C73") (pin "1") (pinfunction "1_1") (pintype "passive"))
      (node (ref "C74") (pin "1") (pinfunction "1_1") (pintype "passive"))
      (node (ref "C75") (pin "1") (pinfunction "1_1") (pintype "passive"))
      (node (ref "C80") (pin "1") (pinfunction "1_1") (pintype "passive"))
      (node (ref "D7") (pin "A") (pinfunction "A_A") (pintype "passive"))
      (node (ref "J4") (pin "1") (pinfunction "1_1") (pintype "passive"))
      (node (ref "Q2") (pin "2") (pinfunction "S_2") (pintype "passive"))
      (node (ref "R16") (pin "2") (pinfunction "2_2") (pintype "passive"))
      (node (ref "R17") (pin "2") (pinfunction "2_2") (pintype "passive"))
      (node (ref "R25") (pin "2") (pinfunction "2_2") (pintype "passive"))
      (node (ref "R26") (pin "2") (pinfunction "2_2") (pintype "passive"))
      (node (ref "R28") (pin "2") (pinfunction "2_2") (pintype "passive"))
      (node (ref "R40") (pin "2") (pinfunction "2_2") (pintype "passive"))
      (node (ref "R42") (pin "2") (pinfunction "2_2") (pintype "passive"))
      (node (ref "R43") (pin "1") (pinfunction "1_1") (pintype "passive"))
      (node (ref "U11") (pin "5") (pinfunction "OUT_5") (pintype "power_in"))
      (node (ref "U16") (pin "8") (pinfunction "VCC_8") (pintype "power_in"))
      (node (ref "U5") (pin "5") (pinfunction "VCC_5") (pintype "power_in"))
      (node (ref "U7") (pin "19") (pinfunction "VCC_19") (pintype "power_in"))
      (node (ref "USB2.0MUX") (pin "9") (pinfunction "VCC_9") (pintype "power_in"))
    )
    (net (code "205") (name "SAM_QSPI_SCN") (class "Default")
      (node (ref "C2040") (pin "56") (pinfunction "QSPI_SCN_56") (pintype "bidirectional"))
      (node (ref "R34") (pin "1") (pinfunction "1_1") (pintype "passive"))
      (node (ref "U16") (pin "1") (pinfunction "~{CS}_1") (pintype "input"))
    )
    (net (code "206") (name "SAM_SCL") (class "Default")
      (node (ref "C2040") (pin "37") (pinfunction "GPIO25_37") (pintype "bidirectional"))
      (node (ref "J4") (pin "3") (pinfunction "3_3") (pintype "passive"))
      (node (ref "R26") (pin "1") (pinfunction "1_1") (pintype "passive"))
      (node (ref "RPIBOOT8") (pin "P$1") (pinfunction "1_P$1") (pintype "bidirectional"))
      (node (ref "U25") (pin "2") (pinfunction "SCL_2") (pintype "input"))
      (node (ref "U3") (pin "2") (pinfunction "SCL_2") (pintype "bidirectional"))
    )
    (net (code "207") (name "SAM_SDA") (class "Default")
      (node (ref "C2040") (pin "36") (pinfunction "GPIO24_36") (pintype "bidirectional"))
      (node (ref "GND37") (pin "P$1") (pinfunction "1_P$1") (pintype "bidirectional"))
      (node (ref "J4") (pin "2") (pinfunction "2_2") (pintype "passive"))
      (node (ref "R25") (pin "1") (pinfunction "1_1") (pintype "passive"))
      (node (ref "U25") (pin "3") (pinfunction "SDA_3") (pintype "bidirectional"))
      (node (ref "U3") (pin "1") (pinfunction "SDA_1") (pintype "bidirectional"))
    )
    (net (code "208") (name "SCL1") (class "Default")
      (node (ref "IC1") (pin "1") (pinfunction "SCL_1") (pintype "input"))
      (node (ref "IC3") (pin "17") (pinfunction "SCL_17") (pintype "input"))
      (node (ref "R18") (pin "1") (pinfunction "1_1") (pintype "passive"))
      (node (ref "RPI-CM1") (pin "56") (pinfunction "GPIO3_56") (pintype "passive"))
      (node (ref "RPIBOOT6") (pin "P$1") (pinfunction "1_P$1") (pintype "bidirectional"))
      (node (ref "U6") (pin "13") (pinfunction "SCL_13") (pintype "bidirectional"))
      (node (ref "U9") (pin "2") (pinfunction "SMCLK_2") (pintype "input"))
    )
    (net (code "209") (name "SDA1") (class "Default")
      (node (ref "GND7") (pin "P$1") (pinfunction "1_P$1") (pintype "bidirectional"))
      (node (ref "IC1") (pin "11") (pinfunction "SDA_11") (pintype "bidirectional"))
      (node (ref "IC3") (pin "18") (pinfunction "SDA_18") (pintype "bidirectional"))
      (node (ref "R15") (pin "1") (pinfunction "1_1") (pintype "passive"))
      (node (ref "RPI-CM1") (pin "58") (pinfunction "GPIO2_58") (pintype "passive"))
      (node (ref "U6") (pin "14") (pinfunction "SDA_14") (pintype "bidirectional"))
      (node (ref "U9") (pin "1") (pinfunction "SMDATA_1") (pintype "bidirectional"))
    )
    (net (code "210") (name "THERM") (class "Default")
      (node (ref "J1") (pin "2") (pinfunction "2_2") (pintype "passive"))
      (node (ref "SJ1") (pin "1") (pinfunction "1_1") (pintype "passive"))
    )
    (net (code "211") (name "TS") (class "Default")
      (node (ref "SJ1") (pin "2") (pinfunction "2_2") (pintype "passive"))
      (node (ref "U3") (pin "10") (pinfunction "BIN_10") (pintype "bidirectional"))
      (node (ref "U4") (pin "1") (pinfunction "TS_1") (pintype "bidirectional"))
    )
    (net (code "212") (name "UART_RXD3_SAM") (class "Default")
      (node (ref "C2040") (pin "2") (pinfunction "GPIO0_2") (pintype "bidirectional"))
      (node (ref "R40") (pin "1") (pinfunction "1_1") (pintype "passive"))
      (node (ref "RPI-CM1") (pin "34") (pinfunction "GPIO5_34") (pintype "passive"))
      (node (ref "RPIBOOT7") (pin "P$1") (pinfunction "1_P$1") (pintype "bidirectional"))
    )
    (net (code "213") (name "UART_TXD3_SAM") (class "Default")
      (node (ref "C2040") (pin "3") (pinfunction "GPIO1_3") (pintype "bidirectional"))
      (node (ref "GND36") (pin "P$1") (pinfunction "1_P$1") (pintype "bidirectional"))
      (node (ref "R42") (pin "1") (pinfunction "1_1") (pintype "passive"))
      (node (ref "RPI-CM1") (pin "54") (pinfunction "GPIO4_54") (pintype "passive"))
    )
    (net (code "214") (name "USB_N") (class "Default")
      (node (ref "J2") (pin "A7") (pinfunction "D-_A7") (pintype "bidirectional"))
      (node (ref "J2") (pin "B7") (pinfunction "D-_B7") (pintype "bidirectional"))
      (node (ref "RPI-CM1") (pin "103") (pinfunction "USB_N_103") (pintype "passive"))
      (node (ref "U13") (pin "5") (pinfunction "D2-_5") (pintype "passive"))
      (node (ref "USB2.0MUX") (pin "5") (pinfunction "D-_5") (pintype "bidirectional"))
    )
    (net (code "215") (name "USB_P") (class "Default")
      (node (ref "J2") (pin "A6") (pinfunction "D+_A6") (pintype "bidirectional"))
      (node (ref "J2") (pin "B6") (pinfunction "D+_B6") (pintype "bidirectional"))
      (node (ref "RPI-CM1") (pin "105") (pinfunction "USB_P_105") (pintype "passive"))
      (node (ref "U13") (pin "4") (pinfunction "D2+_4") (pintype "passive"))
      (node (ref "USB2.0MUX") (pin "3") (pinfunction "D+_3") (pintype "bidirectional"))
    )
    (net (code "216") (name "USB_SAM_N") (class "Default")
      (node (ref "R32") (pin "1") (pinfunction "1_1") (pintype "passive"))
      (node (ref "USB2.0MUX") (pin "7") (pinfunction "D1-_7") (pintype "bidirectional"))
    )
    (net (code "217") (name "USB_SAM_P") (class "Default")
      (node (ref "R31") (pin "1") (pinfunction "1_1") (pintype "passive"))
      (node (ref "USB2.0MUX") (pin "1") (pinfunction "D1+_1") (pintype "bidirectional"))
    )
    (net (code "218") (name "VBUS") (class "Default")
      (node (ref "C22") (pin "1") (pinfunction "1_1") (pintype "passive"))
      (node (ref "C3") (pin "1") (pinfunction "1_1") (pintype "passive"))
      (node (ref "C53") (pin "1") (pinfunction "1_1") (pintype "passive"))
      (node (ref "J2") (pin "VBUS1") (pinfunction "VBUS_VBUS1") (pintype "bidirectional"))
      (node (ref "J2") (pin "VBUS2") (pinfunction "VBUS_VBUS2") (pintype "bidirectional"))
      (node (ref "U4") (pin "13") (pinfunction "IN_13") (pintype "bidirectional"))
    )
    (net (code "219") (name "VOUT") (class "Default")
      (node (ref "C1") (pin "1") (pinfunction "1_1") (pintype "passive"))
      (node (ref "C21") (pin "1") (pinfunction "1_1") (pintype "passive"))
      (node (ref "C26") (pin "1") (pinfunction "1_1") (pintype "passive"))
      (node (ref "C32") (pin "1") (pinfunction "1_1") (pintype "passive"))
      (node (ref "C4") (pin "1") (pinfunction "1_1") (pintype "passive"))
      (node (ref "C79") (pin "1") (pinfunction "1_1") (pintype "passive"))
      (node (ref "D5") (pin "A") (pinfunction "A_A") (pintype "passive"))
      (node (ref "D6") (pin "A") (pinfunction "A_A") (pintype "passive"))
      (node (ref "L1") (pin "P$1") (pinfunction "1_P$1") (pintype "passive"))
      (node (ref "R1") (pin "2") (pinfunction "2_2") (pintype "passive"))
      (node (ref "R36") (pin "1") (pinfunction "1_1") (pintype "passive"))
      (node (ref "RPIBOOT4") (pin "P$1") (pinfunction "1_P$1") (pintype "bidirectional"))
      (node (ref "T1") (pin "E") (pinfunction "E_E") (pintype "passive"))
      (node (ref "U1") (pin "8") (pinfunction "VBAT_8") (pintype "input"))
      (node (ref "U11") (pin "1") (pinfunction "IN_1") (pintype "power_in"))
      (node (ref "U11") (pin "3") (pinfunction "EN_3") (pintype "input"))
      (node (ref "U15") (pin "1") (pinfunction "IN_1") (pintype "power_in"))
      (node (ref "U15") (pin "3") (pinfunction "EN_3") (pintype "input"))
      (node (ref "U4") (pin "10") (pinfunction "OUT_10") (pintype "bidirectional"))
      (node (ref "U4") (pin "11") (pinfunction "OUT_11") (pintype "bidirectional"))
      (node (ref "U4") (pin "5") (pinfunction "EN2_5") (pintype "bidirectional"))
    )
    (net (code "220") (name "V_BATT") (class "Default")
      (node (ref "C23") (pin "1") (pinfunction "1_1") (pintype "passive"))
      (node (ref "C40") (pin "1") (pinfunction "1_1") (pintype "passive"))
      (node (ref "R12") (pin "1") (pinfunction "1_1") (pintype "passive"))
      (node (ref "RPIBOOT5") (pin "P$1") (pinfunction "1_P$1") (pintype "bidirectional"))
      (node (ref "U3") (pin "7") (pinfunction "SRN_7") (pintype "bidirectional"))
      (node (ref "U4") (pin "2") (pinfunction "BAT_2") (pintype "bidirectional"))
      (node (ref "U4") (pin "3") (pinfunction "BAT_3") (pintype "bidirectional"))
    )
    (net (code "221") (name "unconnected-(C2040-GPIO20-Pad31)") (class "Default")
      (node (ref "C2040") (pin "31") (pinfunction "GPIO20_31") (pintype "bidirectional"))
    )
    (net (code "222") (name "unconnected-(CAMERA-Pad18)") (class "Default")
      (node (ref "CAMERA") (pin "18") (pinfunction "18_18") (pintype "passive"))
    )
    (net (code "223") (name "unconnected-(IC1-CS-Pad10)") (class "Default")
      (node (ref "IC1") (pin "10") (pinfunction "CS_10") (pintype "input"))
    )
    (net (code "224") (name "unconnected-(IC1-DRDY-Pad8)") (class "Default")
      (node (ref "IC1") (pin "8") (pinfunction "DRDY_8") (pintype "output"))
    )
    (net (code "225") (name "unconnected-(IC1-INT-Pad7)") (class "Default")
      (node (ref "IC1") (pin "7") (pinfunction "INT_7") (pintype "output"))
    )
    (net (code "226") (name "unconnected-(IC3-HP_L-Pad31)") (class "Default")
      (node (ref "IC3") (pin "31") (pinfunction "HP_L_31") (pintype "output"))
    )
    (net (code "227") (name "unconnected-(IC3-HP_R-Pad29)") (class "Default")
      (node (ref "IC3") (pin "29") (pinfunction "HP_R_29") (pintype "output"))
    )
    (net (code "228") (name "unconnected-(IC3-LINPUT1-Pad4)") (class "Default")
      (node (ref "IC3") (pin "4") (pinfunction "LINPUT1_4") (pintype "input"))
    )
    (net (code "229") (name "unconnected-(IC3-LINPUT2-Pad3)") (class "Default")
      (node (ref "IC3") (pin "3") (pinfunction "LINPUT2_3") (pintype "input"))
    )
    (net (code "230") (name "unconnected-(IC3-LINPUT3-Pad2)") (class "Default")
      (node (ref "IC3") (pin "2") (pinfunction "LINPUT3_2") (pintype "input"))
    )
    (net (code "231") (name "unconnected-(IC3-OUT3-Pad30)") (class "Default")
      (node (ref "IC3") (pin "30") (pinfunction "OUT3_30") (pintype "output"))
    )
    (net (code "232") (name "unconnected-(IC3-RINPUT2-Pad6)") (class "Default")
      (node (ref "IC3") (pin "6") (pinfunction "RINPUT2_6") (pintype "input"))
    )
    (net (code "233") (name "unconnected-(IC3-RINPUT3-Pad7)") (class "Default")
      (node (ref "IC3") (pin "7") (pinfunction "RINPUT3_7") (pintype "input"))
    )
    (net (code "234") (name "unconnected-(IC3-SPK_RN-Pad19)") (class "Default")
      (node (ref "IC3") (pin "19") (pinfunction "SPK_RN_19") (pintype "output"))
    )
    (net (code "235") (name "unconnected-(IC3-SPK_RP-Pad22)") (class "Default")
      (node (ref "IC3") (pin "22") (pinfunction "SPK_RP_22") (pintype "output"))
    )
    (net (code "236") (name "unconnected-(M.2KEYM(NGFF)-P5-Pad5)") (class "Default")
      (node (ref "M.2KEYM(NGFF)") (pin "5") (pinfunction "P5_5") (pintype "passive"))
    )
    (net (code "237") (name "unconnected-(M.2KEYM(NGFF)-P6-Pad6)") (class "Default")
      (node (ref "M.2KEYM(NGFF)") (pin "6") (pinfunction "P6_6") (pintype "passive"))
    )
    (net (code "238") (name "unconnected-(M.2KEYM(NGFF)-P7-Pad7)") (class "Default")
      (node (ref "M.2KEYM(NGFF)") (pin "7") (pinfunction "P7_7") (pintype "passive"))
    )
    (net (code "239") (name "unconnected-(M.2KEYM(NGFF)-P8-Pad8)") (class "Default")
      (node (ref "M.2KEYM(NGFF)") (pin "8") (pinfunction "P8_8") (pintype "passive"))
    )
    (net (code "240") (name "unconnected-(M.2KEYM(NGFF)-P10-Pad10)") (class "Default")
      (node (ref "M.2KEYM(NGFF)") (pin "10") (pinfunction "P10_10") (pintype "passive"))
    )
    (net (code "241") (name "unconnected-(M.2KEYM(NGFF)-P11-Pad11)") (class "Default")
      (node (ref "M.2KEYM(NGFF)") (pin "11") (pinfunction "P11_11") (pintype "passive"))
    )
    (net (code "242") (name "unconnected-(M.2KEYM(NGFF)-P13-Pad13)") (class "Default")
      (node (ref "M.2KEYM(NGFF)") (pin "13") (pinfunction "P13_13") (pintype "passive"))
    )
    (net (code "243") (name "unconnected-(M.2KEYM(NGFF)-P17-Pad17)") (class "Default")
      (node (ref "M.2KEYM(NGFF)") (pin "17") (pinfunction "P17_17") (pintype "passive"))
    )
    (net (code "244") (name "unconnected-(M.2KEYM(NGFF)-P19-Pad19)") (class "Default")
      (node (ref "M.2KEYM(NGFF)") (pin "19") (pinfunction "P19_19") (pintype "passive"))
    )
    (net (code "245") (name "unconnected-(M.2KEYM(NGFF)-P20-Pad20)") (class "Default")
      (node (ref "M.2KEYM(NGFF)") (pin "20") (pinfunction "P20_20") (pintype "passive"))
    )
    (net (code "246") (name "unconnected-(M.2KEYM(NGFF)-P22-Pad22)") (class "Default")
      (node (ref "M.2KEYM(NGFF)") (pin "22") (pinfunction "P22_22") (pintype "passive"))
    )
    (net (code "247") (name "unconnected-(M.2KEYM(NGFF)-P23-Pad23)") (class "Default")
      (node (ref "M.2KEYM(NGFF)") (pin "23") (pinfunction "P23_23") (pintype "passive"))
    )
    (net (code "248") (name "unconnected-(M.2KEYM(NGFF)-P24-Pad24)") (class "Default")
      (node (ref "M.2KEYM(NGFF)") (pin "24") (pinfunction "P24_24") (pintype "passive"))
    )
    (net (code "249") (name "unconnected-(M.2KEYM(NGFF)-P25-Pad25)") (class "Default")
      (node (ref "M.2KEYM(NGFF)") (pin "25") (pinfunction "P25_25") (pintype "passive"))
    )
    (net (code "250") (name "unconnected-(M.2KEYM(NGFF)-P26-Pad26)") (class "Default")
      (node (ref "M.2KEYM(NGFF)") (pin "26") (pinfunction "P26_26") (pintype "passive"))
    )
    (net (code "251") (name "unconnected-(M.2KEYM(NGFF)-P28-Pad28)") (class "Default")
      (node (ref "M.2KEYM(NGFF)") (pin "28") (pinfunction "P28_28") (pintype "passive"))
    )
    (net (code "252") (name "unconnected-(M.2KEYM(NGFF)-P29-Pad29)") (class "Default")
      (node (ref "M.2KEYM(NGFF)") (pin "29") (pinfunction "P29_29") (pintype "passive"))
    )
    (net (code "253") (name "unconnected-(M.2KEYM(NGFF)-P30-Pad30)") (class "Default")
      (node (ref "M.2KEYM(NGFF)") (pin "30") (pinfunction "P30_30") (pintype "passive"))
    )
    (net (code "254") (name "unconnected-(M.2KEYM(NGFF)-P31-Pad31)") (class "Default")
      (node (ref "M.2KEYM(NGFF)") (pin "31") (pinfunction "P31_31") (pintype "passive"))
    )
    (net (code "255") (name "unconnected-(M.2KEYM(NGFF)-P32-Pad32)") (class "Default")
      (node (ref "M.2KEYM(NGFF)") (pin "32") (pinfunction "P32_32") (pintype "passive"))
    )
    (net (code "256") (name "unconnected-(M.2KEYM(NGFF)-P34-Pad34)") (class "Default")
      (node (ref "M.2KEYM(NGFF)") (pin "34") (pinfunction "P34_34") (pintype "passive"))
    )
    (net (code "257") (name "unconnected-(M.2KEYM(NGFF)-P35-Pad35)") (class "Default")
      (node (ref "M.2KEYM(NGFF)") (pin "35") (pinfunction "P35_35") (pintype "passive"))
    )
    (net (code "258") (name "unconnected-(M.2KEYM(NGFF)-P36-Pad36)") (class "Default")
      (node (ref "M.2KEYM(NGFF)") (pin "36") (pinfunction "P36_36") (pintype "passive"))
    )
    (net (code "259") (name "unconnected-(M.2KEYM(NGFF)-P37-Pad37)") (class "Default")
      (node (ref "M.2KEYM(NGFF)") (pin "37") (pinfunction "P37_37") (pintype "passive"))
    )
    (net (code "260") (name "unconnected-(M.2KEYM(NGFF)-P38-Pad38)") (class "Default")
      (node (ref "M.2KEYM(NGFF)") (pin "38") (pinfunction "P38_38") (pintype "passive"))
    )
    (net (code "261") (name "unconnected-(M.2KEYM(NGFF)-P40-Pad40)") (class "Default")
      (node (ref "M.2KEYM(NGFF)") (pin "40") (pinfunction "P40_40") (pintype "passive"))
    )
    (net (code "262") (name "unconnected-(M.2KEYM(NGFF)-P42-Pad42)") (class "Default")
      (node (ref "M.2KEYM(NGFF)") (pin "42") (pinfunction "P42_42") (pintype "passive"))
    )
    (net (code "263") (name "unconnected-(M.2KEYM(NGFF)-P44-Pad44)") (class "Default")
      (node (ref "M.2KEYM(NGFF)") (pin "44") (pinfunction "P44_44") (pintype "passive"))
    )
    (net (code "264") (name "unconnected-(M.2KEYM(NGFF)-P46-Pad46)") (class "Default")
      (node (ref "M.2KEYM(NGFF)") (pin "46") (pinfunction "P46_46") (pintype "passive"))
    )
    (net (code "265") (name "unconnected-(M.2KEYM(NGFF)-P48-Pad48)") (class "Default")
      (node (ref "M.2KEYM(NGFF)") (pin "48") (pinfunction "P48_48") (pintype "passive"))
    )
    (net (code "266") (name "unconnected-(M.2KEYM(NGFF)-P54-Pad54)") (class "Default")
      (node (ref "M.2KEYM(NGFF)") (pin "54") (pinfunction "P54_54") (pintype "passive"))
    )
    (net (code "267") (name "unconnected-(M.2KEYM(NGFF)-P56-Pad56)") (class "Default")
      (node (ref "M.2KEYM(NGFF)") (pin "56") (pinfunction "P56_56") (pintype "passive"))
    )
    (net (code "268") (name "unconnected-(M.2KEYM(NGFF)-P58-Pad58)") (class "Default")
      (node (ref "M.2KEYM(NGFF)") (pin "58") (pinfunction "P58_58") (pintype "passive"))
    )
    (net (code "269") (name "unconnected-(M.2KEYM(NGFF)-P67-Pad67)") (class "Default")
      (node (ref "M.2KEYM(NGFF)") (pin "67") (pinfunction "P67_67") (pintype "passive"))
    )
    (net (code "270") (name "unconnected-(M.2KEYM(NGFF)-P68-Pad68)") (class "Default")
      (node (ref "M.2KEYM(NGFF)") (pin "68") (pinfunction "P68_68") (pintype "passive"))
    )
    (net (code "271") (name "unconnected-(M.2KEYM(NGFF)-P69-Pad69)") (class "Default")
      (node (ref "M.2KEYM(NGFF)") (pin "69") (pinfunction "P69_69") (pintype "passive"))
    )
    (net (code "272") (name "unconnected-(RPI-CM1A-ANALOGP0-Pad96)") (class "Default")
      (node (ref "RPI-CM1") (pin "96") (pinfunction "ANALOGP0_96") (pintype "passive"))
    )
    (net (code "273") (name "unconnected-(RPI-CM1A-ANALOGP1-Pad94)") (class "Default")
      (node (ref "RPI-CM1") (pin "94") (pinfunction "ANALOGP1_94") (pintype "passive"))
    )
    (net (code "274") (name "unconnected-(RPI-CM1A-BT_~{DISABLE}-Pad91)") (class "Default")
      (node (ref "RPI-CM1") (pin "91") (pinfunction "BT_~{DISABLE}_91") (pintype "passive"))
    )
    (net (code "275") (name "unconnected-(RPI-CM1A-EEPROM_~{WP}-Pad20)") (class "Default")
      (node (ref "RPI-CM1") (pin "20") (pinfunction "EEPROM_~{WP}_20") (pintype "passive"))
    )
    (net (code "276") (name "unconnected-(RPI-CM1A-ETH_PAIR0_N-Pad10)") (class "Default")
      (node (ref "RPI-CM1") (pin "10") (pinfunction "ETH_PAIR0_N_10") (pintype "passive"))
    )
    (net (code "277") (name "unconnected-(RPI-CM1A-ETH_PAIR0_P-Pad12)") (class "Default")
      (node (ref "RPI-CM1") (pin "12") (pinfunction "ETH_PAIR0_P_12") (pintype "passive"))
    )
    (net (code "278") (name "unconnected-(RPI-CM1A-ETH_PAIR1_N-Pad6)") (class "Default")
      (node (ref "RPI-CM1") (pin "6") (pinfunction "ETH_PAIR1_N_6") (pintype "passive"))
    )
    (net (code "279") (name "unconnected-(RPI-CM1A-ETH_PAIR1_P-Pad4)") (class "Default")
      (node (ref "RPI-CM1") (pin "4") (pinfunction "ETH_PAIR1_P_4") (pintype "passive"))
    )
    (net (code "280") (name "unconnected-(RPI-CM1A-ETH_PAIR2_N-Pad9)") (class "Default")
      (node (ref "RPI-CM1") (pin "9") (pinfunction "ETH_PAIR2_N_9") (pintype "passive"))
    )
    (net (code "281") (name "unconnected-(RPI-CM1A-ETH_PAIR2_P-Pad11)") (class "Default")
      (node (ref "RPI-CM1") (pin "11") (pinfunction "ETH_PAIR2_P_11") (pintype "passive"))
    )
    (net (code "282") (name "unconnected-(RPI-CM1A-ETH_PAIR3_N-Pad5)") (class "Default")
      (node (ref "RPI-CM1") (pin "5") (pinfunction "ETH_PAIR3_N_5") (pintype "passive"))
    )
    (net (code "283") (name "unconnected-(RPI-CM1A-ETH_PAIR3_P-Pad3)") (class "Default")
      (node (ref "RPI-CM1") (pin "3") (pinfunction "ETH_PAIR3_P_3") (pintype "passive"))
    )
    (net (code "284") (name "unconnected-(RPI-CM1A-ETH_SYNC_IN-Pad16)") (class "Default")
      (node (ref "RPI-CM1") (pin "16") (pinfunction "ETH_SYNC_IN_16") (pintype "passive"))
    )
    (net (code "285") (name "unconnected-(RPI-CM1A-ETH_SYNC_OUT-Pad18)") (class "Default")
      (node (ref "RPI-CM1") (pin "18") (pinfunction "ETH_SYNC_OUT_18") (pintype "passive"))
    )
    (net (code "286") (name "unconnected-(RPI-CM1A-ETH_~{LED1}-Pad19)") (class "Default")
      (node (ref "RPI-CM1") (pin "19") (pinfunction "ETH_~{LED1}_19") (pintype "passive"))
    )
    (net (code "287") (name "unconnected-(RPI-CM1A-ETH_~{LED2}-Pad17)") (class "Default")
      (node (ref "RPI-CM1") (pin "17") (pinfunction "ETH_~{LED2}_17") (pintype "passive"))
    )
    (net (code "288") (name "unconnected-(RPI-CM1A-ETH_~{LED3}-Pad15)") (class "Default")
      (node (ref "RPI-CM1") (pin "15") (pinfunction "ETH_~{LED3}_15") (pintype "passive"))
    )
    (net (code "289") (name "unconnected-(RPI-CM1A-GLOBAL_EN-Pad99)") (class "Default")
      (node (ref "RPI-CM1") (pin "99") (pinfunction "GLOBAL_EN_99") (pintype "passive"))
    )
    (net (code "290") (name "unconnected-(RPI-CM1A-GPIO7-Pad37)") (class "Default")
      (node (ref "RPI-CM1") (pin "37") (pinfunction "GPIO7_37") (pintype "passive"))
    )
    (net (code "291") (name "unconnected-(RPI-CM1A-GPIO12-Pad31)") (class "Default")
      (node (ref "RPI-CM1") (pin "31") (pinfunction "GPIO12_31") (pintype "passive"))
    )
    (net (code "292") (name "unconnected-(RPI-CM1A-GPIO17-Pad50)") (class "Default")
      (node (ref "RPI-CM1") (pin "50") (pinfunction "GPIO17_50") (pintype "passive"))
    )
    (net (code "293") (name "unconnected-(RPI-CM1A-GPIO23-Pad47)") (class "Default")
      (node (ref "RPI-CM1") (pin "47") (pinfunction "GPIO23_47") (pintype "passive"))
    )
    (net (code "294") (name "unconnected-(RPI-CM1A-GPIO24-Pad45)") (class "Default")
      (node (ref "RPI-CM1") (pin "45") (pinfunction "GPIO24_45") (pintype "passive"))
    )
    (net (code "295") (name "unconnected-(RPI-CM1A-GPIO25-Pad41)") (class "Default")
      (node (ref "RPI-CM1") (pin "41") (pinfunction "GPIO25_41") (pintype "passive"))
    )
    (net (code "296") (name "unconnected-(RPI-CM1A-GPIO26-Pad24)") (class "Default")
      (node (ref "RPI-CM1") (pin "24") (pinfunction "GPIO26_24") (pintype "passive"))
    )
    (net (code "297") (name "unconnected-(RPI-CM1A-GPIO27-Pad48)") (class "Default")
      (node (ref "RPI-CM1") (pin "48") (pinfunction "GPIO27_48") (pintype "passive"))
    )
    (net (code "298") (name "unconnected-(RPI-CM1A-ID_SC-Pad35)") (class "Default")
      (node (ref "RPI-CM1") (pin "35") (pinfunction "ID_SC_35") (pintype "passive"))
    )
    (net (code "299") (name "unconnected-(RPI-CM1A-ID_SD-Pad36)") (class "Default")
      (node (ref "RPI-CM1") (pin "36") (pinfunction "ID_SD_36") (pintype "passive"))
    )
    (net (code "300") (name "unconnected-(RPI-CM1A-RESERVED-Pad76)") (class "Default")
      (node (ref "RPI-CM1") (pin "76") (pinfunction "RESERVED_76") (pintype "passive"))
    )
    (net (code "301") (name "unconnected-(RPI-CM1A-RUN_PG-Pad92)") (class "Default")
      (node (ref "RPI-CM1") (pin "92") (pinfunction "RUN_PG_92") (pintype "passive"))
    )
    (net (code "302") (name "unconnected-(RPI-CM1A-SD_CLK-Pad57)") (class "Default")
      (node (ref "RPI-CM1") (pin "57") (pinfunction "SD_CLK_57") (pintype "passive"))
    )
    (net (code "303") (name "unconnected-(RPI-CM1A-SD_CMD-Pad62)") (class "Default")
      (node (ref "RPI-CM1") (pin "62") (pinfunction "SD_CMD_62") (pintype "passive"))
    )
    (net (code "304") (name "unconnected-(RPI-CM1A-SD_DAT0-Pad63)") (class "Default")
      (node (ref "RPI-CM1") (pin "63") (pinfunction "SD_DAT0_63") (pintype "passive"))
    )
    (net (code "305") (name "unconnected-(RPI-CM1A-SD_DAT1-Pad67)") (class "Default")
      (node (ref "RPI-CM1") (pin "67") (pinfunction "SD_DAT1_67") (pintype "passive"))
    )
    (net (code "306") (name "unconnected-(RPI-CM1A-SD_DAT2-Pad69)") (class "Default")
      (node (ref "RPI-CM1") (pin "69") (pinfunction "SD_DAT2_69") (pintype "passive"))
    )
    (net (code "307") (name "unconnected-(RPI-CM1A-SD_DAT3-Pad61)") (class "Default")
      (node (ref "RPI-CM1") (pin "61") (pinfunction "SD_DAT3_61") (pintype "passive"))
    )
    (net (code "308") (name "unconnected-(RPI-CM1A-SD_DAT4-Pad68)") (class "Default")
      (node (ref "RPI-CM1") (pin "68") (pinfunction "SD_DAT4_68") (pintype "passive"))
    )
    (net (code "309") (name "unconnected-(RPI-CM1A-SD_DAT5-Pad64)") (class "Default")
      (node (ref "RPI-CM1") (pin "64") (pinfunction "SD_DAT5_64") (pintype "passive"))
    )
    (net (code "310") (name "unconnected-(RPI-CM1A-SD_DAT6-Pad72)") (class "Default")
      (node (ref "RPI-CM1") (pin "72") (pinfunction "SD_DAT6_72") (pintype "passive"))
    )
    (net (code "311") (name "unconnected-(RPI-CM1A-SD_DAT7-Pad70)") (class "Default")
      (node (ref "RPI-CM1") (pin "70") (pinfunction "SD_DAT7_70") (pintype "passive"))
    )
    (net (code "312") (name "unconnected-(RPI-CM1A-SD_PWR_ON-Pad75)") (class "Default")
      (node (ref "RPI-CM1") (pin "75") (pinfunction "SD_PWR_ON_75") (pintype "passive"))
    )
    (net (code "313") (name "unconnected-(RPI-CM1A-SD_VDD_OVERRIDE-Pad73)") (class "Default")
      (node (ref "RPI-CM1") (pin "73") (pinfunction "SD_VDD_OVERRIDE_73") (pintype "passive"))
    )
    (net (code "314") (name "unconnected-(RPI-CM1A-WL_~{DISABLE}-Pad89)") (class "Default")
      (node (ref "RPI-CM1") (pin "89") (pinfunction "WL_~{DISABLE}_89") (pintype "passive"))
    )
    (net (code "315") (name "unconnected-(RPI-CM1A-~{EXTRST}-Pad100)") (class "Default")
      (node (ref "RPI-CM1") (pin "100") (pinfunction "~{EXTRST}_100") (pintype "passive"))
    )
    (net (code "316") (name "unconnected-(U2-NC-Pad1)") (class "Default")
      (node (ref "U2") (pin "1") (pinfunction "NC_1") (pintype "no_connect"))
    )
    (net (code "317") (name "unconnected-(U4-~{PGOOD}-Pad7)") (class "Default")
      (node (ref "U4") (pin "7") (pinfunction "~{PGOOD}_7") (pintype "bidirectional"))
    )
    (net (code "318") (name "unconnected-(U5-NC-Pad1)") (class "Default")
      (node (ref "U5") (pin "1") (pinfunction "NC_1") (pintype "no_connect"))
    )
    (net (code "319") (name "unconnected-(U6-CS-Pad12)") (class "Default")
      (node (ref "U6") (pin "12") (pinfunction "CS_12") (pintype "bidirectional"))
    )
    (net (code "320") (name "unconnected-(U6-INT1-Pad4)") (class "Default")
      (node (ref "U6") (pin "4") (pinfunction "INT1_4") (pintype "bidirectional"))
    )
    (net (code "321") (name "unconnected-(U6-INT2-Pad9)") (class "Default")
      (node (ref "U6") (pin "9") (pinfunction "INT2_9") (pintype "bidirectional"))
    )
    (net (code "322") (name "unconnected-(U6-SCX-Pad3)") (class "Default")
      (node (ref "U6") (pin "3") (pinfunction "SCX_3") (pintype "bidirectional"))
    )
    (net (code "323") (name "unconnected-(U6-SDX-Pad2)") (class "Default")
      (node (ref "U6") (pin "2") (pinfunction "SDX_2") (pintype "bidirectional"))
    )
    (net (code "324") (name "unconnected-(U9-CLK-Pad7)") (class "Default")
      (node (ref "U9") (pin "7") (pinfunction "CLK_7") (pintype "bidirectional"))
    )
    (net (code "325") (name "unconnected-(U9-~{ALERT}-Pad8)") (class "Default")
      (node (ref "U9") (pin "8") (pinfunction "~{ALERT}_8") (pintype "output"))
    )
    (net (code "326") (name "unconnected-(U10-P4-Pad4)") (class "Default")
      (node (ref "U10") (pin "4") (pinfunction "P4_4") (pintype "bidirectional"))
    )
    (net (code "327") (name "unconnected-(U11-P4-Pad4)") (class "Default")
      (node (ref "U11") (pin "4") (pinfunction "P4_4") (pintype "bidirectional"))
    )
    (net (code "328") (name "unconnected-(U13-D1+-Pad1)") (class "Default")
      (node (ref "U13") (pin "1") (pinfunction "D1+_1") (pintype "passive"))
    )
    (net (code "329") (name "unconnected-(U13-D1--Pad2)") (class "Default")
      (node (ref "U13") (pin "2") (pinfunction "D1-_2") (pintype "passive"))
    )
    (net (code "330") (name "unconnected-(U13-NC-Pad10)") (class "Default")
      (node (ref "U13") (pin "10") (pinfunction "NC_10") (pintype "passive"))
    )
    (net (code "331") (name "unconnected-(U13-NC_2-Pad6)") (class "Default")
      (node (ref "U13") (pin "6") (pinfunction "NC_2_6") (pintype "passive"))
    )
    (net (code "332") (name "unconnected-(U13-NC_3-Pad7)") (class "Default")
      (node (ref "U13") (pin "7") (pinfunction "NC_3_7") (pintype "passive"))
    )
    (net (code "333") (name "unconnected-(U13-NC_4-Pad9)") (class "Default")
      (node (ref "U13") (pin "9") (pinfunction "NC_4_9") (pintype "passive"))
    )
    (net (code "334") (name "unconnected-(U15-P4-Pad4)") (class "Default")
      (node (ref "U15") (pin "4") (pinfunction "P4_4") (pintype "bidirectional"))
    )
    (net (code "335") (name "unconnected-(USB2.0MUX-D2+-Pad2)") (class "Default")
      (node (ref "USB2.0MUX") (pin "2") (pinfunction "D2+_2") (pintype "bidirectional"))
    )
    (net (code "336") (name "unconnected-(USB2.0MUX-D2--Pad6)") (class "Default")
      (node (ref "USB2.0MUX") (pin "6") (pinfunction "D2-_6") (pintype "bidirectional"))
    )
  )
)
